# vga_controller.net
KiCad netlist of a schematic drawn in EAGLE
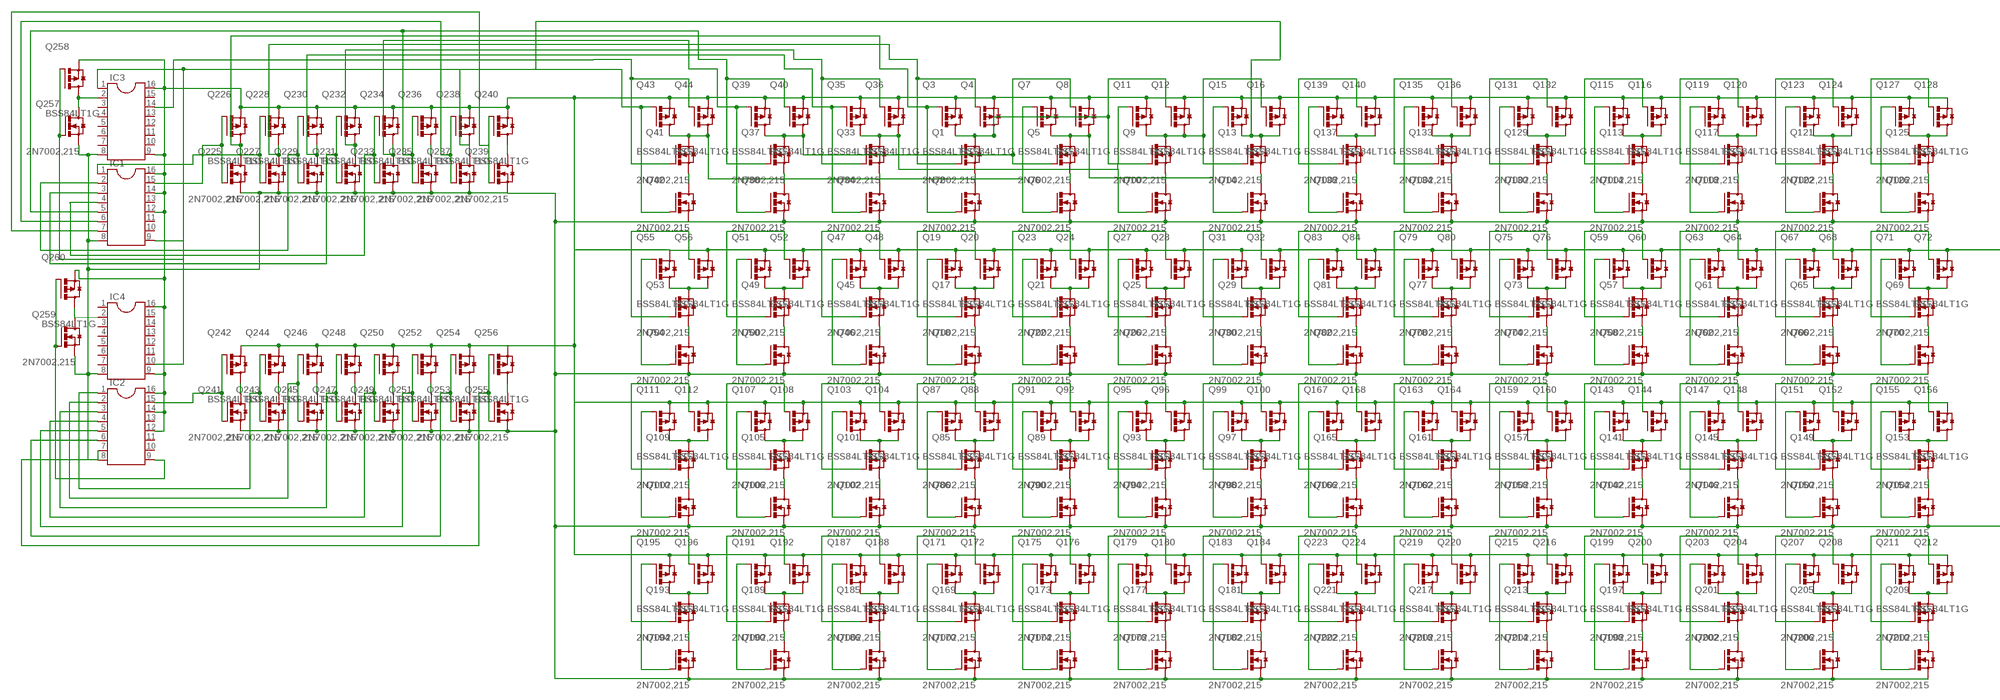
[diagram p0: schematic, sheet 1, part 1 of 2]
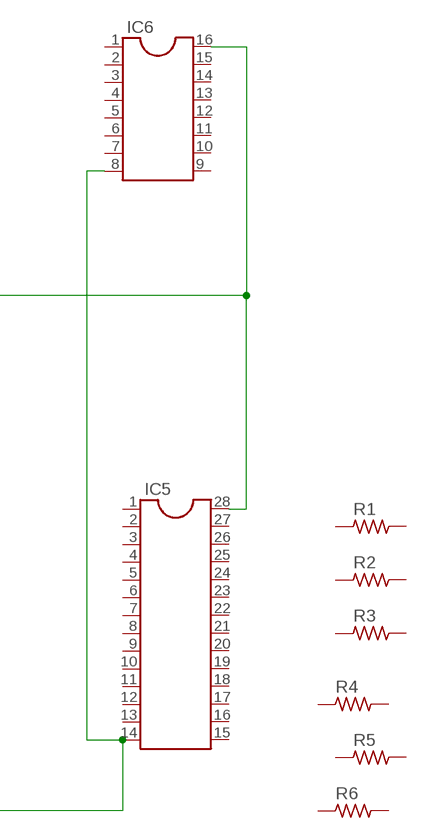
[diagram p1: schematic, sheet 1, part 2 of 2]

(export (version "E")
  (design (tool "Eeschema 10.0.6"))
  (components
    (comp (ref "IC1")
      (value "DIL16S")
      (footprint "eagle-import:SOCKET-16")
      (libsource (lib "eagle-import") (part "DIL16S"))
    )
    (comp (ref "IC2")
      (value "DIL16S")
      (footprint "eagle-import:SOCKET-16")
      (libsource (lib "eagle-import") (part "DIL16S"))
    )
    (comp (ref "IC3")
      (value "DIL16S")
      (footprint "eagle-import:SOCKET-16")
      (libsource (lib "eagle-import") (part "DIL16S"))
    )
    (comp (ref "IC4")
      (value "DIL16S")
      (footprint "eagle-import:SOCKET-16")
      (libsource (lib "eagle-import") (part "DIL16S"))
    )
    (comp (ref "IC5")
      (value "DIL28-3")
      (footprint "eagle-import:DIL28-3")
      (libsource (lib "eagle-import") (part "DIL28-3"))
    )
    (comp (ref "IC6")
      (value "DIL16S")
      (footprint "eagle-import:SOCKET-16")
      (libsource (lib "eagle-import") (part "DIL16S"))
    )
    (comp (ref "Q1")
      (value "2N7002,215")
      (footprint "eagle-import:SOT23-3")
      (fields
        (field (name "DIGIKEY_PART_NUMBER") "1727-2764-1-ND")
        (field (name "MANUFACTURER") "Nexperia USA Inc.")
        (field (name "CREATED_BY") "PCBLayout.com")
      )
      (libsource (lib "eagle-import") (part "2N7002,215"))
    )
    (comp (ref "Q2")
      (value "2N7002,215")
      (footprint "eagle-import:SOT23-3")
      (fields
        (field (name "DIGIKEY_PART_NUMBER") "1727-2764-1-ND")
        (field (name "MANUFACTURER") "Nexperia USA Inc.")
        (field (name "CREATED_BY") "PCBLayout.com")
      )
      (libsource (lib "eagle-import") (part "2N7002,215"))
    )
    (comp (ref "Q3")
      (value "BSS84LT1G")
      (footprint "eagle-import:SOT23-3")
      (fields
        (field (name "DIGIKEY_PART_NUMBER") "BSS84LT1GOSCT-ND")
        (field (name "MANUFACTURER") "ON Semiconductor")
        (field (name "CREATED_BY") "PCBLayout.com")
      )
      (libsource (lib "eagle-import") (part "BSS84LT1G"))
    )
    (comp (ref "Q4")
      (value "BSS84LT1G")
      (footprint "eagle-import:SOT23-3")
      (fields
        (field (name "DIGIKEY_PART_NUMBER") "BSS84LT1GOSCT-ND")
        (field (name "MANUFACTURER") "ON Semiconductor")
        (field (name "CREATED_BY") "PCBLayout.com")
      )
      (libsource (lib "eagle-import") (part "BSS84LT1G"))
    )
    (comp (ref "Q5")
      (value "2N7002,215")
      (footprint "eagle-import:SOT23-3")
      (fields
        (field (name "DIGIKEY_PART_NUMBER") "1727-2764-1-ND")
        (field (name "MANUFACTURER") "Nexperia USA Inc.")
        (field (name "CREATED_BY") "PCBLayout.com")
      )
      (libsource (lib "eagle-import") (part "2N7002,215"))
    )
    (comp (ref "Q6")
      (value "2N7002,215")
      (footprint "eagle-import:SOT23-3")
      (fields
        (field (name "DIGIKEY_PART_NUMBER") "1727-2764-1-ND")
        (field (name "MANUFACTURER") "Nexperia USA Inc.")
        (field (name "CREATED_BY") "PCBLayout.com")
      )
      (libsource (lib "eagle-import") (part "2N7002,215"))
    )
    (comp (ref "Q7")
      (value "BSS84LT1G")
      (footprint "eagle-import:SOT23-3")
      (fields
        (field (name "DIGIKEY_PART_NUMBER") "BSS84LT1GOSCT-ND")
        (field (name "MANUFACTURER") "ON Semiconductor")
        (field (name "CREATED_BY") "PCBLayout.com")
      )
      (libsource (lib "eagle-import") (part "BSS84LT1G"))
    )
    (comp (ref "Q8")
      (value "BSS84LT1G")
      (footprint "eagle-import:SOT23-3")
      (fields
        (field (name "DIGIKEY_PART_NUMBER") "BSS84LT1GOSCT-ND")
        (field (name "MANUFACTURER") "ON Semiconductor")
        (field (name "CREATED_BY") "PCBLayout.com")
      )
      (libsource (lib "eagle-import") (part "BSS84LT1G"))
    )
    (comp (ref "Q9")
      (value "2N7002,215")
      (footprint "eagle-import:SOT23-3")
      (fields
        (field (name "DIGIKEY_PART_NUMBER") "1727-2764-1-ND")
        (field (name "MANUFACTURER") "Nexperia USA Inc.")
        (field (name "CREATED_BY") "PCBLayout.com")
      )
      (libsource (lib "eagle-import") (part "2N7002,215"))
    )
    (comp (ref "Q10")
      (value "2N7002,215")
      (footprint "eagle-import:SOT23-3")
      (fields
        (field (name "DIGIKEY_PART_NUMBER") "1727-2764-1-ND")
        (field (name "MANUFACTURER") "Nexperia USA Inc.")
        (field (name "CREATED_BY") "PCBLayout.com")
      )
      (libsource (lib "eagle-import") (part "2N7002,215"))
    )
    (comp (ref "Q11")
      (value "BSS84LT1G")
      (footprint "eagle-import:SOT23-3")
      (fields
        (field (name "DIGIKEY_PART_NUMBER") "BSS84LT1GOSCT-ND")
        (field (name "MANUFACTURER") "ON Semiconductor")
        (field (name "CREATED_BY") "PCBLayout.com")
      )
      (libsource (lib "eagle-import") (part "BSS84LT1G"))
    )
    (comp (ref "Q12")
      (value "BSS84LT1G")
      (footprint "eagle-import:SOT23-3")
      (fields
        (field (name "DIGIKEY_PART_NUMBER") "BSS84LT1GOSCT-ND")
        (field (name "MANUFACTURER") "ON Semiconductor")
        (field (name "CREATED_BY") "PCBLayout.com")
      )
      (libsource (lib "eagle-import") (part "BSS84LT1G"))
    )
    (comp (ref "Q13")
      (value "2N7002,215")
      (footprint "eagle-import:SOT23-3")
      (fields
        (field (name "DIGIKEY_PART_NUMBER") "1727-2764-1-ND")
        (field (name "MANUFACTURER") "Nexperia USA Inc.")
        (field (name "CREATED_BY") "PCBLayout.com")
      )
      (libsource (lib "eagle-import") (part "2N7002,215"))
    )
    (comp (ref "Q14")
      (value "2N7002,215")
      (footprint "eagle-import:SOT23-3")
      (fields
        (field (name "DIGIKEY_PART_NUMBER") "1727-2764-1-ND")
        (field (name "MANUFACTURER") "Nexperia USA Inc.")
        (field (name "CREATED_BY") "PCBLayout.com")
      )
      (libsource (lib "eagle-import") (part "2N7002,215"))
    )
    (comp (ref "Q15")
      (value "BSS84LT1G")
      (footprint "eagle-import:SOT23-3")
      (fields
        (field (name "DIGIKEY_PART_NUMBER") "BSS84LT1GOSCT-ND")
        (field (name "MANUFACTURER") "ON Semiconductor")
        (field (name "CREATED_BY") "PCBLayout.com")
      )
      (libsource (lib "eagle-import") (part "BSS84LT1G"))
    )
    (comp (ref "Q16")
      (value "BSS84LT1G")
      (footprint "eagle-import:SOT23-3")
      (fields
        (field (name "DIGIKEY_PART_NUMBER") "BSS84LT1GOSCT-ND")
        (field (name "MANUFACTURER") "ON Semiconductor")
        (field (name "CREATED_BY") "PCBLayout.com")
      )
      (libsource (lib "eagle-import") (part "BSS84LT1G"))
    )
    (comp (ref "Q17")
      (value "2N7002,215")
      (footprint "eagle-import:SOT23-3")
      (fields
        (field (name "DIGIKEY_PART_NUMBER") "1727-2764-1-ND")
        (field (name "MANUFACTURER") "Nexperia USA Inc.")
        (field (name "CREATED_BY") "PCBLayout.com")
      )
      (libsource (lib "eagle-import") (part "2N7002,215"))
    )
    (comp (ref "Q18")
      (value "2N7002,215")
      (footprint "eagle-import:SOT23-3")
      (fields
        (field (name "DIGIKEY_PART_NUMBER") "1727-2764-1-ND")
        (field (name "MANUFACTURER") "Nexperia USA Inc.")
        (field (name "CREATED_BY") "PCBLayout.com")
      )
      (libsource (lib "eagle-import") (part "2N7002,215"))
    )
    (comp (ref "Q19")
      (value "BSS84LT1G")
      (footprint "eagle-import:SOT23-3")
      (fields
        (field (name "DIGIKEY_PART_NUMBER") "BSS84LT1GOSCT-ND")
        (field (name "MANUFACTURER") "ON Semiconductor")
        (field (name "CREATED_BY") "PCBLayout.com")
      )
      (libsource (lib "eagle-import") (part "BSS84LT1G"))
    )
    (comp (ref "Q20")
      (value "BSS84LT1G")
      (footprint "eagle-import:SOT23-3")
      (fields
        (field (name "DIGIKEY_PART_NUMBER") "BSS84LT1GOSCT-ND")
        (field (name "MANUFACTURER") "ON Semiconductor")
        (field (name "CREATED_BY") "PCBLayout.com")
      )
      (libsource (lib "eagle-import") (part "BSS84LT1G"))
    )
    (comp (ref "Q21")
      (value "2N7002,215")
      (footprint "eagle-import:SOT23-3")
      (fields
        (field (name "DIGIKEY_PART_NUMBER") "1727-2764-1-ND")
        (field (name "MANUFACTURER") "Nexperia USA Inc.")
        (field (name "CREATED_BY") "PCBLayout.com")
      )
      (libsource (lib "eagle-import") (part "2N7002,215"))
    )
    (comp (ref "Q22")
      (value "2N7002,215")
      (footprint "eagle-import:SOT23-3")
      (fields
        (field (name "DIGIKEY_PART_NUMBER") "1727-2764-1-ND")
        (field (name "MANUFACTURER") "Nexperia USA Inc.")
        (field (name "CREATED_BY") "PCBLayout.com")
      )
      (libsource (lib "eagle-import") (part "2N7002,215"))
    )
    (comp (ref "Q23")
      (value "BSS84LT1G")
      (footprint "eagle-import:SOT23-3")
      (fields
        (field (name "DIGIKEY_PART_NUMBER") "BSS84LT1GOSCT-ND")
        (field (name "MANUFACTURER") "ON Semiconductor")
        (field (name "CREATED_BY") "PCBLayout.com")
      )
      (libsource (lib "eagle-import") (part "BSS84LT1G"))
    )
    (comp (ref "Q24")
      (value "BSS84LT1G")
      (footprint "eagle-import:SOT23-3")
      (fields
        (field (name "DIGIKEY_PART_NUMBER") "BSS84LT1GOSCT-ND")
        (field (name "MANUFACTURER") "ON Semiconductor")
        (field (name "CREATED_BY") "PCBLayout.com")
      )
      (libsource (lib "eagle-import") (part "BSS84LT1G"))
    )
    (comp (ref "Q25")
      (value "2N7002,215")
      (footprint "eagle-import:SOT23-3")
      (fields
        (field (name "DIGIKEY_PART_NUMBER") "1727-2764-1-ND")
        (field (name "MANUFACTURER") "Nexperia USA Inc.")
        (field (name "CREATED_BY") "PCBLayout.com")
      )
      (libsource (lib "eagle-import") (part "2N7002,215"))
    )
    (comp (ref "Q26")
      (value "2N7002,215")
      (footprint "eagle-import:SOT23-3")
      (fields
        (field (name "DIGIKEY_PART_NUMBER") "1727-2764-1-ND")
        (field (name "MANUFACTURER") "Nexperia USA Inc.")
        (field (name "CREATED_BY") "PCBLayout.com")
      )
      (libsource (lib "eagle-import") (part "2N7002,215"))
    )
    (comp (ref "Q27")
      (value "BSS84LT1G")
      (footprint "eagle-import:SOT23-3")
      (fields
        (field (name "DIGIKEY_PART_NUMBER") "BSS84LT1GOSCT-ND")
        (field (name "MANUFACTURER") "ON Semiconductor")
        (field (name "CREATED_BY") "PCBLayout.com")
      )
      (libsource (lib "eagle-import") (part "BSS84LT1G"))
    )
    (comp (ref "Q28")
      (value "BSS84LT1G")
      (footprint "eagle-import:SOT23-3")
      (fields
        (field (name "DIGIKEY_PART_NUMBER") "BSS84LT1GOSCT-ND")
        (field (name "MANUFACTURER") "ON Semiconductor")
        (field (name "CREATED_BY") "PCBLayout.com")
      )
      (libsource (lib "eagle-import") (part "BSS84LT1G"))
    )
    (comp (ref "Q29")
      (value "2N7002,215")
      (footprint "eagle-import:SOT23-3")
      (fields
        (field (name "DIGIKEY_PART_NUMBER") "1727-2764-1-ND")
        (field (name "MANUFACTURER") "Nexperia USA Inc.")
        (field (name "CREATED_BY") "PCBLayout.com")
      )
      (libsource (lib "eagle-import") (part "2N7002,215"))
    )
    (comp (ref "Q30")
      (value "2N7002,215")
      (footprint "eagle-import:SOT23-3")
      (fields
        (field (name "DIGIKEY_PART_NUMBER") "1727-2764-1-ND")
        (field (name "MANUFACTURER") "Nexperia USA Inc.")
        (field (name "CREATED_BY") "PCBLayout.com")
      )
      (libsource (lib "eagle-import") (part "2N7002,215"))
    )
    (comp (ref "Q31")
      (value "BSS84LT1G")
      (footprint "eagle-import:SOT23-3")
      (fields
        (field (name "DIGIKEY_PART_NUMBER") "BSS84LT1GOSCT-ND")
        (field (name "MANUFACTURER") "ON Semiconductor")
        (field (name "CREATED_BY") "PCBLayout.com")
      )
      (libsource (lib "eagle-import") (part "BSS84LT1G"))
    )
    (comp (ref "Q32")
      (value "BSS84LT1G")
      (footprint "eagle-import:SOT23-3")
      (fields
        (field (name "DIGIKEY_PART_NUMBER") "BSS84LT1GOSCT-ND")
        (field (name "MANUFACTURER") "ON Semiconductor")
        (field (name "CREATED_BY") "PCBLayout.com")
      )
      (libsource (lib "eagle-import") (part "BSS84LT1G"))
    )
    (comp (ref "Q33")
      (value "2N7002,215")
      (footprint "eagle-import:SOT23-3")
      (fields
        (field (name "DIGIKEY_PART_NUMBER") "1727-2764-1-ND")
        (field (name "MANUFACTURER") "Nexperia USA Inc.")
        (field (name "CREATED_BY") "PCBLayout.com")
      )
      (libsource (lib "eagle-import") (part "2N7002,215"))
    )
    (comp (ref "Q34")
      (value "2N7002,215")
      (footprint "eagle-import:SOT23-3")
      (fields
        (field (name "DIGIKEY_PART_NUMBER") "1727-2764-1-ND")
        (field (name "MANUFACTURER") "Nexperia USA Inc.")
        (field (name "CREATED_BY") "PCBLayout.com")
      )
      (libsource (lib "eagle-import") (part "2N7002,215"))
    )
    (comp (ref "Q35")
      (value "BSS84LT1G")
      (footprint "eagle-import:SOT23-3")
      (fields
        (field (name "DIGIKEY_PART_NUMBER") "BSS84LT1GOSCT-ND")
        (field (name "MANUFACTURER") "ON Semiconductor")
        (field (name "CREATED_BY") "PCBLayout.com")
      )
      (libsource (lib "eagle-import") (part "BSS84LT1G"))
    )
    (comp (ref "Q36")
      (value "BSS84LT1G")
      (footprint "eagle-import:SOT23-3")
      (fields
        (field (name "DIGIKEY_PART_NUMBER") "BSS84LT1GOSCT-ND")
        (field (name "MANUFACTURER") "ON Semiconductor")
        (field (name "CREATED_BY") "PCBLayout.com")
      )
      (libsource (lib "eagle-import") (part "BSS84LT1G"))
    )
    (comp (ref "Q37")
      (value "2N7002,215")
      (footprint "eagle-import:SOT23-3")
      (fields
        (field (name "DIGIKEY_PART_NUMBER") "1727-2764-1-ND")
        (field (name "MANUFACTURER") "Nexperia USA Inc.")
        (field (name "CREATED_BY") "PCBLayout.com")
      )
      (libsource (lib "eagle-import") (part "2N7002,215"))
    )
    (comp (ref "Q38")
      (value "2N7002,215")
      (footprint "eagle-import:SOT23-3")
      (fields
        (field (name "DIGIKEY_PART_NUMBER") "1727-2764-1-ND")
        (field (name "MANUFACTURER") "Nexperia USA Inc.")
        (field (name "CREATED_BY") "PCBLayout.com")
      )
      (libsource (lib "eagle-import") (part "2N7002,215"))
    )
    (comp (ref "Q39")
      (value "BSS84LT1G")
      (footprint "eagle-import:SOT23-3")
      (fields
        (field (name "DIGIKEY_PART_NUMBER") "BSS84LT1GOSCT-ND")
        (field (name "MANUFACTURER") "ON Semiconductor")
        (field (name "CREATED_BY") "PCBLayout.com")
      )
      (libsource (lib "eagle-import") (part "BSS84LT1G"))
    )
    (comp (ref "Q40")
      (value "BSS84LT1G")
      (footprint "eagle-import:SOT23-3")
      (fields
        (field (name "DIGIKEY_PART_NUMBER") "BSS84LT1GOSCT-ND")
        (field (name "MANUFACTURER") "ON Semiconductor")
        (field (name "CREATED_BY") "PCBLayout.com")
      )
      (libsource (lib "eagle-import") (part "BSS84LT1G"))
    )
    (comp (ref "Q41")
      (value "2N7002,215")
      (footprint "eagle-import:SOT23-3")
      (fields
        (field (name "DIGIKEY_PART_NUMBER") "1727-2764-1-ND")
        (field (name "MANUFACTURER") "Nexperia USA Inc.")
        (field (name "CREATED_BY") "PCBLayout.com")
      )
      (libsource (lib "eagle-import") (part "2N7002,215"))
    )
    (comp (ref "Q42")
      (value "2N7002,215")
      (footprint "eagle-import:SOT23-3")
      (fields
        (field (name "DIGIKEY_PART_NUMBER") "1727-2764-1-ND")
        (field (name "MANUFACTURER") "Nexperia USA Inc.")
        (field (name "CREATED_BY") "PCBLayout.com")
      )
      (libsource (lib "eagle-import") (part "2N7002,215"))
    )
    (comp (ref "Q43")
      (value "BSS84LT1G")
      (footprint "eagle-import:SOT23-3")
      (fields
        (field (name "DIGIKEY_PART_NUMBER") "BSS84LT1GOSCT-ND")
        (field (name "MANUFACTURER") "ON Semiconductor")
        (field (name "CREATED_BY") "PCBLayout.com")
      )
      (libsource (lib "eagle-import") (part "BSS84LT1G"))
    )
    (comp (ref "Q44")
      (value "BSS84LT1G")
      (footprint "eagle-import:SOT23-3")
      (fields
        (field (name "DIGIKEY_PART_NUMBER") "BSS84LT1GOSCT-ND")
        (field (name "MANUFACTURER") "ON Semiconductor")
        (field (name "CREATED_BY") "PCBLayout.com")
      )
      (libsource (lib "eagle-import") (part "BSS84LT1G"))
    )
    (comp (ref "Q45")
      (value "2N7002,215")
      (footprint "eagle-import:SOT23-3")
      (fields
        (field (name "DIGIKEY_PART_NUMBER") "1727-2764-1-ND")
        (field (name "MANUFACTURER") "Nexperia USA Inc.")
        (field (name "CREATED_BY") "PCBLayout.com")
      )
      (libsource (lib "eagle-import") (part "2N7002,215"))
    )
    (comp (ref "Q46")
      (value "2N7002,215")
      (footprint "eagle-import:SOT23-3")
      (fields
        (field (name "DIGIKEY_PART_NUMBER") "1727-2764-1-ND")
        (field (name "MANUFACTURER") "Nexperia USA Inc.")
        (field (name "CREATED_BY") "PCBLayout.com")
      )
      (libsource (lib "eagle-import") (part "2N7002,215"))
    )
    (comp (ref "Q47")
      (value "BSS84LT1G")
      (footprint "eagle-import:SOT23-3")
      (fields
        (field (name "DIGIKEY_PART_NUMBER") "BSS84LT1GOSCT-ND")
        (field (name "MANUFACTURER") "ON Semiconductor")
        (field (name "CREATED_BY") "PCBLayout.com")
      )
      (libsource (lib "eagle-import") (part "BSS84LT1G"))
    )
    (comp (ref "Q48")
      (value "BSS84LT1G")
      (footprint "eagle-import:SOT23-3")
      (fields
        (field (name "DIGIKEY_PART_NUMBER") "BSS84LT1GOSCT-ND")
        (field (name "MANUFACTURER") "ON Semiconductor")
        (field (name "CREATED_BY") "PCBLayout.com")
      )
      (libsource (lib "eagle-import") (part "BSS84LT1G"))
    )
    (comp (ref "Q49")
      (value "2N7002,215")
      (footprint "eagle-import:SOT23-3")
      (fields
        (field (name "DIGIKEY_PART_NUMBER") "1727-2764-1-ND")
        (field (name "MANUFACTURER") "Nexperia USA Inc.")
        (field (name "CREATED_BY") "PCBLayout.com")
      )
      (libsource (lib "eagle-import") (part "2N7002,215"))
    )
    (comp (ref "Q50")
      (value "2N7002,215")
      (footprint "eagle-import:SOT23-3")
      (fields
        (field (name "DIGIKEY_PART_NUMBER") "1727-2764-1-ND")
        (field (name "MANUFACTURER") "Nexperia USA Inc.")
        (field (name "CREATED_BY") "PCBLayout.com")
      )
      (libsource (lib "eagle-import") (part "2N7002,215"))
    )
    (comp (ref "Q51")
      (value "BSS84LT1G")
      (footprint "eagle-import:SOT23-3")
      (fields
        (field (name "DIGIKEY_PART_NUMBER") "BSS84LT1GOSCT-ND")
        (field (name "MANUFACTURER") "ON Semiconductor")
        (field (name "CREATED_BY") "PCBLayout.com")
      )
      (libsource (lib "eagle-import") (part "BSS84LT1G"))
    )
    (comp (ref "Q52")
      (value "BSS84LT1G")
      (footprint "eagle-import:SOT23-3")
      (fields
        (field (name "DIGIKEY_PART_NUMBER") "BSS84LT1GOSCT-ND")
        (field (name "MANUFACTURER") "ON Semiconductor")
        (field (name "CREATED_BY") "PCBLayout.com")
      )
      (libsource (lib "eagle-import") (part "BSS84LT1G"))
    )
    (comp (ref "Q53")
      (value "2N7002,215")
      (footprint "eagle-import:SOT23-3")
      (fields
        (field (name "DIGIKEY_PART_NUMBER") "1727-2764-1-ND")
        (field (name "MANUFACTURER") "Nexperia USA Inc.")
        (field (name "CREATED_BY") "PCBLayout.com")
      )
      (libsource (lib "eagle-import") (part "2N7002,215"))
    )
    (comp (ref "Q54")
      (value "2N7002,215")
      (footprint "eagle-import:SOT23-3")
      (fields
        (field (name "DIGIKEY_PART_NUMBER") "1727-2764-1-ND")
        (field (name "MANUFACTURER") "Nexperia USA Inc.")
        (field (name "CREATED_BY") "PCBLayout.com")
      )
      (libsource (lib "eagle-import") (part "2N7002,215"))
    )
    (comp (ref "Q55")
      (value "BSS84LT1G")
      (footprint "eagle-import:SOT23-3")
      (fields
        (field (name "DIGIKEY_PART_NUMBER") "BSS84LT1GOSCT-ND")
        (field (name "MANUFACTURER") "ON Semiconductor")
        (field (name "CREATED_BY") "PCBLayout.com")
      )
      (libsource (lib "eagle-import") (part "BSS84LT1G"))
    )
    (comp (ref "Q56")
      (value "BSS84LT1G")
      (footprint "eagle-import:SOT23-3")
      (fields
        (field (name "DIGIKEY_PART_NUMBER") "BSS84LT1GOSCT-ND")
        (field (name "MANUFACTURER") "ON Semiconductor")
        (field (name "CREATED_BY") "PCBLayout.com")
      )
      (libsource (lib "eagle-import") (part "BSS84LT1G"))
    )
    (comp (ref "Q57")
      (value "2N7002,215")
      (footprint "eagle-import:SOT23-3")
      (fields
        (field (name "DIGIKEY_PART_NUMBER") "1727-2764-1-ND")
        (field (name "MANUFACTURER") "Nexperia USA Inc.")
        (field (name "CREATED_BY") "PCBLayout.com")
      )
      (libsource (lib "eagle-import") (part "2N7002,215"))
    )
    (comp (ref "Q58")
      (value "2N7002,215")
      (footprint "eagle-import:SOT23-3")
      (fields
        (field (name "DIGIKEY_PART_NUMBER") "1727-2764-1-ND")
        (field (name "MANUFACTURER") "Nexperia USA Inc.")
        (field (name "CREATED_BY") "PCBLayout.com")
      )
      (libsource (lib "eagle-import") (part "2N7002,215"))
    )
    (comp (ref "Q59")
      (value "BSS84LT1G")
      (footprint "eagle-import:SOT23-3")
      (fields
        (field (name "DIGIKEY_PART_NUMBER") "BSS84LT1GOSCT-ND")
        (field (name "MANUFACTURER") "ON Semiconductor")
        (field (name "CREATED_BY") "PCBLayout.com")
      )
      (libsource (lib "eagle-import") (part "BSS84LT1G"))
    )
    (comp (ref "Q60")
      (value "BSS84LT1G")
      (footprint "eagle-import:SOT23-3")
      (fields
        (field (name "DIGIKEY_PART_NUMBER") "BSS84LT1GOSCT-ND")
        (field (name "MANUFACTURER") "ON Semiconductor")
        (field (name "CREATED_BY") "PCBLayout.com")
      )
      (libsource (lib "eagle-import") (part "BSS84LT1G"))
    )
    (comp (ref "Q61")
      (value "2N7002,215")
      (footprint "eagle-import:SOT23-3")
      (fields
        (field (name "DIGIKEY_PART_NUMBER") "1727-2764-1-ND")
        (field (name "MANUFACTURER") "Nexperia USA Inc.")
        (field (name "CREATED_BY") "PCBLayout.com")
      )
      (libsource (lib "eagle-import") (part "2N7002,215"))
    )
    (comp (ref "Q62")
      (value "2N7002,215")
      (footprint "eagle-import:SOT23-3")
      (fields
        (field (name "DIGIKEY_PART_NUMBER") "1727-2764-1-ND")
        (field (name "MANUFACTURER") "Nexperia USA Inc.")
        (field (name "CREATED_BY") "PCBLayout.com")
      )
      (libsource (lib "eagle-import") (part "2N7002,215"))
    )
    (comp (ref "Q63")
      (value "BSS84LT1G")
      (footprint "eagle-import:SOT23-3")
      (fields
        (field (name "DIGIKEY_PART_NUMBER") "BSS84LT1GOSCT-ND")
        (field (name "MANUFACTURER") "ON Semiconductor")
        (field (name "CREATED_BY") "PCBLayout.com")
      )
      (libsource (lib "eagle-import") (part "BSS84LT1G"))
    )
    (comp (ref "Q64")
      (value "BSS84LT1G")
      (footprint "eagle-import:SOT23-3")
      (fields
        (field (name "DIGIKEY_PART_NUMBER") "BSS84LT1GOSCT-ND")
        (field (name "MANUFACTURER") "ON Semiconductor")
        (field (name "CREATED_BY") "PCBLayout.com")
      )
      (libsource (lib "eagle-import") (part "BSS84LT1G"))
    )
    (comp (ref "Q65")
      (value "2N7002,215")
      (footprint "eagle-import:SOT23-3")
      (fields
        (field (name "DIGIKEY_PART_NUMBER") "1727-2764-1-ND")
        (field (name "MANUFACTURER") "Nexperia USA Inc.")
        (field (name "CREATED_BY") "PCBLayout.com")
      )
      (libsource (lib "eagle-import") (part "2N7002,215"))
    )
    (comp (ref "Q66")
      (value "2N7002,215")
      (footprint "eagle-import:SOT23-3")
      (fields
        (field (name "DIGIKEY_PART_NUMBER") "1727-2764-1-ND")
        (field (name "MANUFACTURER") "Nexperia USA Inc.")
        (field (name "CREATED_BY") "PCBLayout.com")
      )
      (libsource (lib "eagle-import") (part "2N7002,215"))
    )
    (comp (ref "Q67")
      (value "BSS84LT1G")
      (footprint "eagle-import:SOT23-3")
      (fields
        (field (name "DIGIKEY_PART_NUMBER") "BSS84LT1GOSCT-ND")
        (field (name "MANUFACTURER") "ON Semiconductor")
        (field (name "CREATED_BY") "PCBLayout.com")
      )
      (libsource (lib "eagle-import") (part "BSS84LT1G"))
    )
    (comp (ref "Q68")
      (value "BSS84LT1G")
      (footprint "eagle-import:SOT23-3")
      (fields
        (field (name "DIGIKEY_PART_NUMBER") "BSS84LT1GOSCT-ND")
        (field (name "MANUFACTURER") "ON Semiconductor")
        (field (name "CREATED_BY") "PCBLayout.com")
      )
      (libsource (lib "eagle-import") (part "BSS84LT1G"))
    )
    (comp (ref "Q69")
      (value "2N7002,215")
      (footprint "eagle-import:SOT23-3")
      (fields
        (field (name "DIGIKEY_PART_NUMBER") "1727-2764-1-ND")
        (field (name "MANUFACTURER") "Nexperia USA Inc.")
        (field (name "CREATED_BY") "PCBLayout.com")
      )
      (libsource (lib "eagle-import") (part "2N7002,215"))
    )
    (comp (ref "Q70")
      (value "2N7002,215")
      (footprint "eagle-import:SOT23-3")
      (fields
        (field (name "DIGIKEY_PART_NUMBER") "1727-2764-1-ND")
        (field (name "MANUFACTURER") "Nexperia USA Inc.")
        (field (name "CREATED_BY") "PCBLayout.com")
      )
      (libsource (lib "eagle-import") (part "2N7002,215"))
    )
    (comp (ref "Q71")
      (value "BSS84LT1G")
      (footprint "eagle-import:SOT23-3")
      (fields
        (field (name "DIGIKEY_PART_NUMBER") "BSS84LT1GOSCT-ND")
        (field (name "MANUFACTURER") "ON Semiconductor")
        (field (name "CREATED_BY") "PCBLayout.com")
      )
      (libsource (lib "eagle-import") (part "BSS84LT1G"))
    )
    (comp (ref "Q72")
      (value "BSS84LT1G")
      (footprint "eagle-import:SOT23-3")
      (fields
        (field (name "DIGIKEY_PART_NUMBER") "BSS84LT1GOSCT-ND")
        (field (name "MANUFACTURER") "ON Semiconductor")
        (field (name "CREATED_BY") "PCBLayout.com")
      )
      (libsource (lib "eagle-import") (part "BSS84LT1G"))
    )
    (comp (ref "Q73")
      (value "2N7002,215")
      (footprint "eagle-import:SOT23-3")
      (fields
        (field (name "DIGIKEY_PART_NUMBER") "1727-2764-1-ND")
        (field (name "MANUFACTURER") "Nexperia USA Inc.")
        (field (name "CREATED_BY") "PCBLayout.com")
      )
      (libsource (lib "eagle-import") (part "2N7002,215"))
    )
    (comp (ref "Q74")
      (value "2N7002,215")
      (footprint "eagle-import:SOT23-3")
      (fields
        (field (name "DIGIKEY_PART_NUMBER") "1727-2764-1-ND")
        (field (name "MANUFACTURER") "Nexperia USA Inc.")
        (field (name "CREATED_BY") "PCBLayout.com")
      )
      (libsource (lib "eagle-import") (part "2N7002,215"))
    )
    (comp (ref "Q75")
      (value "BSS84LT1G")
      (footprint "eagle-import:SOT23-3")
      (fields
        (field (name "DIGIKEY_PART_NUMBER") "BSS84LT1GOSCT-ND")
        (field (name "MANUFACTURER") "ON Semiconductor")
        (field (name "CREATED_BY") "PCBLayout.com")
      )
      (libsource (lib "eagle-import") (part "BSS84LT1G"))
    )
    (comp (ref "Q76")
      (value "BSS84LT1G")
      (footprint "eagle-import:SOT23-3")
      (fields
        (field (name "DIGIKEY_PART_NUMBER") "BSS84LT1GOSCT-ND")
        (field (name "MANUFACTURER") "ON Semiconductor")
        (field (name "CREATED_BY") "PCBLayout.com")
      )
      (libsource (lib "eagle-import") (part "BSS84LT1G"))
    )
    (comp (ref "Q77")
      (value "2N7002,215")
      (footprint "eagle-import:SOT23-3")
      (fields
        (field (name "DIGIKEY_PART_NUMBER") "1727-2764-1-ND")
        (field (name "MANUFACTURER") "Nexperia USA Inc.")
        (field (name "CREATED_BY") "PCBLayout.com")
      )
      (libsource (lib "eagle-import") (part "2N7002,215"))
    )
    (comp (ref "Q78")
      (value "2N7002,215")
      (footprint "eagle-import:SOT23-3")
      (fields
        (field (name "DIGIKEY_PART_NUMBER") "1727-2764-1-ND")
        (field (name "MANUFACTURER") "Nexperia USA Inc.")
        (field (name "CREATED_BY") "PCBLayout.com")
      )
      (libsource (lib "eagle-import") (part "2N7002,215"))
    )
    (comp (ref "Q79")
      (value "BSS84LT1G")
      (footprint "eagle-import:SOT23-3")
      (fields
        (field (name "DIGIKEY_PART_NUMBER") "BSS84LT1GOSCT-ND")
        (field (name "MANUFACTURER") "ON Semiconductor")
        (field (name "CREATED_BY") "PCBLayout.com")
      )
      (libsource (lib "eagle-import") (part "BSS84LT1G"))
    )
    (comp (ref "Q80")
      (value "BSS84LT1G")
      (footprint "eagle-import:SOT23-3")
      (fields
        (field (name "DIGIKEY_PART_NUMBER") "BSS84LT1GOSCT-ND")
        (field (name "MANUFACTURER") "ON Semiconductor")
        (field (name "CREATED_BY") "PCBLayout.com")
      )
      (libsource (lib "eagle-import") (part "BSS84LT1G"))
    )
    (comp (ref "Q81")
      (value "2N7002,215")
      (footprint "eagle-import:SOT23-3")
      (fields
        (field (name "DIGIKEY_PART_NUMBER") "1727-2764-1-ND")
        (field (name "MANUFACTURER") "Nexperia USA Inc.")
        (field (name "CREATED_BY") "PCBLayout.com")
      )
      (libsource (lib "eagle-import") (part "2N7002,215"))
    )
    (comp (ref "Q82")
      (value "2N7002,215")
      (footprint "eagle-import:SOT23-3")
      (fields
        (field (name "DIGIKEY_PART_NUMBER") "1727-2764-1-ND")
        (field (name "MANUFACTURER") "Nexperia USA Inc.")
        (field (name "CREATED_BY") "PCBLayout.com")
      )
      (libsource (lib "eagle-import") (part "2N7002,215"))
    )
    (comp (ref "Q83")
      (value "BSS84LT1G")
      (footprint "eagle-import:SOT23-3")
      (fields
        (field (name "DIGIKEY_PART_NUMBER") "BSS84LT1GOSCT-ND")
        (field (name "MANUFACTURER") "ON Semiconductor")
        (field (name "CREATED_BY") "PCBLayout.com")
      )
      (libsource (lib "eagle-import") (part "BSS84LT1G"))
    )
    (comp (ref "Q84")
      (value "BSS84LT1G")
      (footprint "eagle-import:SOT23-3")
      (fields
        (field (name "DIGIKEY_PART_NUMBER") "BSS84LT1GOSCT-ND")
        (field (name "MANUFACTURER") "ON Semiconductor")
        (field (name "CREATED_BY") "PCBLayout.com")
      )
      (libsource (lib "eagle-import") (part "BSS84LT1G"))
    )
    (comp (ref "Q85")
      (value "2N7002,215")
      (footprint "eagle-import:SOT23-3")
      (fields
        (field (name "DIGIKEY_PART_NUMBER") "1727-2764-1-ND")
        (field (name "MANUFACTURER") "Nexperia USA Inc.")
        (field (name "CREATED_BY") "PCBLayout.com")
      )
      (libsource (lib "eagle-import") (part "2N7002,215"))
    )
    (comp (ref "Q86")
      (value "2N7002,215")
      (footprint "eagle-import:SOT23-3")
      (fields
        (field (name "DIGIKEY_PART_NUMBER") "1727-2764-1-ND")
        (field (name "MANUFACTURER") "Nexperia USA Inc.")
        (field (name "CREATED_BY") "PCBLayout.com")
      )
      (libsource (lib "eagle-import") (part "2N7002,215"))
    )
    (comp (ref "Q87")
      (value "BSS84LT1G")
      (footprint "eagle-import:SOT23-3")
      (fields
        (field (name "DIGIKEY_PART_NUMBER") "BSS84LT1GOSCT-ND")
        (field (name "MANUFACTURER") "ON Semiconductor")
        (field (name "CREATED_BY") "PCBLayout.com")
      )
      (libsource (lib "eagle-import") (part "BSS84LT1G"))
    )
    (comp (ref "Q88")
      (value "BSS84LT1G")
      (footprint "eagle-import:SOT23-3")
      (fields
        (field (name "DIGIKEY_PART_NUMBER") "BSS84LT1GOSCT-ND")
        (field (name "MANUFACTURER") "ON Semiconductor")
        (field (name "CREATED_BY") "PCBLayout.com")
      )
      (libsource (lib "eagle-import") (part "BSS84LT1G"))
    )
    (comp (ref "Q89")
      (value "2N7002,215")
      (footprint "eagle-import:SOT23-3")
      (fields
        (field (name "DIGIKEY_PART_NUMBER") "1727-2764-1-ND")
        (field (name "MANUFACTURER") "Nexperia USA Inc.")
        (field (name "CREATED_BY") "PCBLayout.com")
      )
      (libsource (lib "eagle-import") (part "2N7002,215"))
    )
    (comp (ref "Q90")
      (value "2N7002,215")
      (footprint "eagle-import:SOT23-3")
      (fields
        (field (name "DIGIKEY_PART_NUMBER") "1727-2764-1-ND")
        (field (name "MANUFACTURER") "Nexperia USA Inc.")
        (field (name "CREATED_BY") "PCBLayout.com")
      )
      (libsource (lib "eagle-import") (part "2N7002,215"))
    )
    (comp (ref "Q91")
      (value "BSS84LT1G")
      (footprint "eagle-import:SOT23-3")
      (fields
        (field (name "DIGIKEY_PART_NUMBER") "BSS84LT1GOSCT-ND")
        (field (name "MANUFACTURER") "ON Semiconductor")
        (field (name "CREATED_BY") "PCBLayout.com")
      )
      (libsource (lib "eagle-import") (part "BSS84LT1G"))
    )
    (comp (ref "Q92")
      (value "BSS84LT1G")
      (footprint "eagle-import:SOT23-3")
      (fields
        (field (name "DIGIKEY_PART_NUMBER") "BSS84LT1GOSCT-ND")
        (field (name "MANUFACTURER") "ON Semiconductor")
        (field (name "CREATED_BY") "PCBLayout.com")
      )
      (libsource (lib "eagle-import") (part "BSS84LT1G"))
    )
    (comp (ref "Q93")
      (value "2N7002,215")
      (footprint "eagle-import:SOT23-3")
      (fields
        (field (name "DIGIKEY_PART_NUMBER") "1727-2764-1-ND")
        (field (name "MANUFACTURER") "Nexperia USA Inc.")
        (field (name "CREATED_BY") "PCBLayout.com")
      )
      (libsource (lib "eagle-import") (part "2N7002,215"))
    )
    (comp (ref "Q94")
      (value "2N7002,215")
      (footprint "eagle-import:SOT23-3")
      (fields
        (field (name "DIGIKEY_PART_NUMBER") "1727-2764-1-ND")
        (field (name "MANUFACTURER") "Nexperia USA Inc.")
        (field (name "CREATED_BY") "PCBLayout.com")
      )
      (libsource (lib "eagle-import") (part "2N7002,215"))
    )
    (comp (ref "Q95")
      (value "BSS84LT1G")
      (footprint "eagle-import:SOT23-3")
      (fields
        (field (name "DIGIKEY_PART_NUMBER") "BSS84LT1GOSCT-ND")
        (field (name "MANUFACTURER") "ON Semiconductor")
        (field (name "CREATED_BY") "PCBLayout.com")
      )
      (libsource (lib "eagle-import") (part "BSS84LT1G"))
    )
    (comp (ref "Q96")
      (value "BSS84LT1G")
      (footprint "eagle-import:SOT23-3")
      (fields
        (field (name "DIGIKEY_PART_NUMBER") "BSS84LT1GOSCT-ND")
        (field (name "MANUFACTURER") "ON Semiconductor")
        (field (name "CREATED_BY") "PCBLayout.com")
      )
      (libsource (lib "eagle-import") (part "BSS84LT1G"))
    )
    (comp (ref "Q97")
      (value "2N7002,215")
      (footprint "eagle-import:SOT23-3")
      (fields
        (field (name "DIGIKEY_PART_NUMBER") "1727-2764-1-ND")
        (field (name "MANUFACTURER") "Nexperia USA Inc.")
        (field (name "CREATED_BY") "PCBLayout.com")
      )
      (libsource (lib "eagle-import") (part "2N7002,215"))
    )
    (comp (ref "Q98")
      (value "2N7002,215")
      (footprint "eagle-import:SOT23-3")
      (fields
        (field (name "DIGIKEY_PART_NUMBER") "1727-2764-1-ND")
        (field (name "MANUFACTURER") "Nexperia USA Inc.")
        (field (name "CREATED_BY") "PCBLayout.com")
      )
      (libsource (lib "eagle-import") (part "2N7002,215"))
    )
    (comp (ref "Q99")
      (value "BSS84LT1G")
      (footprint "eagle-import:SOT23-3")
      (fields
        (field (name "DIGIKEY_PART_NUMBER") "BSS84LT1GOSCT-ND")
        (field (name "MANUFACTURER") "ON Semiconductor")
        (field (name "CREATED_BY") "PCBLayout.com")
      )
      (libsource (lib "eagle-import") (part "BSS84LT1G"))
    )
    (comp (ref "Q100")
      (value "BSS84LT1G")
      (footprint "eagle-import:SOT23-3")
      (fields
        (field (name "DIGIKEY_PART_NUMBER") "BSS84LT1GOSCT-ND")
        (field (name "MANUFACTURER") "ON Semiconductor")
        (field (name "CREATED_BY") "PCBLayout.com")
      )
      (libsource (lib "eagle-import") (part "BSS84LT1G"))
    )
    (comp (ref "Q101")
      (value "2N7002,215")
      (footprint "eagle-import:SOT23-3")
      (fields
        (field (name "DIGIKEY_PART_NUMBER") "1727-2764-1-ND")
        (field (name "MANUFACTURER") "Nexperia USA Inc.")
        (field (name "CREATED_BY") "PCBLayout.com")
      )
      (libsource (lib "eagle-import") (part "2N7002,215"))
    )
    (comp (ref "Q102")
      (value "2N7002,215")
      (footprint "eagle-import:SOT23-3")
      (fields
        (field (name "DIGIKEY_PART_NUMBER") "1727-2764-1-ND")
        (field (name "MANUFACTURER") "Nexperia USA Inc.")
        (field (name "CREATED_BY") "PCBLayout.com")
      )
      (libsource (lib "eagle-import") (part "2N7002,215"))
    )
    (comp (ref "Q103")
      (value "BSS84LT1G")
      (footprint "eagle-import:SOT23-3")
      (fields
        (field (name "DIGIKEY_PART_NUMBER") "BSS84LT1GOSCT-ND")
        (field (name "MANUFACTURER") "ON Semiconductor")
        (field (name "CREATED_BY") "PCBLayout.com")
      )
      (libsource (lib "eagle-import") (part "BSS84LT1G"))
    )
    (comp (ref "Q104")
      (value "BSS84LT1G")
      (footprint "eagle-import:SOT23-3")
      (fields
        (field (name "DIGIKEY_PART_NUMBER") "BSS84LT1GOSCT-ND")
        (field (name "MANUFACTURER") "ON Semiconductor")
        (field (name "CREATED_BY") "PCBLayout.com")
      )
      (libsource (lib "eagle-import") (part "BSS84LT1G"))
    )
    (comp (ref "Q105")
      (value "2N7002,215")
      (footprint "eagle-import:SOT23-3")
      (fields
        (field (name "DIGIKEY_PART_NUMBER") "1727-2764-1-ND")
        (field (name "MANUFACTURER") "Nexperia USA Inc.")
        (field (name "CREATED_BY") "PCBLayout.com")
      )
      (libsource (lib "eagle-import") (part "2N7002,215"))
    )
    (comp (ref "Q106")
      (value "2N7002,215")
      (footprint "eagle-import:SOT23-3")
      (fields
        (field (name "DIGIKEY_PART_NUMBER") "1727-2764-1-ND")
        (field (name "MANUFACTURER") "Nexperia USA Inc.")
        (field (name "CREATED_BY") "PCBLayout.com")
      )
      (libsource (lib "eagle-import") (part "2N7002,215"))
    )
    (comp (ref "Q107")
      (value "BSS84LT1G")
      (footprint "eagle-import:SOT23-3")
      (fields
        (field (name "DIGIKEY_PART_NUMBER") "BSS84LT1GOSCT-ND")
        (field (name "MANUFACTURER") "ON Semiconductor")
        (field (name "CREATED_BY") "PCBLayout.com")
      )
      (libsource (lib "eagle-import") (part "BSS84LT1G"))
    )
    (comp (ref "Q108")
      (value "BSS84LT1G")
      (footprint "eagle-import:SOT23-3")
      (fields
        (field (name "DIGIKEY_PART_NUMBER") "BSS84LT1GOSCT-ND")
        (field (name "MANUFACTURER") "ON Semiconductor")
        (field (name "CREATED_BY") "PCBLayout.com")
      )
      (libsource (lib "eagle-import") (part "BSS84LT1G"))
    )
    (comp (ref "Q109")
      (value "2N7002,215")
      (footprint "eagle-import:SOT23-3")
      (fields
        (field (name "DIGIKEY_PART_NUMBER") "1727-2764-1-ND")
        (field (name "MANUFACTURER") "Nexperia USA Inc.")
        (field (name "CREATED_BY") "PCBLayout.com")
      )
      (libsource (lib "eagle-import") (part "2N7002,215"))
    )
    (comp (ref "Q110")
      (value "2N7002,215")
      (footprint "eagle-import:SOT23-3")
      (fields
        (field (name "DIGIKEY_PART_NUMBER") "1727-2764-1-ND")
        (field (name "MANUFACTURER") "Nexperia USA Inc.")
        (field (name "CREATED_BY") "PCBLayout.com")
      )
      (libsource (lib "eagle-import") (part "2N7002,215"))
    )
    (comp (ref "Q111")
      (value "BSS84LT1G")
      (footprint "eagle-import:SOT23-3")
      (fields
        (field (name "DIGIKEY_PART_NUMBER") "BSS84LT1GOSCT-ND")
        (field (name "MANUFACTURER") "ON Semiconductor")
        (field (name "CREATED_BY") "PCBLayout.com")
      )
      (libsource (lib "eagle-import") (part "BSS84LT1G"))
    )
    (comp (ref "Q112")
      (value "BSS84LT1G")
      (footprint "eagle-import:SOT23-3")
      (fields
        (field (name "DIGIKEY_PART_NUMBER") "BSS84LT1GOSCT-ND")
        (field (name "MANUFACTURER") "ON Semiconductor")
        (field (name "CREATED_BY") "PCBLayout.com")
      )
      (libsource (lib "eagle-import") (part "BSS84LT1G"))
    )
    (comp (ref "Q113")
      (value "2N7002,215")
      (footprint "eagle-import:SOT23-3")
      (fields
        (field (name "DIGIKEY_PART_NUMBER") "1727-2764-1-ND")
        (field (name "MANUFACTURER") "Nexperia USA Inc.")
        (field (name "CREATED_BY") "PCBLayout.com")
      )
      (libsource (lib "eagle-import") (part "2N7002,215"))
    )
    (comp (ref "Q114")
      (value "2N7002,215")
      (footprint "eagle-import:SOT23-3")
      (fields
        (field (name "DIGIKEY_PART_NUMBER") "1727-2764-1-ND")
        (field (name "MANUFACTURER") "Nexperia USA Inc.")
        (field (name "CREATED_BY") "PCBLayout.com")
      )
      (libsource (lib "eagle-import") (part "2N7002,215"))
    )
    (comp (ref "Q115")
      (value "BSS84LT1G")
      (footprint "eagle-import:SOT23-3")
      (fields
        (field (name "DIGIKEY_PART_NUMBER") "BSS84LT1GOSCT-ND")
        (field (name "MANUFACTURER") "ON Semiconductor")
        (field (name "CREATED_BY") "PCBLayout.com")
      )
      (libsource (lib "eagle-import") (part "BSS84LT1G"))
    )
    (comp (ref "Q116")
      (value "BSS84LT1G")
      (footprint "eagle-import:SOT23-3")
      (fields
        (field (name "DIGIKEY_PART_NUMBER") "BSS84LT1GOSCT-ND")
        (field (name "MANUFACTURER") "ON Semiconductor")
        (field (name "CREATED_BY") "PCBLayout.com")
      )
      (libsource (lib "eagle-import") (part "BSS84LT1G"))
    )
    (comp (ref "Q117")
      (value "2N7002,215")
      (footprint "eagle-import:SOT23-3")
      (fields
        (field (name "DIGIKEY_PART_NUMBER") "1727-2764-1-ND")
        (field (name "MANUFACTURER") "Nexperia USA Inc.")
        (field (name "CREATED_BY") "PCBLayout.com")
      )
      (libsource (lib "eagle-import") (part "2N7002,215"))
    )
    (comp (ref "Q118")
      (value "2N7002,215")
      (footprint "eagle-import:SOT23-3")
      (fields
        (field (name "DIGIKEY_PART_NUMBER") "1727-2764-1-ND")
        (field (name "MANUFACTURER") "Nexperia USA Inc.")
        (field (name "CREATED_BY") "PCBLayout.com")
      )
      (libsource (lib "eagle-import") (part "2N7002,215"))
    )
    (comp (ref "Q119")
      (value "BSS84LT1G")
      (footprint "eagle-import:SOT23-3")
      (fields
        (field (name "DIGIKEY_PART_NUMBER") "BSS84LT1GOSCT-ND")
        (field (name "MANUFACTURER") "ON Semiconductor")
        (field (name "CREATED_BY") "PCBLayout.com")
      )
      (libsource (lib "eagle-import") (part "BSS84LT1G"))
    )
    (comp (ref "Q120")
      (value "BSS84LT1G")
      (footprint "eagle-import:SOT23-3")
      (fields
        (field (name "DIGIKEY_PART_NUMBER") "BSS84LT1GOSCT-ND")
        (field (name "MANUFACTURER") "ON Semiconductor")
        (field (name "CREATED_BY") "PCBLayout.com")
      )
      (libsource (lib "eagle-import") (part "BSS84LT1G"))
    )
    (comp (ref "Q121")
      (value "2N7002,215")
      (footprint "eagle-import:SOT23-3")
      (fields
        (field (name "DIGIKEY_PART_NUMBER") "1727-2764-1-ND")
        (field (name "MANUFACTURER") "Nexperia USA Inc.")
        (field (name "CREATED_BY") "PCBLayout.com")
      )
      (libsource (lib "eagle-import") (part "2N7002,215"))
    )
    (comp (ref "Q122")
      (value "2N7002,215")
      (footprint "eagle-import:SOT23-3")
      (fields
        (field (name "DIGIKEY_PART_NUMBER") "1727-2764-1-ND")
        (field (name "MANUFACTURER") "Nexperia USA Inc.")
        (field (name "CREATED_BY") "PCBLayout.com")
      )
      (libsource (lib "eagle-import") (part "2N7002,215"))
    )
    (comp (ref "Q123")
      (value "BSS84LT1G")
      (footprint "eagle-import:SOT23-3")
      (fields
        (field (name "DIGIKEY_PART_NUMBER") "BSS84LT1GOSCT-ND")
        (field (name "MANUFACTURER") "ON Semiconductor")
        (field (name "CREATED_BY") "PCBLayout.com")
      )
      (libsource (lib "eagle-import") (part "BSS84LT1G"))
    )
    (comp (ref "Q124")
      (value "BSS84LT1G")
      (footprint "eagle-import:SOT23-3")
      (fields
        (field (name "DIGIKEY_PART_NUMBER") "BSS84LT1GOSCT-ND")
        (field (name "MANUFACTURER") "ON Semiconductor")
        (field (name "CREATED_BY") "PCBLayout.com")
      )
      (libsource (lib "eagle-import") (part "BSS84LT1G"))
    )
    (comp (ref "Q125")
      (value "2N7002,215")
      (footprint "eagle-import:SOT23-3")
      (fields
        (field (name "DIGIKEY_PART_NUMBER") "1727-2764-1-ND")
        (field (name "MANUFACTURER") "Nexperia USA Inc.")
        (field (name "CREATED_BY") "PCBLayout.com")
      )
      (libsource (lib "eagle-import") (part "2N7002,215"))
    )
    (comp (ref "Q126")
      (value "2N7002,215")
      (footprint "eagle-import:SOT23-3")
      (fields
        (field (name "DIGIKEY_PART_NUMBER") "1727-2764-1-ND")
        (field (name "MANUFACTURER") "Nexperia USA Inc.")
        (field (name "CREATED_BY") "PCBLayout.com")
      )
      (libsource (lib "eagle-import") (part "2N7002,215"))
    )
    (comp (ref "Q127")
      (value "BSS84LT1G")
      (footprint "eagle-import:SOT23-3")
      (fields
        (field (name "DIGIKEY_PART_NUMBER") "BSS84LT1GOSCT-ND")
        (field (name "MANUFACTURER") "ON Semiconductor")
        (field (name "CREATED_BY") "PCBLayout.com")
      )
      (libsource (lib "eagle-import") (part "BSS84LT1G"))
    )
    (comp (ref "Q128")
      (value "BSS84LT1G")
      (footprint "eagle-import:SOT23-3")
      (fields
        (field (name "DIGIKEY_PART_NUMBER") "BSS84LT1GOSCT-ND")
        (field (name "MANUFACTURER") "ON Semiconductor")
        (field (name "CREATED_BY") "PCBLayout.com")
      )
      (libsource (lib "eagle-import") (part "BSS84LT1G"))
    )
    (comp (ref "Q129")
      (value "2N7002,215")
      (footprint "eagle-import:SOT23-3")
      (fields
        (field (name "DIGIKEY_PART_NUMBER") "1727-2764-1-ND")
        (field (name "MANUFACTURER") "Nexperia USA Inc.")
        (field (name "CREATED_BY") "PCBLayout.com")
      )
      (libsource (lib "eagle-import") (part "2N7002,215"))
    )
    (comp (ref "Q130")
      (value "2N7002,215")
      (footprint "eagle-import:SOT23-3")
      (fields
        (field (name "DIGIKEY_PART_NUMBER") "1727-2764-1-ND")
        (field (name "MANUFACTURER") "Nexperia USA Inc.")
        (field (name "CREATED_BY") "PCBLayout.com")
      )
      (libsource (lib "eagle-import") (part "2N7002,215"))
    )
    (comp (ref "Q131")
      (value "BSS84LT1G")
      (footprint "eagle-import:SOT23-3")
      (fields
        (field (name "DIGIKEY_PART_NUMBER") "BSS84LT1GOSCT-ND")
        (field (name "MANUFACTURER") "ON Semiconductor")
        (field (name "CREATED_BY") "PCBLayout.com")
      )
      (libsource (lib "eagle-import") (part "BSS84LT1G"))
    )
    (comp (ref "Q132")
      (value "BSS84LT1G")
      (footprint "eagle-import:SOT23-3")
      (fields
        (field (name "DIGIKEY_PART_NUMBER") "BSS84LT1GOSCT-ND")
        (field (name "MANUFACTURER") "ON Semiconductor")
        (field (name "CREATED_BY") "PCBLayout.com")
      )
      (libsource (lib "eagle-import") (part "BSS84LT1G"))
    )
    (comp (ref "Q133")
      (value "2N7002,215")
      (footprint "eagle-import:SOT23-3")
      (fields
        (field (name "DIGIKEY_PART_NUMBER") "1727-2764-1-ND")
        (field (name "MANUFACTURER") "Nexperia USA Inc.")
        (field (name "CREATED_BY") "PCBLayout.com")
      )
      (libsource (lib "eagle-import") (part "2N7002,215"))
    )
    (comp (ref "Q134")
      (value "2N7002,215")
      (footprint "eagle-import:SOT23-3")
      (fields
        (field (name "DIGIKEY_PART_NUMBER") "1727-2764-1-ND")
        (field (name "MANUFACTURER") "Nexperia USA Inc.")
        (field (name "CREATED_BY") "PCBLayout.com")
      )
      (libsource (lib "eagle-import") (part "2N7002,215"))
    )
    (comp (ref "Q135")
      (value "BSS84LT1G")
      (footprint "eagle-import:SOT23-3")
      (fields
        (field (name "DIGIKEY_PART_NUMBER") "BSS84LT1GOSCT-ND")
        (field (name "MANUFACTURER") "ON Semiconductor")
        (field (name "CREATED_BY") "PCBLayout.com")
      )
      (libsource (lib "eagle-import") (part "BSS84LT1G"))
    )
    (comp (ref "Q136")
      (value "BSS84LT1G")
      (footprint "eagle-import:SOT23-3")
      (fields
        (field (name "DIGIKEY_PART_NUMBER") "BSS84LT1GOSCT-ND")
        (field (name "MANUFACTURER") "ON Semiconductor")
        (field (name "CREATED_BY") "PCBLayout.com")
      )
      (libsource (lib "eagle-import") (part "BSS84LT1G"))
    )
    (comp (ref "Q137")
      (value "2N7002,215")
      (footprint "eagle-import:SOT23-3")
      (fields
        (field (name "DIGIKEY_PART_NUMBER") "1727-2764-1-ND")
        (field (name "MANUFACTURER") "Nexperia USA Inc.")
        (field (name "CREATED_BY") "PCBLayout.com")
      )
      (libsource (lib "eagle-import") (part "2N7002,215"))
    )
    (comp (ref "Q138")
      (value "2N7002,215")
      (footprint "eagle-import:SOT23-3")
      (fields
        (field (name "DIGIKEY_PART_NUMBER") "1727-2764-1-ND")
        (field (name "MANUFACTURER") "Nexperia USA Inc.")
        (field (name "CREATED_BY") "PCBLayout.com")
      )
      (libsource (lib "eagle-import") (part "2N7002,215"))
    )
    (comp (ref "Q139")
      (value "BSS84LT1G")
      (footprint "eagle-import:SOT23-3")
      (fields
        (field (name "DIGIKEY_PART_NUMBER") "BSS84LT1GOSCT-ND")
        (field (name "MANUFACTURER") "ON Semiconductor")
        (field (name "CREATED_BY") "PCBLayout.com")
      )
      (libsource (lib "eagle-import") (part "BSS84LT1G"))
    )
    (comp (ref "Q140")
      (value "BSS84LT1G")
      (footprint "eagle-import:SOT23-3")
      (fields
        (field (name "DIGIKEY_PART_NUMBER") "BSS84LT1GOSCT-ND")
        (field (name "MANUFACTURER") "ON Semiconductor")
        (field (name "CREATED_BY") "PCBLayout.com")
      )
      (libsource (lib "eagle-import") (part "BSS84LT1G"))
    )
    (comp (ref "Q141")
      (value "2N7002,215")
      (footprint "eagle-import:SOT23-3")
      (fields
        (field (name "DIGIKEY_PART_NUMBER") "1727-2764-1-ND")
        (field (name "MANUFACTURER") "Nexperia USA Inc.")
        (field (name "CREATED_BY") "PCBLayout.com")
      )
      (libsource (lib "eagle-import") (part "2N7002,215"))
    )
    (comp (ref "Q142")
      (value "2N7002,215")
      (footprint "eagle-import:SOT23-3")
      (fields
        (field (name "DIGIKEY_PART_NUMBER") "1727-2764-1-ND")
        (field (name "MANUFACTURER") "Nexperia USA Inc.")
        (field (name "CREATED_BY") "PCBLayout.com")
      )
      (libsource (lib "eagle-import") (part "2N7002,215"))
    )
    (comp (ref "Q143")
      (value "BSS84LT1G")
      (footprint "eagle-import:SOT23-3")
      (fields
        (field (name "DIGIKEY_PART_NUMBER") "BSS84LT1GOSCT-ND")
        (field (name "MANUFACTURER") "ON Semiconductor")
        (field (name "CREATED_BY") "PCBLayout.com")
      )
      (libsource (lib "eagle-import") (part "BSS84LT1G"))
    )
    (comp (ref "Q144")
      (value "BSS84LT1G")
      (footprint "eagle-import:SOT23-3")
      (fields
        (field (name "DIGIKEY_PART_NUMBER") "BSS84LT1GOSCT-ND")
        (field (name "MANUFACTURER") "ON Semiconductor")
        (field (name "CREATED_BY") "PCBLayout.com")
      )
      (libsource (lib "eagle-import") (part "BSS84LT1G"))
    )
    (comp (ref "Q145")
      (value "2N7002,215")
      (footprint "eagle-import:SOT23-3")
      (fields
        (field (name "DIGIKEY_PART_NUMBER") "1727-2764-1-ND")
        (field (name "MANUFACTURER") "Nexperia USA Inc.")
        (field (name "CREATED_BY") "PCBLayout.com")
      )
      (libsource (lib "eagle-import") (part "2N7002,215"))
    )
    (comp (ref "Q146")
      (value "2N7002,215")
      (footprint "eagle-import:SOT23-3")
      (fields
        (field (name "DIGIKEY_PART_NUMBER") "1727-2764-1-ND")
        (field (name "MANUFACTURER") "Nexperia USA Inc.")
        (field (name "CREATED_BY") "PCBLayout.com")
      )
      (libsource (lib "eagle-import") (part "2N7002,215"))
    )
    (comp (ref "Q147")
      (value "BSS84LT1G")
      (footprint "eagle-import:SOT23-3")
      (fields
        (field (name "DIGIKEY_PART_NUMBER") "BSS84LT1GOSCT-ND")
        (field (name "MANUFACTURER") "ON Semiconductor")
        (field (name "CREATED_BY") "PCBLayout.com")
      )
      (libsource (lib "eagle-import") (part "BSS84LT1G"))
    )
    (comp (ref "Q148")
      (value "BSS84LT1G")
      (footprint "eagle-import:SOT23-3")
      (fields
        (field (name "DIGIKEY_PART_NUMBER") "BSS84LT1GOSCT-ND")
        (field (name "MANUFACTURER") "ON Semiconductor")
        (field (name "CREATED_BY") "PCBLayout.com")
      )
      (libsource (lib "eagle-import") (part "BSS84LT1G"))
    )
    (comp (ref "Q149")
      (value "2N7002,215")
      (footprint "eagle-import:SOT23-3")
      (fields
        (field (name "DIGIKEY_PART_NUMBER") "1727-2764-1-ND")
        (field (name "MANUFACTURER") "Nexperia USA Inc.")
        (field (name "CREATED_BY") "PCBLayout.com")
      )
      (libsource (lib "eagle-import") (part "2N7002,215"))
    )
    (comp (ref "Q150")
      (value "2N7002,215")
      (footprint "eagle-import:SOT23-3")
      (fields
        (field (name "DIGIKEY_PART_NUMBER") "1727-2764-1-ND")
        (field (name "MANUFACTURER") "Nexperia USA Inc.")
        (field (name "CREATED_BY") "PCBLayout.com")
      )
      (libsource (lib "eagle-import") (part "2N7002,215"))
    )
    (comp (ref "Q151")
      (value "BSS84LT1G")
      (footprint "eagle-import:SOT23-3")
      (fields
        (field (name "DIGIKEY_PART_NUMBER") "BSS84LT1GOSCT-ND")
        (field (name "MANUFACTURER") "ON Semiconductor")
        (field (name "CREATED_BY") "PCBLayout.com")
      )
      (libsource (lib "eagle-import") (part "BSS84LT1G"))
    )
    (comp (ref "Q152")
      (value "BSS84LT1G")
      (footprint "eagle-import:SOT23-3")
      (fields
        (field (name "DIGIKEY_PART_NUMBER") "BSS84LT1GOSCT-ND")
        (field (name "MANUFACTURER") "ON Semiconductor")
        (field (name "CREATED_BY") "PCBLayout.com")
      )
      (libsource (lib "eagle-import") (part "BSS84LT1G"))
    )
    (comp (ref "Q153")
      (value "2N7002,215")
      (footprint "eagle-import:SOT23-3")
      (fields
        (field (name "DIGIKEY_PART_NUMBER") "1727-2764-1-ND")
        (field (name "MANUFACTURER") "Nexperia USA Inc.")
        (field (name "CREATED_BY") "PCBLayout.com")
      )
      (libsource (lib "eagle-import") (part "2N7002,215"))
    )
    (comp (ref "Q154")
      (value "2N7002,215")
      (footprint "eagle-import:SOT23-3")
      (fields
        (field (name "DIGIKEY_PART_NUMBER") "1727-2764-1-ND")
        (field (name "MANUFACTURER") "Nexperia USA Inc.")
        (field (name "CREATED_BY") "PCBLayout.com")
      )
      (libsource (lib "eagle-import") (part "2N7002,215"))
    )
    (comp (ref "Q155")
      (value "BSS84LT1G")
      (footprint "eagle-import:SOT23-3")
      (fields
        (field (name "DIGIKEY_PART_NUMBER") "BSS84LT1GOSCT-ND")
        (field (name "MANUFACTURER") "ON Semiconductor")
        (field (name "CREATED_BY") "PCBLayout.com")
      )
      (libsource (lib "eagle-import") (part "BSS84LT1G"))
    )
    (comp (ref "Q156")
      (value "BSS84LT1G")
      (footprint "eagle-import:SOT23-3")
      (fields
        (field (name "DIGIKEY_PART_NUMBER") "BSS84LT1GOSCT-ND")
        (field (name "MANUFACTURER") "ON Semiconductor")
        (field (name "CREATED_BY") "PCBLayout.com")
      )
      (libsource (lib "eagle-import") (part "BSS84LT1G"))
    )
    (comp (ref "Q157")
      (value "2N7002,215")
      (footprint "eagle-import:SOT23-3")
      (fields
        (field (name "DIGIKEY_PART_NUMBER") "1727-2764-1-ND")
        (field (name "MANUFACTURER") "Nexperia USA Inc.")
        (field (name "CREATED_BY") "PCBLayout.com")
      )
      (libsource (lib "eagle-import") (part "2N7002,215"))
    )
    (comp (ref "Q158")
      (value "2N7002,215")
      (footprint "eagle-import:SOT23-3")
      (fields
        (field (name "DIGIKEY_PART_NUMBER") "1727-2764-1-ND")
        (field (name "MANUFACTURER") "Nexperia USA Inc.")
        (field (name "CREATED_BY") "PCBLayout.com")
      )
      (libsource (lib "eagle-import") (part "2N7002,215"))
    )
    (comp (ref "Q159")
      (value "BSS84LT1G")
      (footprint "eagle-import:SOT23-3")
      (fields
        (field (name "DIGIKEY_PART_NUMBER") "BSS84LT1GOSCT-ND")
        (field (name "MANUFACTURER") "ON Semiconductor")
        (field (name "CREATED_BY") "PCBLayout.com")
      )
      (libsource (lib "eagle-import") (part "BSS84LT1G"))
    )
    (comp (ref "Q160")
      (value "BSS84LT1G")
      (footprint "eagle-import:SOT23-3")
      (fields
        (field (name "DIGIKEY_PART_NUMBER") "BSS84LT1GOSCT-ND")
        (field (name "MANUFACTURER") "ON Semiconductor")
        (field (name "CREATED_BY") "PCBLayout.com")
      )
      (libsource (lib "eagle-import") (part "BSS84LT1G"))
    )
    (comp (ref "Q161")
      (value "2N7002,215")
      (footprint "eagle-import:SOT23-3")
      (fields
        (field (name "DIGIKEY_PART_NUMBER") "1727-2764-1-ND")
        (field (name "MANUFACTURER") "Nexperia USA Inc.")
        (field (name "CREATED_BY") "PCBLayout.com")
      )
      (libsource (lib "eagle-import") (part "2N7002,215"))
    )
    (comp (ref "Q162")
      (value "2N7002,215")
      (footprint "eagle-import:SOT23-3")
      (fields
        (field (name "DIGIKEY_PART_NUMBER") "1727-2764-1-ND")
        (field (name "MANUFACTURER") "Nexperia USA Inc.")
        (field (name "CREATED_BY") "PCBLayout.com")
      )
      (libsource (lib "eagle-import") (part "2N7002,215"))
    )
    (comp (ref "Q163")
      (value "BSS84LT1G")
      (footprint "eagle-import:SOT23-3")
      (fields
        (field (name "DIGIKEY_PART_NUMBER") "BSS84LT1GOSCT-ND")
        (field (name "MANUFACTURER") "ON Semiconductor")
        (field (name "CREATED_BY") "PCBLayout.com")
      )
      (libsource (lib "eagle-import") (part "BSS84LT1G"))
    )
    (comp (ref "Q164")
      (value "BSS84LT1G")
      (footprint "eagle-import:SOT23-3")
      (fields
        (field (name "DIGIKEY_PART_NUMBER") "BSS84LT1GOSCT-ND")
        (field (name "MANUFACTURER") "ON Semiconductor")
        (field (name "CREATED_BY") "PCBLayout.com")
      )
      (libsource (lib "eagle-import") (part "BSS84LT1G"))
    )
    (comp (ref "Q165")
      (value "2N7002,215")
      (footprint "eagle-import:SOT23-3")
      (fields
        (field (name "DIGIKEY_PART_NUMBER") "1727-2764-1-ND")
        (field (name "MANUFACTURER") "Nexperia USA Inc.")
        (field (name "CREATED_BY") "PCBLayout.com")
      )
      (libsource (lib "eagle-import") (part "2N7002,215"))
    )
    (comp (ref "Q166")
      (value "2N7002,215")
      (footprint "eagle-import:SOT23-3")
      (fields
        (field (name "DIGIKEY_PART_NUMBER") "1727-2764-1-ND")
        (field (name "MANUFACTURER") "Nexperia USA Inc.")
        (field (name "CREATED_BY") "PCBLayout.com")
      )
      (libsource (lib "eagle-import") (part "2N7002,215"))
    )
    (comp (ref "Q167")
      (value "BSS84LT1G")
      (footprint "eagle-import:SOT23-3")
      (fields
        (field (name "DIGIKEY_PART_NUMBER") "BSS84LT1GOSCT-ND")
        (field (name "MANUFACTURER") "ON Semiconductor")
        (field (name "CREATED_BY") "PCBLayout.com")
      )
      (libsource (lib "eagle-import") (part "BSS84LT1G"))
    )
    (comp (ref "Q168")
      (value "BSS84LT1G")
      (footprint "eagle-import:SOT23-3")
      (fields
        (field (name "DIGIKEY_PART_NUMBER") "BSS84LT1GOSCT-ND")
        (field (name "MANUFACTURER") "ON Semiconductor")
        (field (name "CREATED_BY") "PCBLayout.com")
      )
      (libsource (lib "eagle-import") (part "BSS84LT1G"))
    )
    (comp (ref "Q169")
      (value "2N7002,215")
      (footprint "eagle-import:SOT23-3")
      (fields
        (field (name "DIGIKEY_PART_NUMBER") "1727-2764-1-ND")
        (field (name "MANUFACTURER") "Nexperia USA Inc.")
        (field (name "CREATED_BY") "PCBLayout.com")
      )
      (libsource (lib "eagle-import") (part "2N7002,215"))
    )
    (comp (ref "Q170")
      (value "2N7002,215")
      (footprint "eagle-import:SOT23-3")
      (fields
        (field (name "DIGIKEY_PART_NUMBER") "1727-2764-1-ND")
        (field (name "MANUFACTURER") "Nexperia USA Inc.")
        (field (name "CREATED_BY") "PCBLayout.com")
      )
      (libsource (lib "eagle-import") (part "2N7002,215"))
    )
    (comp (ref "Q171")
      (value "BSS84LT1G")
      (footprint "eagle-import:SOT23-3")
      (fields
        (field (name "DIGIKEY_PART_NUMBER") "BSS84LT1GOSCT-ND")
        (field (name "MANUFACTURER") "ON Semiconductor")
        (field (name "CREATED_BY") "PCBLayout.com")
      )
      (libsource (lib "eagle-import") (part "BSS84LT1G"))
    )
    (comp (ref "Q172")
      (value "BSS84LT1G")
      (footprint "eagle-import:SOT23-3")
      (fields
        (field (name "DIGIKEY_PART_NUMBER") "BSS84LT1GOSCT-ND")
        (field (name "MANUFACTURER") "ON Semiconductor")
        (field (name "CREATED_BY") "PCBLayout.com")
      )
      (libsource (lib "eagle-import") (part "BSS84LT1G"))
    )
    (comp (ref "Q173")
      (value "2N7002,215")
      (footprint "eagle-import:SOT23-3")
      (fields
        (field (name "DIGIKEY_PART_NUMBER") "1727-2764-1-ND")
        (field (name "MANUFACTURER") "Nexperia USA Inc.")
        (field (name "CREATED_BY") "PCBLayout.com")
      )
      (libsource (lib "eagle-import") (part "2N7002,215"))
    )
    (comp (ref "Q174")
      (value "2N7002,215")
      (footprint "eagle-import:SOT23-3")
      (fields
        (field (name "DIGIKEY_PART_NUMBER") "1727-2764-1-ND")
        (field (name "MANUFACTURER") "Nexperia USA Inc.")
        (field (name "CREATED_BY") "PCBLayout.com")
      )
      (libsource (lib "eagle-import") (part "2N7002,215"))
    )
    (comp (ref "Q175")
      (value "BSS84LT1G")
      (footprint "eagle-import:SOT23-3")
      (fields
        (field (name "DIGIKEY_PART_NUMBER") "BSS84LT1GOSCT-ND")
        (field (name "MANUFACTURER") "ON Semiconductor")
        (field (name "CREATED_BY") "PCBLayout.com")
      )
      (libsource (lib "eagle-import") (part "BSS84LT1G"))
    )
    (comp (ref "Q176")
      (value "BSS84LT1G")
      (footprint "eagle-import:SOT23-3")
      (fields
        (field (name "DIGIKEY_PART_NUMBER") "BSS84LT1GOSCT-ND")
        (field (name "MANUFACTURER") "ON Semiconductor")
        (field (name "CREATED_BY") "PCBLayout.com")
      )
      (libsource (lib "eagle-import") (part "BSS84LT1G"))
    )
    (comp (ref "Q177")
      (value "2N7002,215")
      (footprint "eagle-import:SOT23-3")
      (fields
        (field (name "DIGIKEY_PART_NUMBER") "1727-2764-1-ND")
        (field (name "MANUFACTURER") "Nexperia USA Inc.")
        (field (name "CREATED_BY") "PCBLayout.com")
      )
      (libsource (lib "eagle-import") (part "2N7002,215"))
    )
    (comp (ref "Q178")
      (value "2N7002,215")
      (footprint "eagle-import:SOT23-3")
      (fields
        (field (name "DIGIKEY_PART_NUMBER") "1727-2764-1-ND")
        (field (name "MANUFACTURER") "Nexperia USA Inc.")
        (field (name "CREATED_BY") "PCBLayout.com")
      )
      (libsource (lib "eagle-import") (part "2N7002,215"))
    )
    (comp (ref "Q179")
      (value "BSS84LT1G")
      (footprint "eagle-import:SOT23-3")
      (fields
        (field (name "DIGIKEY_PART_NUMBER") "BSS84LT1GOSCT-ND")
        (field (name "MANUFACTURER") "ON Semiconductor")
        (field (name "CREATED_BY") "PCBLayout.com")
      )
      (libsource (lib "eagle-import") (part "BSS84LT1G"))
    )
    (comp (ref "Q180")
      (value "BSS84LT1G")
      (footprint "eagle-import:SOT23-3")
      (fields
        (field (name "DIGIKEY_PART_NUMBER") "BSS84LT1GOSCT-ND")
        (field (name "MANUFACTURER") "ON Semiconductor")
        (field (name "CREATED_BY") "PCBLayout.com")
      )
      (libsource (lib "eagle-import") (part "BSS84LT1G"))
    )
    (comp (ref "Q181")
      (value "2N7002,215")
      (footprint "eagle-import:SOT23-3")
      (fields
        (field (name "DIGIKEY_PART_NUMBER") "1727-2764-1-ND")
        (field (name "MANUFACTURER") "Nexperia USA Inc.")
        (field (name "CREATED_BY") "PCBLayout.com")
      )
      (libsource (lib "eagle-import") (part "2N7002,215"))
    )
    (comp (ref "Q182")
      (value "2N7002,215")
      (footprint "eagle-import:SOT23-3")
      (fields
        (field (name "DIGIKEY_PART_NUMBER") "1727-2764-1-ND")
        (field (name "MANUFACTURER") "Nexperia USA Inc.")
        (field (name "CREATED_BY") "PCBLayout.com")
      )
      (libsource (lib "eagle-import") (part "2N7002,215"))
    )
    (comp (ref "Q183")
      (value "BSS84LT1G")
      (footprint "eagle-import:SOT23-3")
      (fields
        (field (name "DIGIKEY_PART_NUMBER") "BSS84LT1GOSCT-ND")
        (field (name "MANUFACTURER") "ON Semiconductor")
        (field (name "CREATED_BY") "PCBLayout.com")
      )
      (libsource (lib "eagle-import") (part "BSS84LT1G"))
    )
    (comp (ref "Q184")
      (value "BSS84LT1G")
      (footprint "eagle-import:SOT23-3")
      (fields
        (field (name "DIGIKEY_PART_NUMBER") "BSS84LT1GOSCT-ND")
        (field (name "MANUFACTURER") "ON Semiconductor")
        (field (name "CREATED_BY") "PCBLayout.com")
      )
      (libsource (lib "eagle-import") (part "BSS84LT1G"))
    )
    (comp (ref "Q185")
      (value "2N7002,215")
      (footprint "eagle-import:SOT23-3")
      (fields
        (field (name "DIGIKEY_PART_NUMBER") "1727-2764-1-ND")
        (field (name "MANUFACTURER") "Nexperia USA Inc.")
        (field (name "CREATED_BY") "PCBLayout.com")
      )
      (libsource (lib "eagle-import") (part "2N7002,215"))
    )
    (comp (ref "Q186")
      (value "2N7002,215")
      (footprint "eagle-import:SOT23-3")
      (fields
        (field (name "DIGIKEY_PART_NUMBER") "1727-2764-1-ND")
        (field (name "MANUFACTURER") "Nexperia USA Inc.")
        (field (name "CREATED_BY") "PCBLayout.com")
      )
      (libsource (lib "eagle-import") (part "2N7002,215"))
    )
    (comp (ref "Q187")
      (value "BSS84LT1G")
      (footprint "eagle-import:SOT23-3")
      (fields
        (field (name "DIGIKEY_PART_NUMBER") "BSS84LT1GOSCT-ND")
        (field (name "MANUFACTURER") "ON Semiconductor")
        (field (name "CREATED_BY") "PCBLayout.com")
      )
      (libsource (lib "eagle-import") (part "BSS84LT1G"))
    )
    (comp (ref "Q188")
      (value "BSS84LT1G")
      (footprint "eagle-import:SOT23-3")
      (fields
        (field (name "DIGIKEY_PART_NUMBER") "BSS84LT1GOSCT-ND")
        (field (name "MANUFACTURER") "ON Semiconductor")
        (field (name "CREATED_BY") "PCBLayout.com")
      )
      (libsource (lib "eagle-import") (part "BSS84LT1G"))
    )
    (comp (ref "Q189")
      (value "2N7002,215")
      (footprint "eagle-import:SOT23-3")
      (fields
        (field (name "DIGIKEY_PART_NUMBER") "1727-2764-1-ND")
        (field (name "MANUFACTURER") "Nexperia USA Inc.")
        (field (name "CREATED_BY") "PCBLayout.com")
      )
      (libsource (lib "eagle-import") (part "2N7002,215"))
    )
    (comp (ref "Q190")
      (value "2N7002,215")
      (footprint "eagle-import:SOT23-3")
      (fields
        (field (name "DIGIKEY_PART_NUMBER") "1727-2764-1-ND")
        (field (name "MANUFACTURER") "Nexperia USA Inc.")
        (field (name "CREATED_BY") "PCBLayout.com")
      )
      (libsource (lib "eagle-import") (part "2N7002,215"))
    )
    (comp (ref "Q191")
      (value "BSS84LT1G")
      (footprint "eagle-import:SOT23-3")
      (fields
        (field (name "DIGIKEY_PART_NUMBER") "BSS84LT1GOSCT-ND")
        (field (name "MANUFACTURER") "ON Semiconductor")
        (field (name "CREATED_BY") "PCBLayout.com")
      )
      (libsource (lib "eagle-import") (part "BSS84LT1G"))
    )
    (comp (ref "Q192")
      (value "BSS84LT1G")
      (footprint "eagle-import:SOT23-3")
      (fields
        (field (name "DIGIKEY_PART_NUMBER") "BSS84LT1GOSCT-ND")
        (field (name "MANUFACTURER") "ON Semiconductor")
        (field (name "CREATED_BY") "PCBLayout.com")
      )
      (libsource (lib "eagle-import") (part "BSS84LT1G"))
    )
    (comp (ref "Q193")
      (value "2N7002,215")
      (footprint "eagle-import:SOT23-3")
      (fields
        (field (name "DIGIKEY_PART_NUMBER") "1727-2764-1-ND")
        (field (name "MANUFACTURER") "Nexperia USA Inc.")
        (field (name "CREATED_BY") "PCBLayout.com")
      )
      (libsource (lib "eagle-import") (part "2N7002,215"))
    )
    (comp (ref "Q194")
      (value "2N7002,215")
      (footprint "eagle-import:SOT23-3")
      (fields
        (field (name "DIGIKEY_PART_NUMBER") "1727-2764-1-ND")
        (field (name "MANUFACTURER") "Nexperia USA Inc.")
        (field (name "CREATED_BY") "PCBLayout.com")
      )
      (libsource (lib "eagle-import") (part "2N7002,215"))
    )
    (comp (ref "Q195")
      (value "BSS84LT1G")
      (footprint "eagle-import:SOT23-3")
      (fields
        (field (name "DIGIKEY_PART_NUMBER") "BSS84LT1GOSCT-ND")
        (field (name "MANUFACTURER") "ON Semiconductor")
        (field (name "CREATED_BY") "PCBLayout.com")
      )
      (libsource (lib "eagle-import") (part "BSS84LT1G"))
    )
    (comp (ref "Q196")
      (value "BSS84LT1G")
      (footprint "eagle-import:SOT23-3")
      (fields
        (field (name "DIGIKEY_PART_NUMBER") "BSS84LT1GOSCT-ND")
        (field (name "MANUFACTURER") "ON Semiconductor")
        (field (name "CREATED_BY") "PCBLayout.com")
      )
      (libsource (lib "eagle-import") (part "BSS84LT1G"))
    )
    (comp (ref "Q197")
      (value "2N7002,215")
      (footprint "eagle-import:SOT23-3")
      (fields
        (field (name "DIGIKEY_PART_NUMBER") "1727-2764-1-ND")
        (field (name "MANUFACTURER") "Nexperia USA Inc.")
        (field (name "CREATED_BY") "PCBLayout.com")
      )
      (libsource (lib "eagle-import") (part "2N7002,215"))
    )
    (comp (ref "Q198")
      (value "2N7002,215")
      (footprint "eagle-import:SOT23-3")
      (fields
        (field (name "DIGIKEY_PART_NUMBER") "1727-2764-1-ND")
        (field (name "MANUFACTURER") "Nexperia USA Inc.")
        (field (name "CREATED_BY") "PCBLayout.com")
      )
      (libsource (lib "eagle-import") (part "2N7002,215"))
    )
    (comp (ref "Q199")
      (value "BSS84LT1G")
      (footprint "eagle-import:SOT23-3")
      (fields
        (field (name "DIGIKEY_PART_NUMBER") "BSS84LT1GOSCT-ND")
        (field (name "MANUFACTURER") "ON Semiconductor")
        (field (name "CREATED_BY") "PCBLayout.com")
      )
      (libsource (lib "eagle-import") (part "BSS84LT1G"))
    )
    (comp (ref "Q200")
      (value "BSS84LT1G")
      (footprint "eagle-import:SOT23-3")
      (fields
        (field (name "DIGIKEY_PART_NUMBER") "BSS84LT1GOSCT-ND")
        (field (name "MANUFACTURER") "ON Semiconductor")
        (field (name "CREATED_BY") "PCBLayout.com")
      )
      (libsource (lib "eagle-import") (part "BSS84LT1G"))
    )
    (comp (ref "Q201")
      (value "2N7002,215")
      (footprint "eagle-import:SOT23-3")
      (fields
        (field (name "DIGIKEY_PART_NUMBER") "1727-2764-1-ND")
        (field (name "MANUFACTURER") "Nexperia USA Inc.")
        (field (name "CREATED_BY") "PCBLayout.com")
      )
      (libsource (lib "eagle-import") (part "2N7002,215"))
    )
    (comp (ref "Q202")
      (value "2N7002,215")
      (footprint "eagle-import:SOT23-3")
      (fields
        (field (name "DIGIKEY_PART_NUMBER") "1727-2764-1-ND")
        (field (name "MANUFACTURER") "Nexperia USA Inc.")
        (field (name "CREATED_BY") "PCBLayout.com")
      )
      (libsource (lib "eagle-import") (part "2N7002,215"))
    )
    (comp (ref "Q203")
      (value "BSS84LT1G")
      (footprint "eagle-import:SOT23-3")
      (fields
        (field (name "DIGIKEY_PART_NUMBER") "BSS84LT1GOSCT-ND")
        (field (name "MANUFACTURER") "ON Semiconductor")
        (field (name "CREATED_BY") "PCBLayout.com")
      )
      (libsource (lib "eagle-import") (part "BSS84LT1G"))
    )
    (comp (ref "Q204")
      (value "BSS84LT1G")
      (footprint "eagle-import:SOT23-3")
      (fields
        (field (name "DIGIKEY_PART_NUMBER") "BSS84LT1GOSCT-ND")
        (field (name "MANUFACTURER") "ON Semiconductor")
        (field (name "CREATED_BY") "PCBLayout.com")
      )
      (libsource (lib "eagle-import") (part "BSS84LT1G"))
    )
    (comp (ref "Q205")
      (value "2N7002,215")
      (footprint "eagle-import:SOT23-3")
      (fields
        (field (name "DIGIKEY_PART_NUMBER") "1727-2764-1-ND")
        (field (name "MANUFACTURER") "Nexperia USA Inc.")
        (field (name "CREATED_BY") "PCBLayout.com")
      )
      (libsource (lib "eagle-import") (part "2N7002,215"))
    )
    (comp (ref "Q206")
      (value "2N7002,215")
      (footprint "eagle-import:SOT23-3")
      (fields
        (field (name "DIGIKEY_PART_NUMBER") "1727-2764-1-ND")
        (field (name "MANUFACTURER") "Nexperia USA Inc.")
        (field (name "CREATED_BY") "PCBLayout.com")
      )
      (libsource (lib "eagle-import") (part "2N7002,215"))
    )
    (comp (ref "Q207")
      (value "BSS84LT1G")
      (footprint "eagle-import:SOT23-3")
      (fields
        (field (name "DIGIKEY_PART_NUMBER") "BSS84LT1GOSCT-ND")
        (field (name "MANUFACTURER") "ON Semiconductor")
        (field (name "CREATED_BY") "PCBLayout.com")
      )
      (libsource (lib "eagle-import") (part "BSS84LT1G"))
    )
    (comp (ref "Q208")
      (value "BSS84LT1G")
      (footprint "eagle-import:SOT23-3")
      (fields
        (field (name "DIGIKEY_PART_NUMBER") "BSS84LT1GOSCT-ND")
        (field (name "MANUFACTURER") "ON Semiconductor")
        (field (name "CREATED_BY") "PCBLayout.com")
      )
      (libsource (lib "eagle-import") (part "BSS84LT1G"))
    )
    (comp (ref "Q209")
      (value "2N7002,215")
      (footprint "eagle-import:SOT23-3")
      (fields
        (field (name "DIGIKEY_PART_NUMBER") "1727-2764-1-ND")
        (field (name "MANUFACTURER") "Nexperia USA Inc.")
        (field (name "CREATED_BY") "PCBLayout.com")
      )
      (libsource (lib "eagle-import") (part "2N7002,215"))
    )
    (comp (ref "Q210")
      (value "2N7002,215")
      (footprint "eagle-import:SOT23-3")
      (fields
        (field (name "DIGIKEY_PART_NUMBER") "1727-2764-1-ND")
        (field (name "MANUFACTURER") "Nexperia USA Inc.")
        (field (name "CREATED_BY") "PCBLayout.com")
      )
      (libsource (lib "eagle-import") (part "2N7002,215"))
    )
    (comp (ref "Q211")
      (value "BSS84LT1G")
      (footprint "eagle-import:SOT23-3")
      (fields
        (field (name "DIGIKEY_PART_NUMBER") "BSS84LT1GOSCT-ND")
        (field (name "MANUFACTURER") "ON Semiconductor")
        (field (name "CREATED_BY") "PCBLayout.com")
      )
      (libsource (lib "eagle-import") (part "BSS84LT1G"))
    )
    (comp (ref "Q212")
      (value "BSS84LT1G")
      (footprint "eagle-import:SOT23-3")
      (fields
        (field (name "DIGIKEY_PART_NUMBER") "BSS84LT1GOSCT-ND")
        (field (name "MANUFACTURER") "ON Semiconductor")
        (field (name "CREATED_BY") "PCBLayout.com")
      )
      (libsource (lib "eagle-import") (part "BSS84LT1G"))
    )
    (comp (ref "Q213")
      (value "2N7002,215")
      (footprint "eagle-import:SOT23-3")
      (fields
        (field (name "DIGIKEY_PART_NUMBER") "1727-2764-1-ND")
        (field (name "MANUFACTURER") "Nexperia USA Inc.")
        (field (name "CREATED_BY") "PCBLayout.com")
      )
      (libsource (lib "eagle-import") (part "2N7002,215"))
    )
    (comp (ref "Q214")
      (value "2N7002,215")
      (footprint "eagle-import:SOT23-3")
      (fields
        (field (name "DIGIKEY_PART_NUMBER") "1727-2764-1-ND")
        (field (name "MANUFACTURER") "Nexperia USA Inc.")
        (field (name "CREATED_BY") "PCBLayout.com")
      )
      (libsource (lib "eagle-import") (part "2N7002,215"))
    )
    (comp (ref "Q215")
      (value "BSS84LT1G")
      (footprint "eagle-import:SOT23-3")
      (fields
        (field (name "DIGIKEY_PART_NUMBER") "BSS84LT1GOSCT-ND")
        (field (name "MANUFACTURER") "ON Semiconductor")
        (field (name "CREATED_BY") "PCBLayout.com")
      )
      (libsource (lib "eagle-import") (part "BSS84LT1G"))
    )
    (comp (ref "Q216")
      (value "BSS84LT1G")
      (footprint "eagle-import:SOT23-3")
      (fields
        (field (name "DIGIKEY_PART_NUMBER") "BSS84LT1GOSCT-ND")
        (field (name "MANUFACTURER") "ON Semiconductor")
        (field (name "CREATED_BY") "PCBLayout.com")
      )
      (libsource (lib "eagle-import") (part "BSS84LT1G"))
    )
    (comp (ref "Q217")
      (value "2N7002,215")
      (footprint "eagle-import:SOT23-3")
      (fields
        (field (name "DIGIKEY_PART_NUMBER") "1727-2764-1-ND")
        (field (name "MANUFACTURER") "Nexperia USA Inc.")
        (field (name "CREATED_BY") "PCBLayout.com")
      )
      (libsource (lib "eagle-import") (part "2N7002,215"))
    )
    (comp (ref "Q218")
      (value "2N7002,215")
      (footprint "eagle-import:SOT23-3")
      (fields
        (field (name "DIGIKEY_PART_NUMBER") "1727-2764-1-ND")
        (field (name "MANUFACTURER") "Nexperia USA Inc.")
        (field (name "CREATED_BY") "PCBLayout.com")
      )
      (libsource (lib "eagle-import") (part "2N7002,215"))
    )
    (comp (ref "Q219")
      (value "BSS84LT1G")
      (footprint "eagle-import:SOT23-3")
      (fields
        (field (name "DIGIKEY_PART_NUMBER") "BSS84LT1GOSCT-ND")
        (field (name "MANUFACTURER") "ON Semiconductor")
        (field (name "CREATED_BY") "PCBLayout.com")
      )
      (libsource (lib "eagle-import") (part "BSS84LT1G"))
    )
    (comp (ref "Q220")
      (value "BSS84LT1G")
      (footprint "eagle-import:SOT23-3")
      (fields
        (field (name "DIGIKEY_PART_NUMBER") "BSS84LT1GOSCT-ND")
        (field (name "MANUFACTURER") "ON Semiconductor")
        (field (name "CREATED_BY") "PCBLayout.com")
      )
      (libsource (lib "eagle-import") (part "BSS84LT1G"))
    )
    (comp (ref "Q221")
      (value "2N7002,215")
      (footprint "eagle-import:SOT23-3")
      (fields
        (field (name "DIGIKEY_PART_NUMBER") "1727-2764-1-ND")
        (field (name "MANUFACTURER") "Nexperia USA Inc.")
        (field (name "CREATED_BY") "PCBLayout.com")
      )
      (libsource (lib "eagle-import") (part "2N7002,215"))
    )
    (comp (ref "Q222")
      (value "2N7002,215")
      (footprint "eagle-import:SOT23-3")
      (fields
        (field (name "DIGIKEY_PART_NUMBER") "1727-2764-1-ND")
        (field (name "MANUFACTURER") "Nexperia USA Inc.")
        (field (name "CREATED_BY") "PCBLayout.com")
      )
      (libsource (lib "eagle-import") (part "2N7002,215"))
    )
    (comp (ref "Q223")
      (value "BSS84LT1G")
      (footprint "eagle-import:SOT23-3")
      (fields
        (field (name "DIGIKEY_PART_NUMBER") "BSS84LT1GOSCT-ND")
        (field (name "MANUFACTURER") "ON Semiconductor")
        (field (name "CREATED_BY") "PCBLayout.com")
      )
      (libsource (lib "eagle-import") (part "BSS84LT1G"))
    )
    (comp (ref "Q224")
      (value "BSS84LT1G")
      (footprint "eagle-import:SOT23-3")
      (fields
        (field (name "DIGIKEY_PART_NUMBER") "BSS84LT1GOSCT-ND")
        (field (name "MANUFACTURER") "ON Semiconductor")
        (field (name "CREATED_BY") "PCBLayout.com")
      )
      (libsource (lib "eagle-import") (part "BSS84LT1G"))
    )
    (comp (ref "Q225")
      (value "2N7002,215")
      (footprint "eagle-import:SOT23-3")
      (fields
        (field (name "DIGIKEY_PART_NUMBER") "1727-2764-1-ND")
        (field (name "MANUFACTURER") "Nexperia USA Inc.")
        (field (name "CREATED_BY") "PCBLayout.com")
      )
      (libsource (lib "eagle-import") (part "2N7002,215"))
    )
    (comp (ref "Q226")
      (value "BSS84LT1G")
      (footprint "eagle-import:SOT23-3")
      (fields
        (field (name "DIGIKEY_PART_NUMBER") "BSS84LT1GOSCT-ND")
        (field (name "MANUFACTURER") "ON Semiconductor")
        (field (name "CREATED_BY") "PCBLayout.com")
      )
      (libsource (lib "eagle-import") (part "BSS84LT1G"))
    )
    (comp (ref "Q227")
      (value "2N7002,215")
      (footprint "eagle-import:SOT23-3")
      (fields
        (field (name "DIGIKEY_PART_NUMBER") "1727-2764-1-ND")
        (field (name "MANUFACTURER") "Nexperia USA Inc.")
        (field (name "CREATED_BY") "PCBLayout.com")
      )
      (libsource (lib "eagle-import") (part "2N7002,215"))
    )
    (comp (ref "Q228")
      (value "BSS84LT1G")
      (footprint "eagle-import:SOT23-3")
      (fields
        (field (name "DIGIKEY_PART_NUMBER") "BSS84LT1GOSCT-ND")
        (field (name "MANUFACTURER") "ON Semiconductor")
        (field (name "CREATED_BY") "PCBLayout.com")
      )
      (libsource (lib "eagle-import") (part "BSS84LT1G"))
    )
    (comp (ref "Q229")
      (value "2N7002,215")
      (footprint "eagle-import:SOT23-3")
      (fields
        (field (name "DIGIKEY_PART_NUMBER") "1727-2764-1-ND")
        (field (name "MANUFACTURER") "Nexperia USA Inc.")
        (field (name "CREATED_BY") "PCBLayout.com")
      )
      (libsource (lib "eagle-import") (part "2N7002,215"))
    )
    (comp (ref "Q230")
      (value "BSS84LT1G")
      (footprint "eagle-import:SOT23-3")
      (fields
        (field (name "DIGIKEY_PART_NUMBER") "BSS84LT1GOSCT-ND")
        (field (name "MANUFACTURER") "ON Semiconductor")
        (field (name "CREATED_BY") "PCBLayout.com")
      )
      (libsource (lib "eagle-import") (part "BSS84LT1G"))
    )
    (comp (ref "Q231")
      (value "2N7002,215")
      (footprint "eagle-import:SOT23-3")
      (fields
        (field (name "DIGIKEY_PART_NUMBER") "1727-2764-1-ND")
        (field (name "MANUFACTURER") "Nexperia USA Inc.")
        (field (name "CREATED_BY") "PCBLayout.com")
      )
      (libsource (lib "eagle-import") (part "2N7002,215"))
    )
    (comp (ref "Q232")
      (value "BSS84LT1G")
      (footprint "eagle-import:SOT23-3")
      (fields
        (field (name "DIGIKEY_PART_NUMBER") "BSS84LT1GOSCT-ND")
        (field (name "MANUFACTURER") "ON Semiconductor")
        (field (name "CREATED_BY") "PCBLayout.com")
      )
      (libsource (lib "eagle-import") (part "BSS84LT1G"))
    )
    (comp (ref "Q233")
      (value "2N7002,215")
      (footprint "eagle-import:SOT23-3")
      (fields
        (field (name "DIGIKEY_PART_NUMBER") "1727-2764-1-ND")
        (field (name "MANUFACTURER") "Nexperia USA Inc.")
        (field (name "CREATED_BY") "PCBLayout.com")
      )
      (libsource (lib "eagle-import") (part "2N7002,215"))
    )
    (comp (ref "Q234")
      (value "BSS84LT1G")
      (footprint "eagle-import:SOT23-3")
      (fields
        (field (name "DIGIKEY_PART_NUMBER") "BSS84LT1GOSCT-ND")
        (field (name "MANUFACTURER") "ON Semiconductor")
        (field (name "CREATED_BY") "PCBLayout.com")
      )
      (libsource (lib "eagle-import") (part "BSS84LT1G"))
    )
    (comp (ref "Q235")
      (value "2N7002,215")
      (footprint "eagle-import:SOT23-3")
      (fields
        (field (name "DIGIKEY_PART_NUMBER") "1727-2764-1-ND")
        (field (name "MANUFACTURER") "Nexperia USA Inc.")
        (field (name "CREATED_BY") "PCBLayout.com")
      )
      (libsource (lib "eagle-import") (part "2N7002,215"))
    )
    (comp (ref "Q236")
      (value "BSS84LT1G")
      (footprint "eagle-import:SOT23-3")
      (fields
        (field (name "DIGIKEY_PART_NUMBER") "BSS84LT1GOSCT-ND")
        (field (name "MANUFACTURER") "ON Semiconductor")
        (field (name "CREATED_BY") "PCBLayout.com")
      )
      (libsource (lib "eagle-import") (part "BSS84LT1G"))
    )
    (comp (ref "Q237")
      (value "2N7002,215")
      (footprint "eagle-import:SOT23-3")
      (fields
        (field (name "DIGIKEY_PART_NUMBER") "1727-2764-1-ND")
        (field (name "MANUFACTURER") "Nexperia USA Inc.")
        (field (name "CREATED_BY") "PCBLayout.com")
      )
      (libsource (lib "eagle-import") (part "2N7002,215"))
    )
    (comp (ref "Q238")
      (value "BSS84LT1G")
      (footprint "eagle-import:SOT23-3")
      (fields
        (field (name "DIGIKEY_PART_NUMBER") "BSS84LT1GOSCT-ND")
        (field (name "MANUFACTURER") "ON Semiconductor")
        (field (name "CREATED_BY") "PCBLayout.com")
      )
      (libsource (lib "eagle-import") (part "BSS84LT1G"))
    )
    (comp (ref "Q239")
      (value "2N7002,215")
      (footprint "eagle-import:SOT23-3")
      (fields
        (field (name "DIGIKEY_PART_NUMBER") "1727-2764-1-ND")
        (field (name "MANUFACTURER") "Nexperia USA Inc.")
        (field (name "CREATED_BY") "PCBLayout.com")
      )
      (libsource (lib "eagle-import") (part "2N7002,215"))
    )
    (comp (ref "Q240")
      (value "BSS84LT1G")
      (footprint "eagle-import:SOT23-3")
      (fields
        (field (name "DIGIKEY_PART_NUMBER") "BSS84LT1GOSCT-ND")
        (field (name "MANUFACTURER") "ON Semiconductor")
        (field (name "CREATED_BY") "PCBLayout.com")
      )
      (libsource (lib "eagle-import") (part "BSS84LT1G"))
    )
    (comp (ref "Q241")
      (value "2N7002,215")
      (footprint "eagle-import:SOT23-3")
      (fields
        (field (name "DIGIKEY_PART_NUMBER") "1727-2764-1-ND")
        (field (name "MANUFACTURER") "Nexperia USA Inc.")
        (field (name "CREATED_BY") "PCBLayout.com")
      )
      (libsource (lib "eagle-import") (part "2N7002,215"))
    )
    (comp (ref "Q242")
      (value "BSS84LT1G")
      (footprint "eagle-import:SOT23-3")
      (fields
        (field (name "DIGIKEY_PART_NUMBER") "BSS84LT1GOSCT-ND")
        (field (name "MANUFACTURER") "ON Semiconductor")
        (field (name "CREATED_BY") "PCBLayout.com")
      )
      (libsource (lib "eagle-import") (part "BSS84LT1G"))
    )
    (comp (ref "Q243")
      (value "2N7002,215")
      (footprint "eagle-import:SOT23-3")
      (fields
        (field (name "DIGIKEY_PART_NUMBER") "1727-2764-1-ND")
        (field (name "MANUFACTURER") "Nexperia USA Inc.")
        (field (name "CREATED_BY") "PCBLayout.com")
      )
      (libsource (lib "eagle-import") (part "2N7002,215"))
    )
    (comp (ref "Q244")
      (value "BSS84LT1G")
      (footprint "eagle-import:SOT23-3")
      (fields
        (field (name "DIGIKEY_PART_NUMBER") "BSS84LT1GOSCT-ND")
        (field (name "MANUFACTURER") "ON Semiconductor")
        (field (name "CREATED_BY") "PCBLayout.com")
      )
      (libsource (lib "eagle-import") (part "BSS84LT1G"))
    )
    (comp (ref "Q245")
      (value "2N7002,215")
      (footprint "eagle-import:SOT23-3")
      (fields
        (field (name "DIGIKEY_PART_NUMBER") "1727-2764-1-ND")
        (field (name "MANUFACTURER") "Nexperia USA Inc.")
        (field (name "CREATED_BY") "PCBLayout.com")
      )
      (libsource (lib "eagle-import") (part "2N7002,215"))
    )
    (comp (ref "Q246")
      (value "BSS84LT1G")
      (footprint "eagle-import:SOT23-3")
      (fields
        (field (name "DIGIKEY_PART_NUMBER") "BSS84LT1GOSCT-ND")
        (field (name "MANUFACTURER") "ON Semiconductor")
        (field (name "CREATED_BY") "PCBLayout.com")
      )
      (libsource (lib "eagle-import") (part "BSS84LT1G"))
    )
    (comp (ref "Q247")
      (value "2N7002,215")
      (footprint "eagle-import:SOT23-3")
      (fields
        (field (name "DIGIKEY_PART_NUMBER") "1727-2764-1-ND")
        (field (name "MANUFACTURER") "Nexperia USA Inc.")
        (field (name "CREATED_BY") "PCBLayout.com")
      )
      (libsource (lib "eagle-import") (part "2N7002,215"))
    )
    (comp (ref "Q248")
      (value "BSS84LT1G")
      (footprint "eagle-import:SOT23-3")
      (fields
        (field (name "DIGIKEY_PART_NUMBER") "BSS84LT1GOSCT-ND")
        (field (name "MANUFACTURER") "ON Semiconductor")
        (field (name "CREATED_BY") "PCBLayout.com")
      )
      (libsource (lib "eagle-import") (part "BSS84LT1G"))
    )
    (comp (ref "Q249")
      (value "2N7002,215")
      (footprint "eagle-import:SOT23-3")
      (fields
        (field (name "DIGIKEY_PART_NUMBER") "1727-2764-1-ND")
        (field (name "MANUFACTURER") "Nexperia USA Inc.")
        (field (name "CREATED_BY") "PCBLayout.com")
      )
      (libsource (lib "eagle-import") (part "2N7002,215"))
    )
    (comp (ref "Q250")
      (value "BSS84LT1G")
      (footprint "eagle-import:SOT23-3")
      (fields
        (field (name "DIGIKEY_PART_NUMBER") "BSS84LT1GOSCT-ND")
        (field (name "MANUFACTURER") "ON Semiconductor")
        (field (name "CREATED_BY") "PCBLayout.com")
      )
      (libsource (lib "eagle-import") (part "BSS84LT1G"))
    )
    (comp (ref "Q251")
      (value "2N7002,215")
      (footprint "eagle-import:SOT23-3")
      (fields
        (field (name "DIGIKEY_PART_NUMBER") "1727-2764-1-ND")
        (field (name "MANUFACTURER") "Nexperia USA Inc.")
        (field (name "CREATED_BY") "PCBLayout.com")
      )
      (libsource (lib "eagle-import") (part "2N7002,215"))
    )
    (comp (ref "Q252")
      (value "BSS84LT1G")
      (footprint "eagle-import:SOT23-3")
      (fields
        (field (name "DIGIKEY_PART_NUMBER") "BSS84LT1GOSCT-ND")
        (field (name "MANUFACTURER") "ON Semiconductor")
        (field (name "CREATED_BY") "PCBLayout.com")
      )
      (libsource (lib "eagle-import") (part "BSS84LT1G"))
    )
    (comp (ref "Q253")
      (value "2N7002,215")
      (footprint "eagle-import:SOT23-3")
      (fields
        (field (name "DIGIKEY_PART_NUMBER") "1727-2764-1-ND")
        (field (name "MANUFACTURER") "Nexperia USA Inc.")
        (field (name "CREATED_BY") "PCBLayout.com")
      )
      (libsource (lib "eagle-import") (part "2N7002,215"))
    )
    (comp (ref "Q254")
      (value "BSS84LT1G")
      (footprint "eagle-import:SOT23-3")
      (fields
        (field (name "DIGIKEY_PART_NUMBER") "BSS84LT1GOSCT-ND")
        (field (name "MANUFACTURER") "ON Semiconductor")
        (field (name "CREATED_BY") "PCBLayout.com")
      )
      (libsource (lib "eagle-import") (part "BSS84LT1G"))
    )
    (comp (ref "Q255")
      (value "2N7002,215")
      (footprint "eagle-import:SOT23-3")
      (fields
        (field (name "DIGIKEY_PART_NUMBER") "1727-2764-1-ND")
        (field (name "MANUFACTURER") "Nexperia USA Inc.")
        (field (name "CREATED_BY") "PCBLayout.com")
      )
      (libsource (lib "eagle-import") (part "2N7002,215"))
    )
    (comp (ref "Q256")
      (value "BSS84LT1G")
      (footprint "eagle-import:SOT23-3")
      (fields
        (field (name "DIGIKEY_PART_NUMBER") "BSS84LT1GOSCT-ND")
        (field (name "MANUFACTURER") "ON Semiconductor")
        (field (name "CREATED_BY") "PCBLayout.com")
      )
      (libsource (lib "eagle-import") (part "BSS84LT1G"))
    )
    (comp (ref "Q257")
      (value "2N7002,215")
      (footprint "eagle-import:SOT23-3")
      (fields
        (field (name "DIGIKEY_PART_NUMBER") "1727-2764-1-ND")
        (field (name "MANUFACTURER") "Nexperia USA Inc.")
        (field (name "CREATED_BY") "PCBLayout.com")
      )
      (libsource (lib "eagle-import") (part "2N7002,215"))
    )
    (comp (ref "Q258")
      (value "BSS84LT1G")
      (footprint "eagle-import:SOT23-3")
      (fields
        (field (name "DIGIKEY_PART_NUMBER") "BSS84LT1GOSCT-ND")
        (field (name "MANUFACTURER") "ON Semiconductor")
        (field (name "CREATED_BY") "PCBLayout.com")
      )
      (libsource (lib "eagle-import") (part "BSS84LT1G"))
    )
    (comp (ref "Q259")
      (value "2N7002,215")
      (footprint "eagle-import:SOT23-3")
      (fields
        (field (name "DIGIKEY_PART_NUMBER") "1727-2764-1-ND")
        (field (name "MANUFACTURER") "Nexperia USA Inc.")
        (field (name "CREATED_BY") "PCBLayout.com")
      )
      (libsource (lib "eagle-import") (part "2N7002,215"))
    )
    (comp (ref "Q260")
      (value "BSS84LT1G")
      (footprint "eagle-import:SOT23-3")
      (fields
        (field (name "DIGIKEY_PART_NUMBER") "BSS84LT1GOSCT-ND")
        (field (name "MANUFACTURER") "ON Semiconductor")
        (field (name "CREATED_BY") "PCBLayout.com")
      )
      (libsource (lib "eagle-import") (part "BSS84LT1G"))
    )
    (comp (ref "R1")
      (value "RC-MASTER-SMD_R_0603MP")
      (footprint "eagle-import:RC-MASTER-SMD_R0603MP")
      (libsource (lib "eagle-import") (part "RC-MASTER-SMD_R_0603MP"))
    )
    (comp (ref "R2")
      (value "RC-MASTER-SMD_R_0603MP")
      (footprint "eagle-import:RC-MASTER-SMD_R0603MP")
      (libsource (lib "eagle-import") (part "RC-MASTER-SMD_R_0603MP"))
    )
    (comp (ref "R3")
      (value "RC-MASTER-SMD_R_0603MP")
      (footprint "eagle-import:RC-MASTER-SMD_R0603MP")
      (libsource (lib "eagle-import") (part "RC-MASTER-SMD_R_0603MP"))
    )
    (comp (ref "R4")
      (value "RC-MASTER-SMD_R_0603MP")
      (footprint "eagle-import:RC-MASTER-SMD_R0603MP")
      (libsource (lib "eagle-import") (part "RC-MASTER-SMD_R_0603MP"))
    )
    (comp (ref "R5")
      (value "RC-MASTER-SMD_R_0603MP")
      (footprint "eagle-import:RC-MASTER-SMD_R0603MP")
      (libsource (lib "eagle-import") (part "RC-MASTER-SMD_R_0603MP"))
    )
    (comp (ref "R6")
      (value "RC-MASTER-SMD_R_0603MP")
      (footprint "eagle-import:RC-MASTER-SMD_R0603MP")
      (libsource (lib "eagle-import") (part "RC-MASTER-SMD_R_0603MP"))
    )
  )
  (nets
    (net (code "1") (name "Net-(Q1-D)") (class "Default")
      (node (ref "Q1") (pin "3") (pinfunction "D_3") (pintype "passive"))
      (node (ref "Q12") (pin "1") (pinfunction "G_1") (pintype "passive"))
      (node (ref "Q3") (pin "3") (pinfunction "D_3") (pintype "passive"))
      (node (ref "Q4") (pin "3") (pinfunction "D_3") (pintype "passive"))
      (node (ref "Q9") (pin "1") (pinfunction "G_1") (pintype "passive"))
    )
    (net (code "2") (name "Net-(Q1-G)") (class "Default")
      (node (ref "Q1") (pin "1") (pinfunction "G_1") (pintype "passive"))
      (node (ref "Q227") (pin "3") (pinfunction "D_3") (pintype "passive"))
      (node (ref "Q228") (pin "3") (pinfunction "D_3") (pintype "passive"))
      (node (ref "Q4") (pin "1") (pinfunction "G_1") (pintype "passive"))
    )
    (net (code "3") (name "Net-(Q1-S)") (class "Default")
      (node (ref "Q1") (pin "2") (pinfunction "S_2") (pintype "passive"))
      (node (ref "Q2") (pin "3") (pinfunction "D_3") (pintype "passive"))
    )
    (net (code "4") (name "Net-(Q2-G)") (class "Default")
      (node (ref "Q2") (pin "1") (pinfunction "G_1") (pintype "passive"))
      (node (ref "Q225") (pin "3") (pinfunction "D_3") (pintype "passive"))
      (node (ref "Q226") (pin "3") (pinfunction "D_3") (pintype "passive"))
      (node (ref "Q3") (pin "1") (pinfunction "G_1") (pintype "passive"))
    )
    (net (code "5") (name "Net-(Q5-S)") (class "Default")
      (node (ref "Q5") (pin "2") (pinfunction "S_2") (pintype "passive"))
      (node (ref "Q6") (pin "3") (pinfunction "D_3") (pintype "passive"))
    )
    (net (code "6") (name "Net-(Q10-D)") (class "Default")
      (node (ref "Q10") (pin "3") (pinfunction "D_3") (pintype "passive"))
      (node (ref "Q9") (pin "2") (pinfunction "S_2") (pintype "passive"))
    )
    (net (code "7") (name "Net-(Q10-G)") (class "Default")
      (node (ref "Q10") (pin "1") (pinfunction "G_1") (pintype "passive"))
      (node (ref "Q11") (pin "1") (pinfunction "G_1") (pintype "passive"))
      (node (ref "Q33") (pin "3") (pinfunction "D_3") (pintype "passive"))
      (node (ref "Q35") (pin "3") (pinfunction "D_3") (pintype "passive"))
      (node (ref "Q36") (pin "3") (pinfunction "D_3") (pintype "passive"))
    )
    (net (code "8") (name "Net-(Q10-S)") (class "Default")
      (node (ref "IC1") (pin "8") (pinfunction "8_8") (pintype "passive"))
      (node (ref "IC2") (pin "7") (pinfunction "7_7") (pintype "passive"))
      (node (ref "IC2") (pin "8") (pinfunction "8_8") (pintype "passive"))
      (node (ref "IC3") (pin "8") (pinfunction "8_8") (pintype "passive"))
      (node (ref "IC4") (pin "8") (pinfunction "8_8") (pintype "passive"))
      (node (ref "IC5") (pin "14") (pinfunction "14_14") (pintype "passive"))
      (node (ref "IC6") (pin "8") (pinfunction "8_8") (pintype "passive"))
      (node (ref "Q10") (pin "2") (pinfunction "S_2") (pintype "passive"))
      (node (ref "Q102") (pin "2") (pinfunction "S_2") (pintype "passive"))
      (node (ref "Q106") (pin "2") (pinfunction "S_2") (pintype "passive"))
      (node (ref "Q110") (pin "2") (pinfunction "S_2") (pintype "passive"))
      (node (ref "Q114") (pin "2") (pinfunction "S_2") (pintype "passive"))
      (node (ref "Q118") (pin "2") (pinfunction "S_2") (pintype "passive"))
      (node (ref "Q122") (pin "2") (pinfunction "S_2") (pintype "passive"))
      (node (ref "Q126") (pin "2") (pinfunction "S_2") (pintype "passive"))
      (node (ref "Q130") (pin "2") (pinfunction "S_2") (pintype "passive"))
      (node (ref "Q134") (pin "2") (pinfunction "S_2") (pintype "passive"))
      (node (ref "Q138") (pin "2") (pinfunction "S_2") (pintype "passive"))
      (node (ref "Q14") (pin "2") (pinfunction "S_2") (pintype "passive"))
      (node (ref "Q142") (pin "2") (pinfunction "S_2") (pintype "passive"))
      (node (ref "Q146") (pin "2") (pinfunction "S_2") (pintype "passive"))
      (node (ref "Q150") (pin "2") (pinfunction "S_2") (pintype "passive"))
      (node (ref "Q154") (pin "2") (pinfunction "S_2") (pintype "passive"))
      (node (ref "Q158") (pin "2") (pinfunction "S_2") (pintype "passive"))
      (node (ref "Q162") (pin "2") (pinfunction "S_2") (pintype "passive"))
      (node (ref "Q166") (pin "2") (pinfunction "S_2") (pintype "passive"))
      (node (ref "Q170") (pin "2") (pinfunction "S_2") (pintype "passive"))
      (node (ref "Q174") (pin "2") (pinfunction "S_2") (pintype "passive"))
      (node (ref "Q178") (pin "2") (pinfunction "S_2") (pintype "passive"))
      (node (ref "Q18") (pin "2") (pinfunction "S_2") (pintype "passive"))
      (node (ref "Q182") (pin "2") (pinfunction "S_2") (pintype "passive"))
      (node (ref "Q186") (pin "2") (pinfunction "S_2") (pintype "passive"))
      (node (ref "Q190") (pin "2") (pinfunction "S_2") (pintype "passive"))
      (node (ref "Q194") (pin "2") (pinfunction "S_2") (pintype "passive"))
      (node (ref "Q198") (pin "2") (pinfunction "S_2") (pintype "passive"))
      (node (ref "Q2") (pin "2") (pinfunction "S_2") (pintype "passive"))
      (node (ref "Q202") (pin "2") (pinfunction "S_2") (pintype "passive"))
      (node (ref "Q206") (pin "2") (pinfunction "S_2") (pintype "passive"))
      (node (ref "Q210") (pin "2") (pinfunction "S_2") (pintype "passive"))
      (node (ref "Q214") (pin "2") (pinfunction "S_2") (pintype "passive"))
      (node (ref "Q218") (pin "2") (pinfunction "S_2") (pintype "passive"))
      (node (ref "Q22") (pin "2") (pinfunction "S_2") (pintype "passive"))
      (node (ref "Q222") (pin "2") (pinfunction "S_2") (pintype "passive"))
      (node (ref "Q225") (pin "2") (pinfunction "S_2") (pintype "passive"))
      (node (ref "Q227") (pin "2") (pinfunction "S_2") (pintype "passive"))
      (node (ref "Q229") (pin "2") (pinfunction "S_2") (pintype "passive"))
      (node (ref "Q231") (pin "2") (pinfunction "S_2") (pintype "passive"))
      (node (ref "Q233") (pin "2") (pinfunction "S_2") (pintype "passive"))
      (node (ref "Q235") (pin "2") (pinfunction "S_2") (pintype "passive"))
      (node (ref "Q237") (pin "2") (pinfunction "S_2") (pintype "passive"))
      (node (ref "Q239") (pin "2") (pinfunction "S_2") (pintype "passive"))
      (node (ref "Q241") (pin "2") (pinfunction "S_2") (pintype "passive"))
      (node (ref "Q243") (pin "2") (pinfunction "S_2") (pintype "passive"))
      (node (ref "Q245") (pin "2") (pinfunction "S_2") (pintype "passive"))
      (node (ref "Q247") (pin "2") (pinfunction "S_2") (pintype "passive"))
      (node (ref "Q249") (pin "2") (pinfunction "S_2") (pintype "passive"))
      (node (ref "Q251") (pin "2") (pinfunction "S_2") (pintype "passive"))
      (node (ref "Q253") (pin "2") (pinfunction "S_2") (pintype "passive"))
      (node (ref "Q255") (pin "1") (pinfunction "G_1") (pintype "passive"))
      (node (ref "Q255") (pin "2") (pinfunction "S_2") (pintype "passive"))
      (node (ref "Q256") (pin "1") (pinfunction "G_1") (pintype "passive"))
      (node (ref "Q257") (pin "2") (pinfunction "S_2") (pintype "passive"))
      (node (ref "Q259") (pin "2") (pinfunction "S_2") (pintype "passive"))
      (node (ref "Q26") (pin "2") (pinfunction "S_2") (pintype "passive"))
      (node (ref "Q30") (pin "2") (pinfunction "S_2") (pintype "passive"))
      (node (ref "Q34") (pin "2") (pinfunction "S_2") (pintype "passive"))
      (node (ref "Q38") (pin "2") (pinfunction "S_2") (pintype "passive"))
      (node (ref "Q42") (pin "2") (pinfunction "S_2") (pintype "passive"))
      (node (ref "Q46") (pin "2") (pinfunction "S_2") (pintype "passive"))
      (node (ref "Q50") (pin "2") (pinfunction "S_2") (pintype "passive"))
      (node (ref "Q54") (pin "2") (pinfunction "S_2") (pintype "passive"))
      (node (ref "Q58") (pin "2") (pinfunction "S_2") (pintype "passive"))
      (node (ref "Q6") (pin "2") (pinfunction "S_2") (pintype "passive"))
      (node (ref "Q62") (pin "2") (pinfunction "S_2") (pintype "passive"))
      (node (ref "Q66") (pin "2") (pinfunction "S_2") (pintype "passive"))
      (node (ref "Q70") (pin "2") (pinfunction "S_2") (pintype "passive"))
      (node (ref "Q74") (pin "2") (pinfunction "S_2") (pintype "passive"))
      (node (ref "Q78") (pin "2") (pinfunction "S_2") (pintype "passive"))
      (node (ref "Q82") (pin "2") (pinfunction "S_2") (pintype "passive"))
      (node (ref "Q86") (pin "2") (pinfunction "S_2") (pintype "passive"))
      (node (ref "Q90") (pin "2") (pinfunction "S_2") (pintype "passive"))
      (node (ref "Q94") (pin "2") (pinfunction "S_2") (pintype "passive"))
      (node (ref "Q98") (pin "2") (pinfunction "S_2") (pintype "passive"))
    )
    (net (code "9") (name "Net-(Q11-D)") (class "Default")
      (node (ref "Q11") (pin "3") (pinfunction "D_3") (pintype "passive"))
      (node (ref "Q12") (pin "3") (pinfunction "D_3") (pintype "passive"))
      (node (ref "Q13") (pin "1") (pinfunction "G_1") (pintype "passive"))
      (node (ref "Q16") (pin "1") (pinfunction "G_1") (pintype "passive"))
      (node (ref "Q9") (pin "3") (pinfunction "D_3") (pintype "passive"))
    )
    (net (code "10") (name "Net-(Q13-D)") (class "Default")
      (node (ref "IC3") (pin "1") (pinfunction "1_1") (pintype "passive"))
      (node (ref "IC4") (pin "10") (pinfunction "10_10") (pintype "passive"))
      (node (ref "Q13") (pin "3") (pinfunction "D_3") (pintype "passive"))
      (node (ref "Q15") (pin "3") (pinfunction "D_3") (pintype "passive"))
      (node (ref "Q16") (pin "3") (pinfunction "D_3") (pintype "passive"))
    )
    (net (code "11") (name "Net-(Q13-S)") (class "Default")
      (node (ref "Q13") (pin "2") (pinfunction "S_2") (pintype "passive"))
      (node (ref "Q14") (pin "3") (pinfunction "D_3") (pintype "passive"))
    )
    (net (code "12") (name "Net-(Q14-G)") (class "Default")
      (node (ref "Q14") (pin "1") (pinfunction "G_1") (pintype "passive"))
      (node (ref "Q15") (pin "1") (pinfunction "G_1") (pintype "passive"))
      (node (ref "Q5") (pin "3") (pinfunction "D_3") (pintype "passive"))
      (node (ref "Q7") (pin "3") (pinfunction "D_3") (pintype "passive"))
      (node (ref "Q8") (pin "3") (pinfunction "D_3") (pintype "passive"))
    )
    (net (code "13") (name "Net-(Q17-D)") (class "Default")
      (node (ref "Q17") (pin "3") (pinfunction "D_3") (pintype "passive"))
      (node (ref "Q19") (pin "3") (pinfunction "D_3") (pintype "passive"))
      (node (ref "Q20") (pin "3") (pinfunction "D_3") (pintype "passive"))
    )
    (net (code "14") (name "Net-(Q17-G)") (class "Default")
      (node (ref "Q17") (pin "1") (pinfunction "G_1") (pintype "passive"))
      (node (ref "Q20") (pin "1") (pinfunction "G_1") (pintype "passive"))
    )
    (net (code "15") (name "Net-(Q17-S)") (class "Default")
      (node (ref "Q17") (pin "2") (pinfunction "S_2") (pintype "passive"))
      (node (ref "Q18") (pin "3") (pinfunction "D_3") (pintype "passive"))
    )
    (net (code "16") (name "Net-(Q18-G)") (class "Default")
      (node (ref "Q18") (pin "1") (pinfunction "G_1") (pintype "passive"))
      (node (ref "Q19") (pin "1") (pinfunction "G_1") (pintype "passive"))
    )
    (net (code "17") (name "Net-(Q21-D)") (class "Default")
      (node (ref "Q21") (pin "3") (pinfunction "D_3") (pintype "passive"))
      (node (ref "Q23") (pin "3") (pinfunction "D_3") (pintype "passive"))
      (node (ref "Q24") (pin "3") (pinfunction "D_3") (pintype "passive"))
    )
    (net (code "18") (name "Net-(Q21-G)") (class "Default")
      (node (ref "Q21") (pin "1") (pinfunction "G_1") (pintype "passive"))
      (node (ref "Q24") (pin "1") (pinfunction "G_1") (pintype "passive"))
    )
    (net (code "19") (name "Net-(Q21-S)") (class "Default")
      (node (ref "Q21") (pin "2") (pinfunction "S_2") (pintype "passive"))
      (node (ref "Q22") (pin "3") (pinfunction "D_3") (pintype "passive"))
    )
    (net (code "20") (name "Net-(Q22-G)") (class "Default")
      (node (ref "Q22") (pin "1") (pinfunction "G_1") (pintype "passive"))
      (node (ref "Q23") (pin "1") (pinfunction "G_1") (pintype "passive"))
    )
    (net (code "21") (name "Net-(Q25-D)") (class "Default")
      (node (ref "Q25") (pin "3") (pinfunction "D_3") (pintype "passive"))
      (node (ref "Q27") (pin "3") (pinfunction "D_3") (pintype "passive"))
      (node (ref "Q28") (pin "3") (pinfunction "D_3") (pintype "passive"))
    )
    (net (code "22") (name "Net-(Q25-G)") (class "Default")
      (node (ref "Q25") (pin "1") (pinfunction "G_1") (pintype "passive"))
      (node (ref "Q28") (pin "1") (pinfunction "G_1") (pintype "passive"))
    )
    (net (code "23") (name "Net-(Q25-S)") (class "Default")
      (node (ref "Q25") (pin "2") (pinfunction "S_2") (pintype "passive"))
      (node (ref "Q26") (pin "3") (pinfunction "D_3") (pintype "passive"))
    )
    (net (code "24") (name "Net-(Q26-G)") (class "Default")
      (node (ref "Q26") (pin "1") (pinfunction "G_1") (pintype "passive"))
      (node (ref "Q27") (pin "1") (pinfunction "G_1") (pintype "passive"))
    )
    (net (code "25") (name "Net-(Q29-D)") (class "Default")
      (node (ref "Q29") (pin "3") (pinfunction "D_3") (pintype "passive"))
      (node (ref "Q31") (pin "3") (pinfunction "D_3") (pintype "passive"))
      (node (ref "Q32") (pin "3") (pinfunction "D_3") (pintype "passive"))
    )
    (net (code "26") (name "Net-(Q29-G)") (class "Default")
      (node (ref "Q29") (pin "1") (pinfunction "G_1") (pintype "passive"))
      (node (ref "Q32") (pin "1") (pinfunction "G_1") (pintype "passive"))
    )
    (net (code "27") (name "Net-(Q29-S)") (class "Default")
      (node (ref "Q29") (pin "2") (pinfunction "S_2") (pintype "passive"))
      (node (ref "Q30") (pin "3") (pinfunction "D_3") (pintype "passive"))
    )
    (net (code "28") (name "Net-(Q30-G)") (class "Default")
      (node (ref "Q30") (pin "1") (pinfunction "G_1") (pintype "passive"))
      (node (ref "Q31") (pin "1") (pinfunction "G_1") (pintype "passive"))
    )
    (net (code "29") (name "Net-(Q33-S)") (class "Default")
      (node (ref "Q33") (pin "2") (pinfunction "S_2") (pintype "passive"))
      (node (ref "Q34") (pin "3") (pinfunction "D_3") (pintype "passive"))
    )
    (net (code "30") (name "Net-(Q37-D)") (class "Default")
      (node (ref "Q37") (pin "3") (pinfunction "D_3") (pintype "passive"))
      (node (ref "Q39") (pin "3") (pinfunction "D_3") (pintype "passive"))
      (node (ref "Q40") (pin "3") (pinfunction "D_3") (pintype "passive"))
      (node (ref "Q5") (pin "1") (pinfunction "G_1") (pintype "passive"))
      (node (ref "Q8") (pin "1") (pinfunction "G_1") (pintype "passive"))
    )
    (net (code "31") (name "Net-(Q37-S)") (class "Default")
      (node (ref "Q37") (pin "2") (pinfunction "S_2") (pintype "passive"))
      (node (ref "Q38") (pin "3") (pinfunction "D_3") (pintype "passive"))
    )
    (net (code "32") (name "Net-(Q41-D)") (class "Default")
      (node (ref "Q41") (pin "3") (pinfunction "D_3") (pintype "passive"))
      (node (ref "Q43") (pin "3") (pinfunction "D_3") (pintype "passive"))
      (node (ref "Q44") (pin "3") (pinfunction "D_3") (pintype "passive"))
      (node (ref "Q6") (pin "1") (pinfunction "G_1") (pintype "passive"))
      (node (ref "Q7") (pin "1") (pinfunction "G_1") (pintype "passive"))
    )
    (net (code "33") (name "Net-(Q41-G)") (class "Default")
      (node (ref "IC3") (pin "14") (pinfunction "14_14") (pintype "passive"))
      (node (ref "Q41") (pin "1") (pinfunction "G_1") (pintype "passive"))
      (node (ref "Q44") (pin "1") (pinfunction "G_1") (pintype "passive"))
    )
    (net (code "34") (name "Net-(Q41-S)") (class "Default")
      (node (ref "Q41") (pin "2") (pinfunction "S_2") (pintype "passive"))
      (node (ref "Q42") (pin "3") (pinfunction "D_3") (pintype "passive"))
    )
    (net (code "35") (name "Net-(Q45-D)") (class "Default")
      (node (ref "Q45") (pin "3") (pinfunction "D_3") (pintype "passive"))
      (node (ref "Q47") (pin "3") (pinfunction "D_3") (pintype "passive"))
      (node (ref "Q48") (pin "3") (pinfunction "D_3") (pintype "passive"))
    )
    (net (code "36") (name "Net-(Q45-G)") (class "Default")
      (node (ref "Q45") (pin "1") (pinfunction "G_1") (pintype "passive"))
      (node (ref "Q48") (pin "1") (pinfunction "G_1") (pintype "passive"))
    )
    (net (code "37") (name "Net-(Q45-S)") (class "Default")
      (node (ref "Q45") (pin "2") (pinfunction "S_2") (pintype "passive"))
      (node (ref "Q46") (pin "3") (pinfunction "D_3") (pintype "passive"))
    )
    (net (code "38") (name "Net-(Q46-G)") (class "Default")
      (node (ref "Q46") (pin "1") (pinfunction "G_1") (pintype "passive"))
      (node (ref "Q47") (pin "1") (pinfunction "G_1") (pintype "passive"))
    )
    (net (code "39") (name "Net-(Q49-D)") (class "Default")
      (node (ref "Q49") (pin "3") (pinfunction "D_3") (pintype "passive"))
      (node (ref "Q51") (pin "3") (pinfunction "D_3") (pintype "passive"))
      (node (ref "Q52") (pin "3") (pinfunction "D_3") (pintype "passive"))
    )
    (net (code "40") (name "Net-(Q49-G)") (class "Default")
      (node (ref "Q49") (pin "1") (pinfunction "G_1") (pintype "passive"))
      (node (ref "Q52") (pin "1") (pinfunction "G_1") (pintype "passive"))
    )
    (net (code "41") (name "Net-(Q49-S)") (class "Default")
      (node (ref "Q49") (pin "2") (pinfunction "S_2") (pintype "passive"))
      (node (ref "Q50") (pin "3") (pinfunction "D_3") (pintype "passive"))
    )
    (net (code "42") (name "Net-(Q50-G)") (class "Default")
      (node (ref "Q50") (pin "1") (pinfunction "G_1") (pintype "passive"))
      (node (ref "Q51") (pin "1") (pinfunction "G_1") (pintype "passive"))
    )
    (net (code "43") (name "Net-(Q53-D)") (class "Default")
      (node (ref "Q53") (pin "3") (pinfunction "D_3") (pintype "passive"))
      (node (ref "Q55") (pin "3") (pinfunction "D_3") (pintype "passive"))
      (node (ref "Q56") (pin "3") (pinfunction "D_3") (pintype "passive"))
    )
    (net (code "44") (name "Net-(Q53-G)") (class "Default")
      (node (ref "Q53") (pin "1") (pinfunction "G_1") (pintype "passive"))
      (node (ref "Q56") (pin "1") (pinfunction "G_1") (pintype "passive"))
    )
    (net (code "45") (name "Net-(Q53-S)") (class "Default")
      (node (ref "Q53") (pin "2") (pinfunction "S_2") (pintype "passive"))
      (node (ref "Q54") (pin "3") (pinfunction "D_3") (pintype "passive"))
    )
    (net (code "46") (name "Net-(Q54-G)") (class "Default")
      (node (ref "Q54") (pin "1") (pinfunction "G_1") (pintype "passive"))
      (node (ref "Q55") (pin "1") (pinfunction "G_1") (pintype "passive"))
    )
    (net (code "47") (name "Net-(Q57-D)") (class "Default")
      (node (ref "Q57") (pin "3") (pinfunction "D_3") (pintype "passive"))
      (node (ref "Q59") (pin "3") (pinfunction "D_3") (pintype "passive"))
      (node (ref "Q60") (pin "3") (pinfunction "D_3") (pintype "passive"))
    )
    (net (code "48") (name "Net-(Q57-G)") (class "Default")
      (node (ref "Q57") (pin "1") (pinfunction "G_1") (pintype "passive"))
      (node (ref "Q60") (pin "1") (pinfunction "G_1") (pintype "passive"))
    )
    (net (code "49") (name "Net-(Q57-S)") (class "Default")
      (node (ref "Q57") (pin "2") (pinfunction "S_2") (pintype "passive"))
      (node (ref "Q58") (pin "3") (pinfunction "D_3") (pintype "passive"))
    )
    (net (code "50") (name "Net-(Q58-G)") (class "Default")
      (node (ref "Q58") (pin "1") (pinfunction "G_1") (pintype "passive"))
      (node (ref "Q59") (pin "1") (pinfunction "G_1") (pintype "passive"))
    )
    (net (code "51") (name "Net-(Q61-D)") (class "Default")
      (node (ref "Q61") (pin "3") (pinfunction "D_3") (pintype "passive"))
      (node (ref "Q63") (pin "3") (pinfunction "D_3") (pintype "passive"))
      (node (ref "Q64") (pin "3") (pinfunction "D_3") (pintype "passive"))
    )
    (net (code "52") (name "Net-(Q61-G)") (class "Default")
      (node (ref "Q61") (pin "1") (pinfunction "G_1") (pintype "passive"))
      (node (ref "Q64") (pin "1") (pinfunction "G_1") (pintype "passive"))
    )
    (net (code "53") (name "Net-(Q61-S)") (class "Default")
      (node (ref "Q61") (pin "2") (pinfunction "S_2") (pintype "passive"))
      (node (ref "Q62") (pin "3") (pinfunction "D_3") (pintype "passive"))
    )
    (net (code "54") (name "Net-(Q62-G)") (class "Default")
      (node (ref "Q62") (pin "1") (pinfunction "G_1") (pintype "passive"))
      (node (ref "Q63") (pin "1") (pinfunction "G_1") (pintype "passive"))
    )
    (net (code "55") (name "Net-(Q65-D)") (class "Default")
      (node (ref "Q65") (pin "3") (pinfunction "D_3") (pintype "passive"))
      (node (ref "Q67") (pin "3") (pinfunction "D_3") (pintype "passive"))
      (node (ref "Q68") (pin "3") (pinfunction "D_3") (pintype "passive"))
    )
    (net (code "56") (name "Net-(Q65-G)") (class "Default")
      (node (ref "Q65") (pin "1") (pinfunction "G_1") (pintype "passive"))
      (node (ref "Q68") (pin "1") (pinfunction "G_1") (pintype "passive"))
    )
    (net (code "57") (name "Net-(Q65-S)") (class "Default")
      (node (ref "Q65") (pin "2") (pinfunction "S_2") (pintype "passive"))
      (node (ref "Q66") (pin "3") (pinfunction "D_3") (pintype "passive"))
    )
    (net (code "58") (name "Net-(Q66-G)") (class "Default")
      (node (ref "Q66") (pin "1") (pinfunction "G_1") (pintype "passive"))
      (node (ref "Q67") (pin "1") (pinfunction "G_1") (pintype "passive"))
    )
    (net (code "59") (name "Net-(Q69-D)") (class "Default")
      (node (ref "Q69") (pin "3") (pinfunction "D_3") (pintype "passive"))
      (node (ref "Q71") (pin "3") (pinfunction "D_3") (pintype "passive"))
      (node (ref "Q72") (pin "3") (pinfunction "D_3") (pintype "passive"))
    )
    (net (code "60") (name "Net-(Q69-G)") (class "Default")
      (node (ref "Q69") (pin "1") (pinfunction "G_1") (pintype "passive"))
      (node (ref "Q72") (pin "1") (pinfunction "G_1") (pintype "passive"))
    )
    (net (code "61") (name "Net-(Q69-S)") (class "Default")
      (node (ref "Q69") (pin "2") (pinfunction "S_2") (pintype "passive"))
      (node (ref "Q70") (pin "3") (pinfunction "D_3") (pintype "passive"))
    )
    (net (code "62") (name "Net-(Q70-G)") (class "Default")
      (node (ref "Q70") (pin "1") (pinfunction "G_1") (pintype "passive"))
      (node (ref "Q71") (pin "1") (pinfunction "G_1") (pintype "passive"))
    )
    (net (code "63") (name "Net-(Q73-D)") (class "Default")
      (node (ref "Q73") (pin "3") (pinfunction "D_3") (pintype "passive"))
      (node (ref "Q75") (pin "3") (pinfunction "D_3") (pintype "passive"))
      (node (ref "Q76") (pin "3") (pinfunction "D_3") (pintype "passive"))
    )
    (net (code "64") (name "Net-(Q73-G)") (class "Default")
      (node (ref "Q73") (pin "1") (pinfunction "G_1") (pintype "passive"))
      (node (ref "Q76") (pin "1") (pinfunction "G_1") (pintype "passive"))
    )
    (net (code "65") (name "Net-(Q73-S)") (class "Default")
      (node (ref "Q73") (pin "2") (pinfunction "S_2") (pintype "passive"))
      (node (ref "Q74") (pin "3") (pinfunction "D_3") (pintype "passive"))
    )
    (net (code "66") (name "Net-(Q74-G)") (class "Default")
      (node (ref "Q74") (pin "1") (pinfunction "G_1") (pintype "passive"))
      (node (ref "Q75") (pin "1") (pinfunction "G_1") (pintype "passive"))
    )
    (net (code "67") (name "Net-(Q77-D)") (class "Default")
      (node (ref "Q77") (pin "3") (pinfunction "D_3") (pintype "passive"))
      (node (ref "Q79") (pin "3") (pinfunction "D_3") (pintype "passive"))
      (node (ref "Q80") (pin "3") (pinfunction "D_3") (pintype "passive"))
    )
    (net (code "68") (name "Net-(Q77-G)") (class "Default")
      (node (ref "Q77") (pin "1") (pinfunction "G_1") (pintype "passive"))
      (node (ref "Q80") (pin "1") (pinfunction "G_1") (pintype "passive"))
    )
    (net (code "69") (name "Net-(Q77-S)") (class "Default")
      (node (ref "Q77") (pin "2") (pinfunction "S_2") (pintype "passive"))
      (node (ref "Q78") (pin "3") (pinfunction "D_3") (pintype "passive"))
    )
    (net (code "70") (name "Net-(Q78-G)") (class "Default")
      (node (ref "Q78") (pin "1") (pinfunction "G_1") (pintype "passive"))
      (node (ref "Q79") (pin "1") (pinfunction "G_1") (pintype "passive"))
    )
    (net (code "71") (name "Net-(Q81-D)") (class "Default")
      (node (ref "Q81") (pin "3") (pinfunction "D_3") (pintype "passive"))
      (node (ref "Q83") (pin "3") (pinfunction "D_3") (pintype "passive"))
      (node (ref "Q84") (pin "3") (pinfunction "D_3") (pintype "passive"))
    )
    (net (code "72") (name "Net-(Q81-G)") (class "Default")
      (node (ref "Q81") (pin "1") (pinfunction "G_1") (pintype "passive"))
      (node (ref "Q84") (pin "1") (pinfunction "G_1") (pintype "passive"))
    )
    (net (code "73") (name "Net-(Q81-S)") (class "Default")
      (node (ref "Q81") (pin "2") (pinfunction "S_2") (pintype "passive"))
      (node (ref "Q82") (pin "3") (pinfunction "D_3") (pintype "passive"))
    )
    (net (code "74") (name "Net-(Q82-G)") (class "Default")
      (node (ref "Q82") (pin "1") (pinfunction "G_1") (pintype "passive"))
      (node (ref "Q83") (pin "1") (pinfunction "G_1") (pintype "passive"))
    )
    (net (code "75") (name "Net-(Q85-D)") (class "Default")
      (node (ref "Q85") (pin "3") (pinfunction "D_3") (pintype "passive"))
      (node (ref "Q87") (pin "3") (pinfunction "D_3") (pintype "passive"))
      (node (ref "Q88") (pin "3") (pinfunction "D_3") (pintype "passive"))
    )
    (net (code "76") (name "Net-(Q85-G)") (class "Default")
      (node (ref "Q85") (pin "1") (pinfunction "G_1") (pintype "passive"))
      (node (ref "Q88") (pin "1") (pinfunction "G_1") (pintype "passive"))
    )
    (net (code "77") (name "Net-(Q85-S)") (class "Default")
      (node (ref "Q85") (pin "2") (pinfunction "S_2") (pintype "passive"))
      (node (ref "Q86") (pin "3") (pinfunction "D_3") (pintype "passive"))
    )
    (net (code "78") (name "Net-(Q86-G)") (class "Default")
      (node (ref "Q86") (pin "1") (pinfunction "G_1") (pintype "passive"))
      (node (ref "Q87") (pin "1") (pinfunction "G_1") (pintype "passive"))
    )
    (net (code "79") (name "Net-(Q89-D)") (class "Default")
      (node (ref "Q89") (pin "3") (pinfunction "D_3") (pintype "passive"))
      (node (ref "Q91") (pin "3") (pinfunction "D_3") (pintype "passive"))
      (node (ref "Q92") (pin "3") (pinfunction "D_3") (pintype "passive"))
    )
    (net (code "80") (name "Net-(Q89-G)") (class "Default")
      (node (ref "Q89") (pin "1") (pinfunction "G_1") (pintype "passive"))
      (node (ref "Q92") (pin "1") (pinfunction "G_1") (pintype "passive"))
    )
    (net (code "81") (name "Net-(Q89-S)") (class "Default")
      (node (ref "Q89") (pin "2") (pinfunction "S_2") (pintype "passive"))
      (node (ref "Q90") (pin "3") (pinfunction "D_3") (pintype "passive"))
    )
    (net (code "82") (name "Net-(Q90-G)") (class "Default")
      (node (ref "Q90") (pin "1") (pinfunction "G_1") (pintype "passive"))
      (node (ref "Q91") (pin "1") (pinfunction "G_1") (pintype "passive"))
    )
    (net (code "83") (name "Net-(Q93-D)") (class "Default")
      (node (ref "Q93") (pin "3") (pinfunction "D_3") (pintype "passive"))
      (node (ref "Q95") (pin "3") (pinfunction "D_3") (pintype "passive"))
      (node (ref "Q96") (pin "3") (pinfunction "D_3") (pintype "passive"))
    )
    (net (code "84") (name "Net-(Q93-G)") (class "Default")
      (node (ref "Q93") (pin "1") (pinfunction "G_1") (pintype "passive"))
      (node (ref "Q96") (pin "1") (pinfunction "G_1") (pintype "passive"))
    )
    (net (code "85") (name "Net-(Q93-S)") (class "Default")
      (node (ref "Q93") (pin "2") (pinfunction "S_2") (pintype "passive"))
      (node (ref "Q94") (pin "3") (pinfunction "D_3") (pintype "passive"))
    )
    (net (code "86") (name "Net-(Q94-G)") (class "Default")
      (node (ref "Q94") (pin "1") (pinfunction "G_1") (pintype "passive"))
      (node (ref "Q95") (pin "1") (pinfunction "G_1") (pintype "passive"))
    )
    (net (code "87") (name "Net-(Q97-S)") (class "Default")
      (node (ref "Q97") (pin "2") (pinfunction "S_2") (pintype "passive"))
      (node (ref "Q98") (pin "3") (pinfunction "D_3") (pintype "passive"))
    )
    (net (code "88") (name "Net-(Q98-G)") (class "Default")
      (node (ref "Q98") (pin "1") (pinfunction "G_1") (pintype "passive"))
      (node (ref "Q99") (pin "1") (pinfunction "G_1") (pintype "passive"))
    )
    (net (code "89") (name "Net-(Q100-D)") (class "Default")
      (node (ref "Q100") (pin "3") (pinfunction "D_3") (pintype "passive"))
      (node (ref "Q97") (pin "3") (pinfunction "D_3") (pintype "passive"))
      (node (ref "Q99") (pin "3") (pinfunction "D_3") (pintype "passive"))
    )
    (net (code "90") (name "Net-(Q100-G)") (class "Default")
      (node (ref "Q100") (pin "1") (pinfunction "G_1") (pintype "passive"))
      (node (ref "Q97") (pin "1") (pinfunction "G_1") (pintype "passive"))
    )
    (net (code "91") (name "Net-(Q100-S)") (class "Default")
      (node (ref "IC1") (pin "12") (pinfunction "12_12") (pintype "passive"))
      (node (ref "IC1") (pin "14") (pinfunction "14_14") (pintype "passive"))
      (node (ref "IC1") (pin "16") (pinfunction "16_16") (pintype "passive"))
      (node (ref "IC2") (pin "12") (pinfunction "12_12") (pintype "passive"))
      (node (ref "IC2") (pin "14") (pinfunction "14_14") (pintype "passive"))
      (node (ref "IC2") (pin "16") (pinfunction "16_16") (pintype "passive"))
      (node (ref "IC3") (pin "16") (pinfunction "16_16") (pintype "passive"))
      (node (ref "IC3") (pin "9") (pinfunction "9_9") (pintype "passive"))
      (node (ref "IC4") (pin "16") (pinfunction "16_16") (pintype "passive"))
      (node (ref "IC4") (pin "9") (pinfunction "9_9") (pintype "passive"))
      (node (ref "IC5") (pin "28") (pinfunction "28_28") (pintype "passive"))
      (node (ref "IC6") (pin "16") (pinfunction "16_16") (pintype "passive"))
      (node (ref "Q100") (pin "2") (pinfunction "S_2") (pintype "passive"))
      (node (ref "Q103") (pin "2") (pinfunction "S_2") (pintype "passive"))
      (node (ref "Q104") (pin "2") (pinfunction "S_2") (pintype "passive"))
      (node (ref "Q107") (pin "2") (pinfunction "S_2") (pintype "passive"))
      (node (ref "Q108") (pin "2") (pinfunction "S_2") (pintype "passive"))
      (node (ref "Q11") (pin "2") (pinfunction "S_2") (pintype "passive"))
      (node (ref "Q111") (pin "2") (pinfunction "S_2") (pintype "passive"))
      (node (ref "Q112") (pin "2") (pinfunction "S_2") (pintype "passive"))
      (node (ref "Q115") (pin "2") (pinfunction "S_2") (pintype "passive"))
      (node (ref "Q116") (pin "2") (pinfunction "S_2") (pintype "passive"))
      (node (ref "Q119") (pin "2") (pinfunction "S_2") (pintype "passive"))
      (node (ref "Q12") (pin "2") (pinfunction "S_2") (pintype "passive"))
      (node (ref "Q120") (pin "2") (pinfunction "S_2") (pintype "passive"))
      (node (ref "Q123") (pin "2") (pinfunction "S_2") (pintype "passive"))
      (node (ref "Q124") (pin "2") (pinfunction "S_2") (pintype "passive"))
      (node (ref "Q127") (pin "2") (pinfunction "S_2") (pintype "passive"))
      (node (ref "Q128") (pin "2") (pinfunction "S_2") (pintype "passive"))
      (node (ref "Q131") (pin "2") (pinfunction "S_2") (pintype "passive"))
      (node (ref "Q132") (pin "2") (pinfunction "S_2") (pintype "passive"))
      (node (ref "Q135") (pin "2") (pinfunction "S_2") (pintype "passive"))
      (node (ref "Q136") (pin "2") (pinfunction "S_2") (pintype "passive"))
      (node (ref "Q139") (pin "2") (pinfunction "S_2") (pintype "passive"))
      (node (ref "Q140") (pin "2") (pinfunction "S_2") (pintype "passive"))
      (node (ref "Q143") (pin "2") (pinfunction "S_2") (pintype "passive"))
      (node (ref "Q144") (pin "2") (pinfunction "S_2") (pintype "passive"))
      (node (ref "Q147") (pin "2") (pinfunction "S_2") (pintype "passive"))
      (node (ref "Q148") (pin "2") (pinfunction "S_2") (pintype "passive"))
      (node (ref "Q15") (pin "2") (pinfunction "S_2") (pintype "passive"))
      (node (ref "Q151") (pin "2") (pinfunction "S_2") (pintype "passive"))
      (node (ref "Q152") (pin "2") (pinfunction "S_2") (pintype "passive"))
      (node (ref "Q155") (pin "2") (pinfunction "S_2") (pintype "passive"))
      (node (ref "Q156") (pin "2") (pinfunction "S_2") (pintype "passive"))
      (node (ref "Q159") (pin "2") (pinfunction "S_2") (pintype "passive"))
      (node (ref "Q16") (pin "2") (pinfunction "S_2") (pintype "passive"))
      (node (ref "Q160") (pin "2") (pinfunction "S_2") (pintype "passive"))
      (node (ref "Q163") (pin "2") (pinfunction "S_2") (pintype "passive"))
      (node (ref "Q164") (pin "2") (pinfunction "S_2") (pintype "passive"))
      (node (ref "Q167") (pin "2") (pinfunction "S_2") (pintype "passive"))
      (node (ref "Q168") (pin "2") (pinfunction "S_2") (pintype "passive"))
      (node (ref "Q171") (pin "2") (pinfunction "S_2") (pintype "passive"))
      (node (ref "Q172") (pin "2") (pinfunction "S_2") (pintype "passive"))
      (node (ref "Q175") (pin "2") (pinfunction "S_2") (pintype "passive"))
      (node (ref "Q176") (pin "2") (pinfunction "S_2") (pintype "passive"))
      (node (ref "Q179") (pin "2") (pinfunction "S_2") (pintype "passive"))
      (node (ref "Q180") (pin "2") (pinfunction "S_2") (pintype "passive"))
      (node (ref "Q183") (pin "2") (pinfunction "S_2") (pintype "passive"))
      (node (ref "Q184") (pin "2") (pinfunction "S_2") (pintype "passive"))
      (node (ref "Q187") (pin "2") (pinfunction "S_2") (pintype "passive"))
      (node (ref "Q188") (pin "2") (pinfunction "S_2") (pintype "passive"))
      (node (ref "Q19") (pin "2") (pinfunction "S_2") (pintype "passive"))
      (node (ref "Q191") (pin "2") (pinfunction "S_2") (pintype "passive"))
      (node (ref "Q192") (pin "2") (pinfunction "S_2") (pintype "passive"))
      (node (ref "Q195") (pin "2") (pinfunction "S_2") (pintype "passive"))
      (node (ref "Q196") (pin "2") (pinfunction "S_2") (pintype "passive"))
      (node (ref "Q199") (pin "2") (pinfunction "S_2") (pintype "passive"))
      (node (ref "Q20") (pin "2") (pinfunction "S_2") (pintype "passive"))
      (node (ref "Q200") (pin "2") (pinfunction "S_2") (pintype "passive"))
      (node (ref "Q203") (pin "2") (pinfunction "S_2") (pintype "passive"))
      (node (ref "Q204") (pin "2") (pinfunction "S_2") (pintype "passive"))
      (node (ref "Q207") (pin "2") (pinfunction "S_2") (pintype "passive"))
      (node (ref "Q208") (pin "2") (pinfunction "S_2") (pintype "passive"))
      (node (ref "Q211") (pin "2") (pinfunction "S_2") (pintype "passive"))
      (node (ref "Q212") (pin "2") (pinfunction "S_2") (pintype "passive"))
      (node (ref "Q215") (pin "2") (pinfunction "S_2") (pintype "passive"))
      (node (ref "Q216") (pin "2") (pinfunction "S_2") (pintype "passive"))
      (node (ref "Q219") (pin "2") (pinfunction "S_2") (pintype "passive"))
      (node (ref "Q220") (pin "2") (pinfunction "S_2") (pintype "passive"))
      (node (ref "Q223") (pin "2") (pinfunction "S_2") (pintype "passive"))
      (node (ref "Q224") (pin "2") (pinfunction "S_2") (pintype "passive"))
      (node (ref "Q226") (pin "2") (pinfunction "S_2") (pintype "passive"))
      (node (ref "Q228") (pin "2") (pinfunction "S_2") (pintype "passive"))
      (node (ref "Q23") (pin "2") (pinfunction "S_2") (pintype "passive"))
      (node (ref "Q230") (pin "2") (pinfunction "S_2") (pintype "passive"))
      (node (ref "Q232") (pin "2") (pinfunction "S_2") (pintype "passive"))
      (node (ref "Q234") (pin "2") (pinfunction "S_2") (pintype "passive"))
      (node (ref "Q236") (pin "2") (pinfunction "S_2") (pintype "passive"))
      (node (ref "Q238") (pin "2") (pinfunction "S_2") (pintype "passive"))
      (node (ref "Q24") (pin "2") (pinfunction "S_2") (pintype "passive"))
      (node (ref "Q240") (pin "2") (pinfunction "S_2") (pintype "passive"))
      (node (ref "Q242") (pin "2") (pinfunction "S_2") (pintype "passive"))
      (node (ref "Q244") (pin "2") (pinfunction "S_2") (pintype "passive"))
      (node (ref "Q246") (pin "2") (pinfunction "S_2") (pintype "passive"))
      (node (ref "Q248") (pin "2") (pinfunction "S_2") (pintype "passive"))
      (node (ref "Q250") (pin "2") (pinfunction "S_2") (pintype "passive"))
      (node (ref "Q252") (pin "2") (pinfunction "S_2") (pintype "passive"))
      (node (ref "Q254") (pin "2") (pinfunction "S_2") (pintype "passive"))
      (node (ref "Q256") (pin "2") (pinfunction "S_2") (pintype "passive"))
      (node (ref "Q258") (pin "2") (pinfunction "S_2") (pintype "passive"))
      (node (ref "Q260") (pin "2") (pinfunction "S_2") (pintype "passive"))
      (node (ref "Q27") (pin "2") (pinfunction "S_2") (pintype "passive"))
      (node (ref "Q28") (pin "2") (pinfunction "S_2") (pintype "passive"))
      (node (ref "Q3") (pin "2") (pinfunction "S_2") (pintype "passive"))
      (node (ref "Q31") (pin "2") (pinfunction "S_2") (pintype "passive"))
      (node (ref "Q32") (pin "2") (pinfunction "S_2") (pintype "passive"))
      (node (ref "Q35") (pin "2") (pinfunction "S_2") (pintype "passive"))
      (node (ref "Q36") (pin "2") (pinfunction "S_2") (pintype "passive"))
      (node (ref "Q39") (pin "2") (pinfunction "S_2") (pintype "passive"))
      (node (ref "Q4") (pin "2") (pinfunction "S_2") (pintype "passive"))
      (node (ref "Q40") (pin "2") (pinfunction "S_2") (pintype "passive"))
      (node (ref "Q43") (pin "2") (pinfunction "S_2") (pintype "passive"))
      (node (ref "Q44") (pin "2") (pinfunction "S_2") (pintype "passive"))
      (node (ref "Q47") (pin "2") (pinfunction "S_2") (pintype "passive"))
      (node (ref "Q48") (pin "2") (pinfunction "S_2") (pintype "passive"))
      (node (ref "Q51") (pin "2") (pinfunction "S_2") (pintype "passive"))
      (node (ref "Q52") (pin "2") (pinfunction "S_2") (pintype "passive"))
      (node (ref "Q55") (pin "2") (pinfunction "S_2") (pintype "passive"))
      (node (ref "Q56") (pin "2") (pinfunction "S_2") (pintype "passive"))
      (node (ref "Q59") (pin "2") (pinfunction "S_2") (pintype "passive"))
      (node (ref "Q60") (pin "2") (pinfunction "S_2") (pintype "passive"))
      (node (ref "Q63") (pin "2") (pinfunction "S_2") (pintype "passive"))
      (node (ref "Q64") (pin "2") (pinfunction "S_2") (pintype "passive"))
      (node (ref "Q67") (pin "2") (pinfunction "S_2") (pintype "passive"))
      (node (ref "Q68") (pin "2") (pinfunction "S_2") (pintype "passive"))
      (node (ref "Q7") (pin "2") (pinfunction "S_2") (pintype "passive"))
      (node (ref "Q71") (pin "2") (pinfunction "S_2") (pintype "passive"))
      (node (ref "Q72") (pin "2") (pinfunction "S_2") (pintype "passive"))
      (node (ref "Q75") (pin "2") (pinfunction "S_2") (pintype "passive"))
      (node (ref "Q76") (pin "2") (pinfunction "S_2") (pintype "passive"))
      (node (ref "Q79") (pin "2") (pinfunction "S_2") (pintype "passive"))
      (node (ref "Q8") (pin "2") (pinfunction "S_2") (pintype "passive"))
      (node (ref "Q80") (pin "2") (pinfunction "S_2") (pintype "passive"))
      (node (ref "Q83") (pin "2") (pinfunction "S_2") (pintype "passive"))
      (node (ref "Q84") (pin "2") (pinfunction "S_2") (pintype "passive"))
      (node (ref "Q87") (pin "2") (pinfunction "S_2") (pintype "passive"))
      (node (ref "Q88") (pin "2") (pinfunction "S_2") (pintype "passive"))
      (node (ref "Q91") (pin "2") (pinfunction "S_2") (pintype "passive"))
      (node (ref "Q92") (pin "2") (pinfunction "S_2") (pintype "passive"))
      (node (ref "Q95") (pin "2") (pinfunction "S_2") (pintype "passive"))
      (node (ref "Q96") (pin "2") (pinfunction "S_2") (pintype "passive"))
      (node (ref "Q99") (pin "2") (pinfunction "S_2") (pintype "passive"))
    )
    (net (code "92") (name "Net-(Q101-D)") (class "Default")
      (node (ref "Q101") (pin "3") (pinfunction "D_3") (pintype "passive"))
      (node (ref "Q103") (pin "3") (pinfunction "D_3") (pintype "passive"))
      (node (ref "Q104") (pin "3") (pinfunction "D_3") (pintype "passive"))
    )
    (net (code "93") (name "Net-(Q101-G)") (class "Default")
      (node (ref "Q101") (pin "1") (pinfunction "G_1") (pintype "passive"))
      (node (ref "Q104") (pin "1") (pinfunction "G_1") (pintype "passive"))
    )
    (net (code "94") (name "Net-(Q101-S)") (class "Default")
      (node (ref "Q101") (pin "2") (pinfunction "S_2") (pintype "passive"))
      (node (ref "Q102") (pin "3") (pinfunction "D_3") (pintype "passive"))
    )
    (net (code "95") (name "Net-(Q102-G)") (class "Default")
      (node (ref "Q102") (pin "1") (pinfunction "G_1") (pintype "passive"))
      (node (ref "Q103") (pin "1") (pinfunction "G_1") (pintype "passive"))
    )
    (net (code "96") (name "Net-(Q105-D)") (class "Default")
      (node (ref "Q105") (pin "3") (pinfunction "D_3") (pintype "passive"))
      (node (ref "Q107") (pin "3") (pinfunction "D_3") (pintype "passive"))
      (node (ref "Q108") (pin "3") (pinfunction "D_3") (pintype "passive"))
    )
    (net (code "97") (name "Net-(Q105-G)") (class "Default")
      (node (ref "Q105") (pin "1") (pinfunction "G_1") (pintype "passive"))
      (node (ref "Q108") (pin "1") (pinfunction "G_1") (pintype "passive"))
    )
    (net (code "98") (name "Net-(Q105-S)") (class "Default")
      (node (ref "Q105") (pin "2") (pinfunction "S_2") (pintype "passive"))
      (node (ref "Q106") (pin "3") (pinfunction "D_3") (pintype "passive"))
    )
    (net (code "99") (name "Net-(Q106-G)") (class "Default")
      (node (ref "Q106") (pin "1") (pinfunction "G_1") (pintype "passive"))
      (node (ref "Q107") (pin "1") (pinfunction "G_1") (pintype "passive"))
    )
    (net (code "100") (name "Net-(Q109-D)") (class "Default")
      (node (ref "Q109") (pin "3") (pinfunction "D_3") (pintype "passive"))
      (node (ref "Q111") (pin "3") (pinfunction "D_3") (pintype "passive"))
      (node (ref "Q112") (pin "3") (pinfunction "D_3") (pintype "passive"))
    )
    (net (code "101") (name "Net-(Q109-G)") (class "Default")
      (node (ref "Q109") (pin "1") (pinfunction "G_1") (pintype "passive"))
      (node (ref "Q112") (pin "1") (pinfunction "G_1") (pintype "passive"))
    )
    (net (code "102") (name "Net-(Q109-S)") (class "Default")
      (node (ref "Q109") (pin "2") (pinfunction "S_2") (pintype "passive"))
      (node (ref "Q110") (pin "3") (pinfunction "D_3") (pintype "passive"))
    )
    (net (code "103") (name "Net-(Q110-G)") (class "Default")
      (node (ref "Q110") (pin "1") (pinfunction "G_1") (pintype "passive"))
      (node (ref "Q111") (pin "1") (pinfunction "G_1") (pintype "passive"))
    )
    (net (code "104") (name "Net-(Q113-D)") (class "Default")
      (node (ref "Q113") (pin "3") (pinfunction "D_3") (pintype "passive"))
      (node (ref "Q115") (pin "3") (pinfunction "D_3") (pintype "passive"))
      (node (ref "Q116") (pin "3") (pinfunction "D_3") (pintype "passive"))
    )
    (net (code "105") (name "Net-(Q113-G)") (class "Default")
      (node (ref "Q113") (pin "1") (pinfunction "G_1") (pintype "passive"))
      (node (ref "Q116") (pin "1") (pinfunction "G_1") (pintype "passive"))
    )
    (net (code "106") (name "Net-(Q113-S)") (class "Default")
      (node (ref "Q113") (pin "2") (pinfunction "S_2") (pintype "passive"))
      (node (ref "Q114") (pin "3") (pinfunction "D_3") (pintype "passive"))
    )
    (net (code "107") (name "Net-(Q114-G)") (class "Default")
      (node (ref "Q114") (pin "1") (pinfunction "G_1") (pintype "passive"))
      (node (ref "Q115") (pin "1") (pinfunction "G_1") (pintype "passive"))
    )
    (net (code "108") (name "Net-(Q117-D)") (class "Default")
      (node (ref "Q117") (pin "3") (pinfunction "D_3") (pintype "passive"))
      (node (ref "Q119") (pin "3") (pinfunction "D_3") (pintype "passive"))
      (node (ref "Q120") (pin "3") (pinfunction "D_3") (pintype "passive"))
    )
    (net (code "109") (name "Net-(Q117-G)") (class "Default")
      (node (ref "Q117") (pin "1") (pinfunction "G_1") (pintype "passive"))
      (node (ref "Q120") (pin "1") (pinfunction "G_1") (pintype "passive"))
    )
    (net (code "110") (name "Net-(Q117-S)") (class "Default")
      (node (ref "Q117") (pin "2") (pinfunction "S_2") (pintype "passive"))
      (node (ref "Q118") (pin "3") (pinfunction "D_3") (pintype "passive"))
    )
    (net (code "111") (name "Net-(Q118-G)") (class "Default")
      (node (ref "Q118") (pin "1") (pinfunction "G_1") (pintype "passive"))
      (node (ref "Q119") (pin "1") (pinfunction "G_1") (pintype "passive"))
    )
    (net (code "112") (name "Net-(Q121-D)") (class "Default")
      (node (ref "Q121") (pin "3") (pinfunction "D_3") (pintype "passive"))
      (node (ref "Q123") (pin "3") (pinfunction "D_3") (pintype "passive"))
      (node (ref "Q124") (pin "3") (pinfunction "D_3") (pintype "passive"))
    )
    (net (code "113") (name "Net-(Q121-G)") (class "Default")
      (node (ref "Q121") (pin "1") (pinfunction "G_1") (pintype "passive"))
      (node (ref "Q124") (pin "1") (pinfunction "G_1") (pintype "passive"))
    )
    (net (code "114") (name "Net-(Q121-S)") (class "Default")
      (node (ref "Q121") (pin "2") (pinfunction "S_2") (pintype "passive"))
      (node (ref "Q122") (pin "3") (pinfunction "D_3") (pintype "passive"))
    )
    (net (code "115") (name "Net-(Q122-G)") (class "Default")
      (node (ref "Q122") (pin "1") (pinfunction "G_1") (pintype "passive"))
      (node (ref "Q123") (pin "1") (pinfunction "G_1") (pintype "passive"))
    )
    (net (code "116") (name "Net-(Q125-D)") (class "Default")
      (node (ref "Q125") (pin "3") (pinfunction "D_3") (pintype "passive"))
      (node (ref "Q127") (pin "3") (pinfunction "D_3") (pintype "passive"))
      (node (ref "Q128") (pin "3") (pinfunction "D_3") (pintype "passive"))
    )
    (net (code "117") (name "Net-(Q125-G)") (class "Default")
      (node (ref "Q125") (pin "1") (pinfunction "G_1") (pintype "passive"))
      (node (ref "Q128") (pin "1") (pinfunction "G_1") (pintype "passive"))
    )
    (net (code "118") (name "Net-(Q125-S)") (class "Default")
      (node (ref "Q125") (pin "2") (pinfunction "S_2") (pintype "passive"))
      (node (ref "Q126") (pin "3") (pinfunction "D_3") (pintype "passive"))
    )
    (net (code "119") (name "Net-(Q126-G)") (class "Default")
      (node (ref "Q126") (pin "1") (pinfunction "G_1") (pintype "passive"))
      (node (ref "Q127") (pin "1") (pinfunction "G_1") (pintype "passive"))
    )
    (net (code "120") (name "Net-(Q129-D)") (class "Default")
      (node (ref "Q129") (pin "3") (pinfunction "D_3") (pintype "passive"))
      (node (ref "Q131") (pin "3") (pinfunction "D_3") (pintype "passive"))
      (node (ref "Q132") (pin "3") (pinfunction "D_3") (pintype "passive"))
    )
    (net (code "121") (name "Net-(Q129-G)") (class "Default")
      (node (ref "Q129") (pin "1") (pinfunction "G_1") (pintype "passive"))
      (node (ref "Q132") (pin "1") (pinfunction "G_1") (pintype "passive"))
    )
    (net (code "122") (name "Net-(Q129-S)") (class "Default")
      (node (ref "Q129") (pin "2") (pinfunction "S_2") (pintype "passive"))
      (node (ref "Q130") (pin "3") (pinfunction "D_3") (pintype "passive"))
    )
    (net (code "123") (name "Net-(Q130-G)") (class "Default")
      (node (ref "Q130") (pin "1") (pinfunction "G_1") (pintype "passive"))
      (node (ref "Q131") (pin "1") (pinfunction "G_1") (pintype "passive"))
    )
    (net (code "124") (name "Net-(Q133-D)") (class "Default")
      (node (ref "Q133") (pin "3") (pinfunction "D_3") (pintype "passive"))
      (node (ref "Q135") (pin "3") (pinfunction "D_3") (pintype "passive"))
      (node (ref "Q136") (pin "3") (pinfunction "D_3") (pintype "passive"))
    )
    (net (code "125") (name "Net-(Q133-G)") (class "Default")
      (node (ref "Q133") (pin "1") (pinfunction "G_1") (pintype "passive"))
      (node (ref "Q136") (pin "1") (pinfunction "G_1") (pintype "passive"))
    )
    (net (code "126") (name "Net-(Q133-S)") (class "Default")
      (node (ref "Q133") (pin "2") (pinfunction "S_2") (pintype "passive"))
      (node (ref "Q134") (pin "3") (pinfunction "D_3") (pintype "passive"))
    )
    (net (code "127") (name "Net-(Q134-G)") (class "Default")
      (node (ref "Q134") (pin "1") (pinfunction "G_1") (pintype "passive"))
      (node (ref "Q135") (pin "1") (pinfunction "G_1") (pintype "passive"))
    )
    (net (code "128") (name "Net-(Q137-D)") (class "Default")
      (node (ref "Q137") (pin "3") (pinfunction "D_3") (pintype "passive"))
      (node (ref "Q139") (pin "3") (pinfunction "D_3") (pintype "passive"))
      (node (ref "Q140") (pin "3") (pinfunction "D_3") (pintype "passive"))
    )
    (net (code "129") (name "Net-(Q137-G)") (class "Default")
      (node (ref "Q137") (pin "1") (pinfunction "G_1") (pintype "passive"))
      (node (ref "Q140") (pin "1") (pinfunction "G_1") (pintype "passive"))
    )
    (net (code "130") (name "Net-(Q137-S)") (class "Default")
      (node (ref "Q137") (pin "2") (pinfunction "S_2") (pintype "passive"))
      (node (ref "Q138") (pin "3") (pinfunction "D_3") (pintype "passive"))
    )
    (net (code "131") (name "Net-(Q138-G)") (class "Default")
      (node (ref "Q138") (pin "1") (pinfunction "G_1") (pintype "passive"))
      (node (ref "Q139") (pin "1") (pinfunction "G_1") (pintype "passive"))
    )
    (net (code "132") (name "Net-(Q141-D)") (class "Default")
      (node (ref "Q141") (pin "3") (pinfunction "D_3") (pintype "passive"))
      (node (ref "Q143") (pin "3") (pinfunction "D_3") (pintype "passive"))
      (node (ref "Q144") (pin "3") (pinfunction "D_3") (pintype "passive"))
    )
    (net (code "133") (name "Net-(Q141-G)") (class "Default")
      (node (ref "Q141") (pin "1") (pinfunction "G_1") (pintype "passive"))
      (node (ref "Q144") (pin "1") (pinfunction "G_1") (pintype "passive"))
    )
    (net (code "134") (name "Net-(Q141-S)") (class "Default")
      (node (ref "Q141") (pin "2") (pinfunction "S_2") (pintype "passive"))
      (node (ref "Q142") (pin "3") (pinfunction "D_3") (pintype "passive"))
    )
    (net (code "135") (name "Net-(Q142-G)") (class "Default")
      (node (ref "Q142") (pin "1") (pinfunction "G_1") (pintype "passive"))
      (node (ref "Q143") (pin "1") (pinfunction "G_1") (pintype "passive"))
    )
    (net (code "136") (name "Net-(Q145-D)") (class "Default")
      (node (ref "Q145") (pin "3") (pinfunction "D_3") (pintype "passive"))
      (node (ref "Q147") (pin "3") (pinfunction "D_3") (pintype "passive"))
      (node (ref "Q148") (pin "3") (pinfunction "D_3") (pintype "passive"))
    )
    (net (code "137") (name "Net-(Q145-G)") (class "Default")
      (node (ref "Q145") (pin "1") (pinfunction "G_1") (pintype "passive"))
      (node (ref "Q148") (pin "1") (pinfunction "G_1") (pintype "passive"))
    )
    (net (code "138") (name "Net-(Q145-S)") (class "Default")
      (node (ref "Q145") (pin "2") (pinfunction "S_2") (pintype "passive"))
      (node (ref "Q146") (pin "3") (pinfunction "D_3") (pintype "passive"))
    )
    (net (code "139") (name "Net-(Q146-G)") (class "Default")
      (node (ref "Q146") (pin "1") (pinfunction "G_1") (pintype "passive"))
      (node (ref "Q147") (pin "1") (pinfunction "G_1") (pintype "passive"))
    )
    (net (code "140") (name "Net-(Q149-D)") (class "Default")
      (node (ref "Q149") (pin "3") (pinfunction "D_3") (pintype "passive"))
      (node (ref "Q151") (pin "3") (pinfunction "D_3") (pintype "passive"))
      (node (ref "Q152") (pin "3") (pinfunction "D_3") (pintype "passive"))
    )
    (net (code "141") (name "Net-(Q149-G)") (class "Default")
      (node (ref "Q149") (pin "1") (pinfunction "G_1") (pintype "passive"))
      (node (ref "Q152") (pin "1") (pinfunction "G_1") (pintype "passive"))
    )
    (net (code "142") (name "Net-(Q149-S)") (class "Default")
      (node (ref "Q149") (pin "2") (pinfunction "S_2") (pintype "passive"))
      (node (ref "Q150") (pin "3") (pinfunction "D_3") (pintype "passive"))
    )
    (net (code "143") (name "Net-(Q150-G)") (class "Default")
      (node (ref "Q150") (pin "1") (pinfunction "G_1") (pintype "passive"))
      (node (ref "Q151") (pin "1") (pinfunction "G_1") (pintype "passive"))
    )
    (net (code "144") (name "Net-(Q153-D)") (class "Default")
      (node (ref "Q153") (pin "3") (pinfunction "D_3") (pintype "passive"))
      (node (ref "Q155") (pin "3") (pinfunction "D_3") (pintype "passive"))
      (node (ref "Q156") (pin "3") (pinfunction "D_3") (pintype "passive"))
    )
    (net (code "145") (name "Net-(Q153-G)") (class "Default")
      (node (ref "Q153") (pin "1") (pinfunction "G_1") (pintype "passive"))
      (node (ref "Q156") (pin "1") (pinfunction "G_1") (pintype "passive"))
    )
    (net (code "146") (name "Net-(Q153-S)") (class "Default")
      (node (ref "Q153") (pin "2") (pinfunction "S_2") (pintype "passive"))
      (node (ref "Q154") (pin "3") (pinfunction "D_3") (pintype "passive"))
    )
    (net (code "147") (name "Net-(Q154-G)") (class "Default")
      (node (ref "Q154") (pin "1") (pinfunction "G_1") (pintype "passive"))
      (node (ref "Q155") (pin "1") (pinfunction "G_1") (pintype "passive"))
    )
    (net (code "148") (name "Net-(Q157-D)") (class "Default")
      (node (ref "Q157") (pin "3") (pinfunction "D_3") (pintype "passive"))
      (node (ref "Q159") (pin "3") (pinfunction "D_3") (pintype "passive"))
      (node (ref "Q160") (pin "3") (pinfunction "D_3") (pintype "passive"))
    )
    (net (code "149") (name "Net-(Q157-G)") (class "Default")
      (node (ref "Q157") (pin "1") (pinfunction "G_1") (pintype "passive"))
      (node (ref "Q160") (pin "1") (pinfunction "G_1") (pintype "passive"))
    )
    (net (code "150") (name "Net-(Q157-S)") (class "Default")
      (node (ref "Q157") (pin "2") (pinfunction "S_2") (pintype "passive"))
      (node (ref "Q158") (pin "3") (pinfunction "D_3") (pintype "passive"))
    )
    (net (code "151") (name "Net-(Q158-G)") (class "Default")
      (node (ref "Q158") (pin "1") (pinfunction "G_1") (pintype "passive"))
      (node (ref "Q159") (pin "1") (pinfunction "G_1") (pintype "passive"))
    )
    (net (code "152") (name "Net-(Q161-D)") (class "Default")
      (node (ref "Q161") (pin "3") (pinfunction "D_3") (pintype "passive"))
      (node (ref "Q163") (pin "3") (pinfunction "D_3") (pintype "passive"))
      (node (ref "Q164") (pin "3") (pinfunction "D_3") (pintype "passive"))
    )
    (net (code "153") (name "Net-(Q161-G)") (class "Default")
      (node (ref "Q161") (pin "1") (pinfunction "G_1") (pintype "passive"))
      (node (ref "Q164") (pin "1") (pinfunction "G_1") (pintype "passive"))
    )
    (net (code "154") (name "Net-(Q161-S)") (class "Default")
      (node (ref "Q161") (pin "2") (pinfunction "S_2") (pintype "passive"))
      (node (ref "Q162") (pin "3") (pinfunction "D_3") (pintype "passive"))
    )
    (net (code "155") (name "Net-(Q162-G)") (class "Default")
      (node (ref "Q162") (pin "1") (pinfunction "G_1") (pintype "passive"))
      (node (ref "Q163") (pin "1") (pinfunction "G_1") (pintype "passive"))
    )
    (net (code "156") (name "Net-(Q165-D)") (class "Default")
      (node (ref "Q165") (pin "3") (pinfunction "D_3") (pintype "passive"))
      (node (ref "Q167") (pin "3") (pinfunction "D_3") (pintype "passive"))
      (node (ref "Q168") (pin "3") (pinfunction "D_3") (pintype "passive"))
    )
    (net (code "157") (name "Net-(Q165-G)") (class "Default")
      (node (ref "Q165") (pin "1") (pinfunction "G_1") (pintype "passive"))
      (node (ref "Q168") (pin "1") (pinfunction "G_1") (pintype "passive"))
    )
    (net (code "158") (name "Net-(Q165-S)") (class "Default")
      (node (ref "Q165") (pin "2") (pinfunction "S_2") (pintype "passive"))
      (node (ref "Q166") (pin "3") (pinfunction "D_3") (pintype "passive"))
    )
    (net (code "159") (name "Net-(Q166-G)") (class "Default")
      (node (ref "Q166") (pin "1") (pinfunction "G_1") (pintype "passive"))
      (node (ref "Q167") (pin "1") (pinfunction "G_1") (pintype "passive"))
    )
    (net (code "160") (name "Net-(Q169-D)") (class "Default")
      (node (ref "Q169") (pin "3") (pinfunction "D_3") (pintype "passive"))
      (node (ref "Q171") (pin "3") (pinfunction "D_3") (pintype "passive"))
      (node (ref "Q172") (pin "3") (pinfunction "D_3") (pintype "passive"))
    )
    (net (code "161") (name "Net-(Q169-G)") (class "Default")
      (node (ref "Q169") (pin "1") (pinfunction "G_1") (pintype "passive"))
      (node (ref "Q172") (pin "1") (pinfunction "G_1") (pintype "passive"))
    )
    (net (code "162") (name "Net-(Q169-S)") (class "Default")
      (node (ref "Q169") (pin "2") (pinfunction "S_2") (pintype "passive"))
      (node (ref "Q170") (pin "3") (pinfunction "D_3") (pintype "passive"))
    )
    (net (code "163") (name "Net-(Q170-G)") (class "Default")
      (node (ref "Q170") (pin "1") (pinfunction "G_1") (pintype "passive"))
      (node (ref "Q171") (pin "1") (pinfunction "G_1") (pintype "passive"))
    )
    (net (code "164") (name "Net-(Q173-D)") (class "Default")
      (node (ref "Q173") (pin "3") (pinfunction "D_3") (pintype "passive"))
      (node (ref "Q175") (pin "3") (pinfunction "D_3") (pintype "passive"))
      (node (ref "Q176") (pin "3") (pinfunction "D_3") (pintype "passive"))
    )
    (net (code "165") (name "Net-(Q173-G)") (class "Default")
      (node (ref "Q173") (pin "1") (pinfunction "G_1") (pintype "passive"))
      (node (ref "Q176") (pin "1") (pinfunction "G_1") (pintype "passive"))
    )
    (net (code "166") (name "Net-(Q173-S)") (class "Default")
      (node (ref "Q173") (pin "2") (pinfunction "S_2") (pintype "passive"))
      (node (ref "Q174") (pin "3") (pinfunction "D_3") (pintype "passive"))
    )
    (net (code "167") (name "Net-(Q174-G)") (class "Default")
      (node (ref "Q174") (pin "1") (pinfunction "G_1") (pintype "passive"))
      (node (ref "Q175") (pin "1") (pinfunction "G_1") (pintype "passive"))
    )
    (net (code "168") (name "Net-(Q177-D)") (class "Default")
      (node (ref "Q177") (pin "3") (pinfunction "D_3") (pintype "passive"))
      (node (ref "Q179") (pin "3") (pinfunction "D_3") (pintype "passive"))
      (node (ref "Q180") (pin "3") (pinfunction "D_3") (pintype "passive"))
    )
    (net (code "169") (name "Net-(Q177-G)") (class "Default")
      (node (ref "Q177") (pin "1") (pinfunction "G_1") (pintype "passive"))
      (node (ref "Q180") (pin "1") (pinfunction "G_1") (pintype "passive"))
    )
    (net (code "170") (name "Net-(Q177-S)") (class "Default")
      (node (ref "Q177") (pin "2") (pinfunction "S_2") (pintype "passive"))
      (node (ref "Q178") (pin "3") (pinfunction "D_3") (pintype "passive"))
    )
    (net (code "171") (name "Net-(Q178-G)") (class "Default")
      (node (ref "Q178") (pin "1") (pinfunction "G_1") (pintype "passive"))
      (node (ref "Q179") (pin "1") (pinfunction "G_1") (pintype "passive"))
    )
    (net (code "172") (name "Net-(Q181-D)") (class "Default")
      (node (ref "Q181") (pin "3") (pinfunction "D_3") (pintype "passive"))
      (node (ref "Q183") (pin "3") (pinfunction "D_3") (pintype "passive"))
      (node (ref "Q184") (pin "3") (pinfunction "D_3") (pintype "passive"))
    )
    (net (code "173") (name "Net-(Q181-G)") (class "Default")
      (node (ref "Q181") (pin "1") (pinfunction "G_1") (pintype "passive"))
      (node (ref "Q184") (pin "1") (pinfunction "G_1") (pintype "passive"))
    )
    (net (code "174") (name "Net-(Q181-S)") (class "Default")
      (node (ref "Q181") (pin "2") (pinfunction "S_2") (pintype "passive"))
      (node (ref "Q182") (pin "3") (pinfunction "D_3") (pintype "passive"))
    )
    (net (code "175") (name "Net-(Q182-G)") (class "Default")
      (node (ref "Q182") (pin "1") (pinfunction "G_1") (pintype "passive"))
      (node (ref "Q183") (pin "1") (pinfunction "G_1") (pintype "passive"))
    )
    (net (code "176") (name "Net-(Q185-D)") (class "Default")
      (node (ref "Q185") (pin "3") (pinfunction "D_3") (pintype "passive"))
      (node (ref "Q187") (pin "3") (pinfunction "D_3") (pintype "passive"))
      (node (ref "Q188") (pin "3") (pinfunction "D_3") (pintype "passive"))
    )
    (net (code "177") (name "Net-(Q185-G)") (class "Default")
      (node (ref "Q185") (pin "1") (pinfunction "G_1") (pintype "passive"))
      (node (ref "Q188") (pin "1") (pinfunction "G_1") (pintype "passive"))
    )
    (net (code "178") (name "Net-(Q185-S)") (class "Default")
      (node (ref "Q185") (pin "2") (pinfunction "S_2") (pintype "passive"))
      (node (ref "Q186") (pin "3") (pinfunction "D_3") (pintype "passive"))
    )
    (net (code "179") (name "Net-(Q186-G)") (class "Default")
      (node (ref "Q186") (pin "1") (pinfunction "G_1") (pintype "passive"))
      (node (ref "Q187") (pin "1") (pinfunction "G_1") (pintype "passive"))
    )
    (net (code "180") (name "Net-(Q189-D)") (class "Default")
      (node (ref "Q189") (pin "3") (pinfunction "D_3") (pintype "passive"))
      (node (ref "Q191") (pin "3") (pinfunction "D_3") (pintype "passive"))
      (node (ref "Q192") (pin "3") (pinfunction "D_3") (pintype "passive"))
    )
    (net (code "181") (name "Net-(Q189-G)") (class "Default")
      (node (ref "Q189") (pin "1") (pinfunction "G_1") (pintype "passive"))
      (node (ref "Q192") (pin "1") (pinfunction "G_1") (pintype "passive"))
    )
    (net (code "182") (name "Net-(Q189-S)") (class "Default")
      (node (ref "Q189") (pin "2") (pinfunction "S_2") (pintype "passive"))
      (node (ref "Q190") (pin "3") (pinfunction "D_3") (pintype "passive"))
    )
    (net (code "183") (name "Net-(Q190-G)") (class "Default")
      (node (ref "Q190") (pin "1") (pinfunction "G_1") (pintype "passive"))
      (node (ref "Q191") (pin "1") (pinfunction "G_1") (pintype "passive"))
    )
    (net (code "184") (name "Net-(Q193-D)") (class "Default")
      (node (ref "Q193") (pin "3") (pinfunction "D_3") (pintype "passive"))
      (node (ref "Q195") (pin "3") (pinfunction "D_3") (pintype "passive"))
      (node (ref "Q196") (pin "3") (pinfunction "D_3") (pintype "passive"))
    )
    (net (code "185") (name "Net-(Q193-G)") (class "Default")
      (node (ref "Q193") (pin "1") (pinfunction "G_1") (pintype "passive"))
      (node (ref "Q196") (pin "1") (pinfunction "G_1") (pintype "passive"))
    )
    (net (code "186") (name "Net-(Q193-S)") (class "Default")
      (node (ref "Q193") (pin "2") (pinfunction "S_2") (pintype "passive"))
      (node (ref "Q194") (pin "3") (pinfunction "D_3") (pintype "passive"))
    )
    (net (code "187") (name "Net-(Q194-G)") (class "Default")
      (node (ref "Q194") (pin "1") (pinfunction "G_1") (pintype "passive"))
      (node (ref "Q195") (pin "1") (pinfunction "G_1") (pintype "passive"))
    )
    (net (code "188") (name "Net-(Q197-D)") (class "Default")
      (node (ref "Q197") (pin "3") (pinfunction "D_3") (pintype "passive"))
      (node (ref "Q199") (pin "3") (pinfunction "D_3") (pintype "passive"))
      (node (ref "Q200") (pin "3") (pinfunction "D_3") (pintype "passive"))
    )
    (net (code "189") (name "Net-(Q197-G)") (class "Default")
      (node (ref "Q197") (pin "1") (pinfunction "G_1") (pintype "passive"))
      (node (ref "Q200") (pin "1") (pinfunction "G_1") (pintype "passive"))
    )
    (net (code "190") (name "Net-(Q197-S)") (class "Default")
      (node (ref "Q197") (pin "2") (pinfunction "S_2") (pintype "passive"))
      (node (ref "Q198") (pin "3") (pinfunction "D_3") (pintype "passive"))
    )
    (net (code "191") (name "Net-(Q198-G)") (class "Default")
      (node (ref "Q198") (pin "1") (pinfunction "G_1") (pintype "passive"))
      (node (ref "Q199") (pin "1") (pinfunction "G_1") (pintype "passive"))
    )
    (net (code "192") (name "Net-(Q201-D)") (class "Default")
      (node (ref "Q201") (pin "3") (pinfunction "D_3") (pintype "passive"))
      (node (ref "Q203") (pin "3") (pinfunction "D_3") (pintype "passive"))
      (node (ref "Q204") (pin "3") (pinfunction "D_3") (pintype "passive"))
    )
    (net (code "193") (name "Net-(Q201-G)") (class "Default")
      (node (ref "Q201") (pin "1") (pinfunction "G_1") (pintype "passive"))
      (node (ref "Q204") (pin "1") (pinfunction "G_1") (pintype "passive"))
    )
    (net (code "194") (name "Net-(Q201-S)") (class "Default")
      (node (ref "Q201") (pin "2") (pinfunction "S_2") (pintype "passive"))
      (node (ref "Q202") (pin "3") (pinfunction "D_3") (pintype "passive"))
    )
    (net (code "195") (name "Net-(Q202-G)") (class "Default")
      (node (ref "Q202") (pin "1") (pinfunction "G_1") (pintype "passive"))
      (node (ref "Q203") (pin "1") (pinfunction "G_1") (pintype "passive"))
    )
    (net (code "196") (name "Net-(Q205-D)") (class "Default")
      (node (ref "Q205") (pin "3") (pinfunction "D_3") (pintype "passive"))
      (node (ref "Q207") (pin "3") (pinfunction "D_3") (pintype "passive"))
      (node (ref "Q208") (pin "3") (pinfunction "D_3") (pintype "passive"))
    )
    (net (code "197") (name "Net-(Q205-G)") (class "Default")
      (node (ref "Q205") (pin "1") (pinfunction "G_1") (pintype "passive"))
      (node (ref "Q208") (pin "1") (pinfunction "G_1") (pintype "passive"))
    )
    (net (code "198") (name "Net-(Q205-S)") (class "Default")
      (node (ref "Q205") (pin "2") (pinfunction "S_2") (pintype "passive"))
      (node (ref "Q206") (pin "3") (pinfunction "D_3") (pintype "passive"))
    )
    (net (code "199") (name "Net-(Q206-G)") (class "Default")
      (node (ref "Q206") (pin "1") (pinfunction "G_1") (pintype "passive"))
      (node (ref "Q207") (pin "1") (pinfunction "G_1") (pintype "passive"))
    )
    (net (code "200") (name "Net-(Q209-D)") (class "Default")
      (node (ref "Q209") (pin "3") (pinfunction "D_3") (pintype "passive"))
      (node (ref "Q211") (pin "3") (pinfunction "D_3") (pintype "passive"))
      (node (ref "Q212") (pin "3") (pinfunction "D_3") (pintype "passive"))
    )
    (net (code "201") (name "Net-(Q209-G)") (class "Default")
      (node (ref "Q209") (pin "1") (pinfunction "G_1") (pintype "passive"))
      (node (ref "Q212") (pin "1") (pinfunction "G_1") (pintype "passive"))
    )
    (net (code "202") (name "Net-(Q209-S)") (class "Default")
      (node (ref "Q209") (pin "2") (pinfunction "S_2") (pintype "passive"))
      (node (ref "Q210") (pin "3") (pinfunction "D_3") (pintype "passive"))
    )
    (net (code "203") (name "Net-(Q210-G)") (class "Default")
      (node (ref "Q210") (pin "1") (pinfunction "G_1") (pintype "passive"))
      (node (ref "Q211") (pin "1") (pinfunction "G_1") (pintype "passive"))
    )
    (net (code "204") (name "Net-(Q213-D)") (class "Default")
      (node (ref "Q213") (pin "3") (pinfunction "D_3") (pintype "passive"))
      (node (ref "Q215") (pin "3") (pinfunction "D_3") (pintype "passive"))
      (node (ref "Q216") (pin "3") (pinfunction "D_3") (pintype "passive"))
    )
    (net (code "205") (name "Net-(Q213-G)") (class "Default")
      (node (ref "Q213") (pin "1") (pinfunction "G_1") (pintype "passive"))
      (node (ref "Q216") (pin "1") (pinfunction "G_1") (pintype "passive"))
    )
    (net (code "206") (name "Net-(Q213-S)") (class "Default")
      (node (ref "Q213") (pin "2") (pinfunction "S_2") (pintype "passive"))
      (node (ref "Q214") (pin "3") (pinfunction "D_3") (pintype "passive"))
    )
    (net (code "207") (name "Net-(Q214-G)") (class "Default")
      (node (ref "Q214") (pin "1") (pinfunction "G_1") (pintype "passive"))
      (node (ref "Q215") (pin "1") (pinfunction "G_1") (pintype "passive"))
    )
    (net (code "208") (name "Net-(Q217-D)") (class "Default")
      (node (ref "Q217") (pin "3") (pinfunction "D_3") (pintype "passive"))
      (node (ref "Q219") (pin "3") (pinfunction "D_3") (pintype "passive"))
      (node (ref "Q220") (pin "3") (pinfunction "D_3") (pintype "passive"))
    )
    (net (code "209") (name "Net-(Q217-G)") (class "Default")
      (node (ref "Q217") (pin "1") (pinfunction "G_1") (pintype "passive"))
      (node (ref "Q220") (pin "1") (pinfunction "G_1") (pintype "passive"))
    )
    (net (code "210") (name "Net-(Q217-S)") (class "Default")
      (node (ref "Q217") (pin "2") (pinfunction "S_2") (pintype "passive"))
      (node (ref "Q218") (pin "3") (pinfunction "D_3") (pintype "passive"))
    )
    (net (code "211") (name "Net-(Q218-G)") (class "Default")
      (node (ref "Q218") (pin "1") (pinfunction "G_1") (pintype "passive"))
      (node (ref "Q219") (pin "1") (pinfunction "G_1") (pintype "passive"))
    )
    (net (code "212") (name "Net-(Q221-D)") (class "Default")
      (node (ref "Q221") (pin "3") (pinfunction "D_3") (pintype "passive"))
      (node (ref "Q223") (pin "3") (pinfunction "D_3") (pintype "passive"))
      (node (ref "Q224") (pin "3") (pinfunction "D_3") (pintype "passive"))
    )
    (net (code "213") (name "Net-(Q221-G)") (class "Default")
      (node (ref "Q221") (pin "1") (pinfunction "G_1") (pintype "passive"))
      (node (ref "Q224") (pin "1") (pinfunction "G_1") (pintype "passive"))
    )
    (net (code "214") (name "Net-(Q221-S)") (class "Default")
      (node (ref "Q221") (pin "2") (pinfunction "S_2") (pintype "passive"))
      (node (ref "Q222") (pin "3") (pinfunction "D_3") (pintype "passive"))
    )
    (net (code "215") (name "Net-(Q222-G)") (class "Default")
      (node (ref "Q222") (pin "1") (pinfunction "G_1") (pintype "passive"))
      (node (ref "Q223") (pin "1") (pinfunction "G_1") (pintype "passive"))
    )
    (net (code "216") (name "Net-(Q225-G)") (class "Default")
      (node (ref "IC1") (pin "15") (pinfunction "15_15") (pintype "passive"))
      (node (ref "Q225") (pin "1") (pinfunction "G_1") (pintype "passive"))
      (node (ref "Q226") (pin "1") (pinfunction "G_1") (pintype "passive"))
    )
    (net (code "217") (name "Net-(Q227-G)") (class "Default")
      (node (ref "IC1") (pin "1") (pinfunction "1_1") (pintype "passive"))
      (node (ref "Q227") (pin "1") (pinfunction "G_1") (pintype "passive"))
      (node (ref "Q228") (pin "1") (pinfunction "G_1") (pintype "passive"))
    )
    (net (code "218") (name "Net-(Q229-D)") (class "Default")
      (node (ref "Q229") (pin "3") (pinfunction "D_3") (pintype "passive"))
      (node (ref "Q230") (pin "3") (pinfunction "D_3") (pintype "passive"))
      (node (ref "Q34") (pin "1") (pinfunction "G_1") (pintype "passive"))
      (node (ref "Q35") (pin "1") (pinfunction "G_1") (pintype "passive"))
    )
    (net (code "219") (name "Net-(Q229-G)") (class "Default")
      (node (ref "IC1") (pin "2") (pinfunction "2_2") (pintype "passive"))
      (node (ref "Q229") (pin "1") (pinfunction "G_1") (pintype "passive"))
      (node (ref "Q230") (pin "1") (pinfunction "G_1") (pintype "passive"))
    )
    (net (code "220") (name "Net-(Q231-D)") (class "Default")
      (node (ref "Q231") (pin "3") (pinfunction "D_3") (pintype "passive"))
      (node (ref "Q232") (pin "3") (pinfunction "D_3") (pintype "passive"))
      (node (ref "Q33") (pin "1") (pinfunction "G_1") (pintype "passive"))
      (node (ref "Q36") (pin "1") (pinfunction "G_1") (pintype "passive"))
    )
    (net (code "221") (name "Net-(Q231-G)") (class "Default")
      (node (ref "IC1") (pin "3") (pinfunction "3_3") (pintype "passive"))
      (node (ref "Q231") (pin "1") (pinfunction "G_1") (pintype "passive"))
      (node (ref "Q232") (pin "1") (pinfunction "G_1") (pintype "passive"))
    )
    (net (code "222") (name "Net-(Q233-D)") (class "Default")
      (node (ref "Q233") (pin "3") (pinfunction "D_3") (pintype "passive"))
      (node (ref "Q234") (pin "3") (pinfunction "D_3") (pintype "passive"))
      (node (ref "Q38") (pin "1") (pinfunction "G_1") (pintype "passive"))
      (node (ref "Q39") (pin "1") (pinfunction "G_1") (pintype "passive"))
    )
    (net (code "223") (name "Net-(Q233-G)") (class "Default")
      (node (ref "IC1") (pin "4") (pinfunction "4_4") (pintype "passive"))
      (node (ref "Q233") (pin "1") (pinfunction "G_1") (pintype "passive"))
      (node (ref "Q234") (pin "1") (pinfunction "G_1") (pintype "passive"))
    )
    (net (code "224") (name "Net-(Q235-D)") (class "Default")
      (node (ref "Q235") (pin "3") (pinfunction "D_3") (pintype "passive"))
      (node (ref "Q236") (pin "3") (pinfunction "D_3") (pintype "passive"))
    )
    (net (code "225") (name "Net-(Q235-G)") (class "Default")
      (node (ref "IC1") (pin "5") (pinfunction "5_5") (pintype "passive"))
      (node (ref "Q235") (pin "1") (pinfunction "G_1") (pintype "passive"))
      (node (ref "Q236") (pin "1") (pinfunction "G_1") (pintype "passive"))
      (node (ref "Q37") (pin "1") (pinfunction "G_1") (pintype "passive"))
      (node (ref "Q40") (pin "1") (pinfunction "G_1") (pintype "passive"))
    )
    (net (code "226") (name "Net-(Q237-D)") (class "Default")
      (node (ref "Q237") (pin "3") (pinfunction "D_3") (pintype "passive"))
      (node (ref "Q238") (pin "3") (pinfunction "D_3") (pintype "passive"))
      (node (ref "Q42") (pin "1") (pinfunction "G_1") (pintype "passive"))
      (node (ref "Q43") (pin "1") (pinfunction "G_1") (pintype "passive"))
    )
    (net (code "227") (name "Net-(Q237-G)") (class "Default")
      (node (ref "IC1") (pin "6") (pinfunction "6_6") (pintype "passive"))
      (node (ref "Q237") (pin "1") (pinfunction "G_1") (pintype "passive"))
      (node (ref "Q238") (pin "1") (pinfunction "G_1") (pintype "passive"))
    )
    (net (code "228") (name "Net-(Q239-D)") (class "Default")
      (node (ref "Q239") (pin "3") (pinfunction "D_3") (pintype "passive"))
      (node (ref "Q240") (pin "3") (pinfunction "D_3") (pintype "passive"))
    )
    (net (code "229") (name "Net-(Q239-G)") (class "Default")
      (node (ref "IC1") (pin "7") (pinfunction "7_7") (pintype "passive"))
      (node (ref "Q239") (pin "1") (pinfunction "G_1") (pintype "passive"))
      (node (ref "Q240") (pin "1") (pinfunction "G_1") (pintype "passive"))
    )
    (net (code "230") (name "Net-(Q241-D)") (class "Default")
      (node (ref "Q241") (pin "3") (pinfunction "D_3") (pintype "passive"))
      (node (ref "Q242") (pin "3") (pinfunction "D_3") (pintype "passive"))
    )
    (net (code "231") (name "Net-(Q241-G)") (class "Default")
      (node (ref "IC2") (pin "15") (pinfunction "15_15") (pintype "passive"))
      (node (ref "Q241") (pin "1") (pinfunction "G_1") (pintype "passive"))
      (node (ref "Q242") (pin "1") (pinfunction "G_1") (pintype "passive"))
    )
    (net (code "232") (name "Net-(Q243-D)") (class "Default")
      (node (ref "Q243") (pin "3") (pinfunction "D_3") (pintype "passive"))
      (node (ref "Q244") (pin "3") (pinfunction "D_3") (pintype "passive"))
    )
    (net (code "233") (name "Net-(Q243-G)") (class "Default")
      (node (ref "IC2") (pin "1") (pinfunction "1_1") (pintype "passive"))
      (node (ref "Q243") (pin "1") (pinfunction "G_1") (pintype "passive"))
      (node (ref "Q244") (pin "1") (pinfunction "G_1") (pintype "passive"))
    )
    (net (code "234") (name "Net-(Q245-D)") (class "Default")
      (node (ref "Q245") (pin "3") (pinfunction "D_3") (pintype "passive"))
      (node (ref "Q246") (pin "3") (pinfunction "D_3") (pintype "passive"))
    )
    (net (code "235") (name "Net-(Q245-G)") (class "Default")
      (node (ref "IC2") (pin "2") (pinfunction "2_2") (pintype "passive"))
      (node (ref "Q245") (pin "1") (pinfunction "G_1") (pintype "passive"))
      (node (ref "Q246") (pin "1") (pinfunction "G_1") (pintype "passive"))
    )
    (net (code "236") (name "Net-(Q247-D)") (class "Default")
      (node (ref "Q247") (pin "3") (pinfunction "D_3") (pintype "passive"))
      (node (ref "Q248") (pin "3") (pinfunction "D_3") (pintype "passive"))
    )
    (net (code "237") (name "Net-(Q247-G)") (class "Default")
      (node (ref "IC2") (pin "3") (pinfunction "3_3") (pintype "passive"))
      (node (ref "Q247") (pin "1") (pinfunction "G_1") (pintype "passive"))
      (node (ref "Q248") (pin "1") (pinfunction "G_1") (pintype "passive"))
    )
    (net (code "238") (name "Net-(Q249-D)") (class "Default")
      (node (ref "Q249") (pin "3") (pinfunction "D_3") (pintype "passive"))
      (node (ref "Q250") (pin "3") (pinfunction "D_3") (pintype "passive"))
    )
    (net (code "239") (name "Net-(Q249-G)") (class "Default")
      (node (ref "IC2") (pin "4") (pinfunction "4_4") (pintype "passive"))
      (node (ref "Q249") (pin "1") (pinfunction "G_1") (pintype "passive"))
      (node (ref "Q250") (pin "1") (pinfunction "G_1") (pintype "passive"))
    )
    (net (code "240") (name "Net-(Q251-D)") (class "Default")
      (node (ref "Q251") (pin "3") (pinfunction "D_3") (pintype "passive"))
      (node (ref "Q252") (pin "3") (pinfunction "D_3") (pintype "passive"))
    )
    (net (code "241") (name "Net-(Q251-G)") (class "Default")
      (node (ref "IC2") (pin "5") (pinfunction "5_5") (pintype "passive"))
      (node (ref "Q251") (pin "1") (pinfunction "G_1") (pintype "passive"))
      (node (ref "Q252") (pin "1") (pinfunction "G_1") (pintype "passive"))
    )
    (net (code "242") (name "Net-(Q253-D)") (class "Default")
      (node (ref "Q253") (pin "3") (pinfunction "D_3") (pintype "passive"))
      (node (ref "Q254") (pin "3") (pinfunction "D_3") (pintype "passive"))
    )
    (net (code "243") (name "Net-(Q253-G)") (class "Default")
      (node (ref "IC2") (pin "6") (pinfunction "6_6") (pintype "passive"))
      (node (ref "Q253") (pin "1") (pinfunction "G_1") (pintype "passive"))
      (node (ref "Q254") (pin "1") (pinfunction "G_1") (pintype "passive"))
    )
    (net (code "244") (name "Net-(Q255-D)") (class "Default")
      (node (ref "Q255") (pin "3") (pinfunction "D_3") (pintype "passive"))
      (node (ref "Q256") (pin "3") (pinfunction "D_3") (pintype "passive"))
    )
    (net (code "245") (name "Net-(Q257-D)") (class "Default")
      (node (ref "IC3") (pin "2") (pinfunction "2_2") (pintype "passive"))
      (node (ref "Q257") (pin "3") (pinfunction "D_3") (pintype "passive"))
      (node (ref "Q258") (pin "3") (pinfunction "D_3") (pintype "passive"))
    )
    (net (code "246") (name "Net-(Q257-G)") (class "Default")
      (node (ref "IC1") (pin "9") (pinfunction "9_9") (pintype "passive"))
      (node (ref "Q257") (pin "1") (pinfunction "G_1") (pintype "passive"))
      (node (ref "Q258") (pin "1") (pinfunction "G_1") (pintype "passive"))
    )
    (net (code "247") (name "Net-(Q259-D)") (class "Default")
      (node (ref "IC4") (pin "2") (pinfunction "2_2") (pintype "passive"))
      (node (ref "Q259") (pin "3") (pinfunction "D_3") (pintype "passive"))
      (node (ref "Q260") (pin "3") (pinfunction "D_3") (pintype "passive"))
    )
    (net (code "248") (name "Net-(Q259-G)") (class "Default")
      (node (ref "IC2") (pin "9") (pinfunction "9_9") (pintype "passive"))
      (node (ref "Q259") (pin "1") (pinfunction "G_1") (pintype "passive"))
      (node (ref "Q260") (pin "1") (pinfunction "G_1") (pintype "passive"))
    )
    (net (code "249") (name "unconnected-(IC1-Pad10)") (class "Default")
      (node (ref "IC1") (pin "10") (pinfunction "10_10") (pintype "passive"))
    )
    (net (code "250") (name "unconnected-(IC1-Pad11)") (class "Default")
      (node (ref "IC1") (pin "11") (pinfunction "11_11") (pintype "passive"))
    )
    (net (code "251") (name "unconnected-(IC1-Pad13)") (class "Default")
      (node (ref "IC1") (pin "13") (pinfunction "13_13") (pintype "passive"))
    )
    (net (code "252") (name "unconnected-(IC2-Pad10)") (class "Default")
      (node (ref "IC2") (pin "10") (pinfunction "10_10") (pintype "passive"))
    )
    (net (code "253") (name "unconnected-(IC2-Pad11)") (class "Default")
      (node (ref "IC2") (pin "11") (pinfunction "11_11") (pintype "passive"))
    )
    (net (code "254") (name "unconnected-(IC2-Pad13)") (class "Default")
      (node (ref "IC2") (pin "13") (pinfunction "13_13") (pintype "passive"))
    )
    (net (code "255") (name "unconnected-(IC3-Pad3)") (class "Default")
      (node (ref "IC3") (pin "3") (pinfunction "3_3") (pintype "passive"))
    )
    (net (code "256") (name "unconnected-(IC3-Pad4)") (class "Default")
      (node (ref "IC3") (pin "4") (pinfunction "4_4") (pintype "passive"))
    )
    (net (code "257") (name "unconnected-(IC3-Pad5)") (class "Default")
      (node (ref "IC3") (pin "5") (pinfunction "5_5") (pintype "passive"))
    )
    (net (code "258") (name "unconnected-(IC3-Pad6)") (class "Default")
      (node (ref "IC3") (pin "6") (pinfunction "6_6") (pintype "passive"))
    )
    (net (code "259") (name "unconnected-(IC3-Pad7)") (class "Default")
      (node (ref "IC3") (pin "7") (pinfunction "7_7") (pintype "passive"))
    )
    (net (code "260") (name "unconnected-(IC3-Pad10)") (class "Default")
      (node (ref "IC3") (pin "10") (pinfunction "10_10") (pintype "passive"))
    )
    (net (code "261") (name "unconnected-(IC3-Pad11)") (class "Default")
      (node (ref "IC3") (pin "11") (pinfunction "11_11") (pintype "passive"))
    )
    (net (code "262") (name "unconnected-(IC3-Pad12)") (class "Default")
      (node (ref "IC3") (pin "12") (pinfunction "12_12") (pintype "passive"))
    )
    (net (code "263") (name "unconnected-(IC3-Pad13)") (class "Default")
      (node (ref "IC3") (pin "13") (pinfunction "13_13") (pintype "passive"))
    )
    (net (code "264") (name "unconnected-(IC3-Pad15)") (class "Default")
      (node (ref "IC3") (pin "15") (pinfunction "15_15") (pintype "passive"))
    )
    (net (code "265") (name "unconnected-(IC4-Pad1)") (class "Default")
      (node (ref "IC4") (pin "1") (pinfunction "1_1") (pintype "passive"))
    )
    (net (code "266") (name "unconnected-(IC4-Pad3)") (class "Default")
      (node (ref "IC4") (pin "3") (pinfunction "3_3") (pintype "passive"))
    )
    (net (code "267") (name "unconnected-(IC4-Pad4)") (class "Default")
      (node (ref "IC4") (pin "4") (pinfunction "4_4") (pintype "passive"))
    )
    (net (code "268") (name "unconnected-(IC4-Pad5)") (class "Default")
      (node (ref "IC4") (pin "5") (pinfunction "5_5") (pintype "passive"))
    )
    (net (code "269") (name "unconnected-(IC4-Pad6)") (class "Default")
      (node (ref "IC4") (pin "6") (pinfunction "6_6") (pintype "passive"))
    )
    (net (code "270") (name "unconnected-(IC4-Pad7)") (class "Default")
      (node (ref "IC4") (pin "7") (pinfunction "7_7") (pintype "passive"))
    )
    (net (code "271") (name "unconnected-(IC4-Pad11)") (class "Default")
      (node (ref "IC4") (pin "11") (pinfunction "11_11") (pintype "passive"))
    )
    (net (code "272") (name "unconnected-(IC4-Pad12)") (class "Default")
      (node (ref "IC4") (pin "12") (pinfunction "12_12") (pintype "passive"))
    )
    (net (code "273") (name "unconnected-(IC4-Pad13)") (class "Default")
      (node (ref "IC4") (pin "13") (pinfunction "13_13") (pintype "passive"))
    )
    (net (code "274") (name "unconnected-(IC4-Pad14)") (class "Default")
      (node (ref "IC4") (pin "14") (pinfunction "14_14") (pintype "passive"))
    )
    (net (code "275") (name "unconnected-(IC4-Pad15)") (class "Default")
      (node (ref "IC4") (pin "15") (pinfunction "15_15") (pintype "passive"))
    )
    (net (code "276") (name "unconnected-(IC5-Pad1)") (class "Default")
      (node (ref "IC5") (pin "1") (pinfunction "1_1") (pintype "passive"))
    )
    (net (code "277") (name "unconnected-(IC5-Pad2)") (class "Default")
      (node (ref "IC5") (pin "2") (pinfunction "2_2") (pintype "passive"))
    )
    (net (code "278") (name "unconnected-(IC5-Pad3)") (class "Default")
      (node (ref "IC5") (pin "3") (pinfunction "3_3") (pintype "passive"))
    )
    (net (code "279") (name "unconnected-(IC5-Pad4)") (class "Default")
      (node (ref "IC5") (pin "4") (pinfunction "4_4") (pintype "passive"))
    )
    (net (code "280") (name "unconnected-(IC5-Pad5)") (class "Default")
      (node (ref "IC5") (pin "5") (pinfunction "5_5") (pintype "passive"))
    )
    (net (code "281") (name "unconnected-(IC5-Pad6)") (class "Default")
      (node (ref "IC5") (pin "6") (pinfunction "6_6") (pintype "passive"))
    )
    (net (code "282") (name "unconnected-(IC5-Pad7)") (class "Default")
      (node (ref "IC5") (pin "7") (pinfunction "7_7") (pintype "passive"))
    )
    (net (code "283") (name "unconnected-(IC5-Pad8)") (class "Default")
      (node (ref "IC5") (pin "8") (pinfunction "8_8") (pintype "passive"))
    )
    (net (code "284") (name "unconnected-(IC5-Pad9)") (class "Default")
      (node (ref "IC5") (pin "9") (pinfunction "9_9") (pintype "passive"))
    )
    (net (code "285") (name "unconnected-(IC5-Pad10)") (class "Default")
      (node (ref "IC5") (pin "10") (pinfunction "10_10") (pintype "passive"))
    )
    (net (code "286") (name "unconnected-(IC5-Pad11)") (class "Default")
      (node (ref "IC5") (pin "11") (pinfunction "11_11") (pintype "passive"))
    )
    (net (code "287") (name "unconnected-(IC5-Pad12)") (class "Default")
      (node (ref "IC5") (pin "12") (pinfunction "12_12") (pintype "passive"))
    )
    (net (code "288") (name "unconnected-(IC5-Pad13)") (class "Default")
      (node (ref "IC5") (pin "13") (pinfunction "13_13") (pintype "passive"))
    )
    (net (code "289") (name "unconnected-(IC5-Pad15)") (class "Default")
      (node (ref "IC5") (pin "15") (pinfunction "15_15") (pintype "passive"))
    )
    (net (code "290") (name "unconnected-(IC5-Pad16)") (class "Default")
      (node (ref "IC5") (pin "16") (pinfunction "16_16") (pintype "passive"))
    )
    (net (code "291") (name "unconnected-(IC5-Pad17)") (class "Default")
      (node (ref "IC5") (pin "17") (pinfunction "17_17") (pintype "passive"))
    )
    (net (code "292") (name "unconnected-(IC5-Pad18)") (class "Default")
      (node (ref "IC5") (pin "18") (pinfunction "18_18") (pintype "passive"))
    )
    (net (code "293") (name "unconnected-(IC5-Pad19)") (class "Default")
      (node (ref "IC5") (pin "19") (pinfunction "19_19") (pintype "passive"))
    )
    (net (code "294") (name "unconnected-(IC5-Pad20)") (class "Default")
      (node (ref "IC5") (pin "20") (pinfunction "20_20") (pintype "passive"))
    )
    (net (code "295") (name "unconnected-(IC5-Pad21)") (class "Default")
      (node (ref "IC5") (pin "21") (pinfunction "21_21") (pintype "passive"))
    )
    (net (code "296") (name "unconnected-(IC5-Pad22)") (class "Default")
      (node (ref "IC5") (pin "22") (pinfunction "22_22") (pintype "passive"))
    )
    (net (code "297") (name "unconnected-(IC5-Pad23)") (class "Default")
      (node (ref "IC5") (pin "23") (pinfunction "23_23") (pintype "passive"))
    )
    (net (code "298") (name "unconnected-(IC5-Pad24)") (class "Default")
      (node (ref "IC5") (pin "24") (pinfunction "24_24") (pintype "passive"))
    )
    (net (code "299") (name "unconnected-(IC5-Pad25)") (class "Default")
      (node (ref "IC5") (pin "25") (pinfunction "25_25") (pintype "passive"))
    )
    (net (code "300") (name "unconnected-(IC5-Pad26)") (class "Default")
      (node (ref "IC5") (pin "26") (pinfunction "26_26") (pintype "passive"))
    )
    (net (code "301") (name "unconnected-(IC5-Pad27)") (class "Default")
      (node (ref "IC5") (pin "27") (pinfunction "27_27") (pintype "passive"))
    )
    (net (code "302") (name "unconnected-(IC6-Pad1)") (class "Default")
      (node (ref "IC6") (pin "1") (pinfunction "1_1") (pintype "passive"))
    )
    (net (code "303") (name "unconnected-(IC6-Pad2)") (class "Default")
      (node (ref "IC6") (pin "2") (pinfunction "2_2") (pintype "passive"))
    )
    (net (code "304") (name "unconnected-(IC6-Pad3)") (class "Default")
      (node (ref "IC6") (pin "3") (pinfunction "3_3") (pintype "passive"))
    )
    (net (code "305") (name "unconnected-(IC6-Pad4)") (class "Default")
      (node (ref "IC6") (pin "4") (pinfunction "4_4") (pintype "passive"))
    )
    (net (code "306") (name "unconnected-(IC6-Pad5)") (class "Default")
      (node (ref "IC6") (pin "5") (pinfunction "5_5") (pintype "passive"))
    )
    (net (code "307") (name "unconnected-(IC6-Pad6)") (class "Default")
      (node (ref "IC6") (pin "6") (pinfunction "6_6") (pintype "passive"))
    )
    (net (code "308") (name "unconnected-(IC6-Pad7)") (class "Default")
      (node (ref "IC6") (pin "7") (pinfunction "7_7") (pintype "passive"))
    )
    (net (code "309") (name "unconnected-(IC6-Pad9)") (class "Default")
      (node (ref "IC6") (pin "9") (pinfunction "9_9") (pintype "passive"))
    )
    (net (code "310") (name "unconnected-(IC6-Pad10)") (class "Default")
      (node (ref "IC6") (pin "10") (pinfunction "10_10") (pintype "passive"))
    )
    (net (code "311") (name "unconnected-(IC6-Pad11)") (class "Default")
      (node (ref "IC6") (pin "11") (pinfunction "11_11") (pintype "passive"))
    )
    (net (code "312") (name "unconnected-(IC6-Pad12)") (class "Default")
      (node (ref "IC6") (pin "12") (pinfunction "12_12") (pintype "passive"))
    )
    (net (code "313") (name "unconnected-(IC6-Pad13)") (class "Default")
      (node (ref "IC6") (pin "13") (pinfunction "13_13") (pintype "passive"))
    )
    (net (code "314") (name "unconnected-(IC6-Pad14)") (class "Default")
      (node (ref "IC6") (pin "14") (pinfunction "14_14") (pintype "passive"))
    )
    (net (code "315") (name "unconnected-(IC6-Pad15)") (class "Default")
      (node (ref "IC6") (pin "15") (pinfunction "15_15") (pintype "passive"))
    )
    (net (code "316") (name "unconnected-(R1-Pad1)") (class "Default")
      (node (ref "R1") (pin "1") (pinfunction "1_1") (pintype "passive"))
    )
    (net (code "317") (name "unconnected-(R1-Pad2)") (class "Default")
      (node (ref "R1") (pin "2") (pinfunction "2_2") (pintype "passive"))
    )
    (net (code "318") (name "unconnected-(R2-Pad1)") (class "Default")
      (node (ref "R2") (pin "1") (pinfunction "1_1") (pintype "passive"))
    )
    (net (code "319") (name "unconnected-(R2-Pad2)") (class "Default")
      (node (ref "R2") (pin "2") (pinfunction "2_2") (pintype "passive"))
    )
    (net (code "320") (name "unconnected-(R3-Pad1)") (class "Default")
      (node (ref "R3") (pin "1") (pinfunction "1_1") (pintype "passive"))
    )
    (net (code "321") (name "unconnected-(R3-Pad2)") (class "Default")
      (node (ref "R3") (pin "2") (pinfunction "2_2") (pintype "passive"))
    )
    (net (code "322") (name "unconnected-(R4-Pad1)") (class "Default")
      (node (ref "R4") (pin "1") (pinfunction "1_1") (pintype "passive"))
    )
    (net (code "323") (name "unconnected-(R4-Pad2)") (class "Default")
      (node (ref "R4") (pin "2") (pinfunction "2_2") (pintype "passive"))
    )
    (net (code "324") (name "unconnected-(R5-Pad1)") (class "Default")
      (node (ref "R5") (pin "1") (pinfunction "1_1") (pintype "passive"))
    )
    (net (code "325") (name "unconnected-(R5-Pad2)") (class "Default")
      (node (ref "R5") (pin "2") (pinfunction "2_2") (pintype "passive"))
    )
    (net (code "326") (name "unconnected-(R6-Pad1)") (class "Default")
      (node (ref "R6") (pin "1") (pinfunction "1_1") (pintype "passive"))
    )
    (net (code "327") (name "unconnected-(R6-Pad2)") (class "Default")
      (node (ref "R6") (pin "2") (pinfunction "2_2") (pintype "passive"))
    )
  )
)
